# Control_Unit.net
KiCad netlist of a schematic drawn in EAGLE
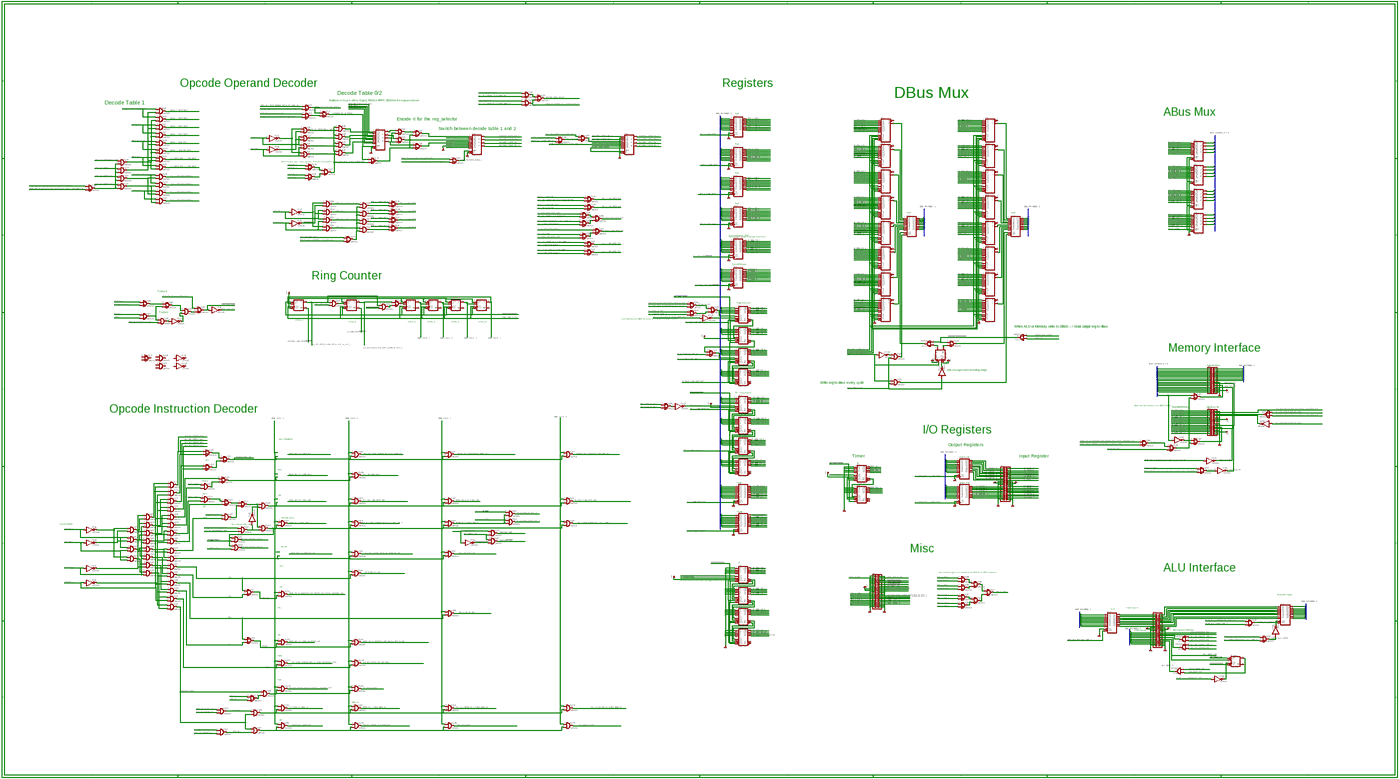
[diagram p0: schematic, sheet 1, overview]
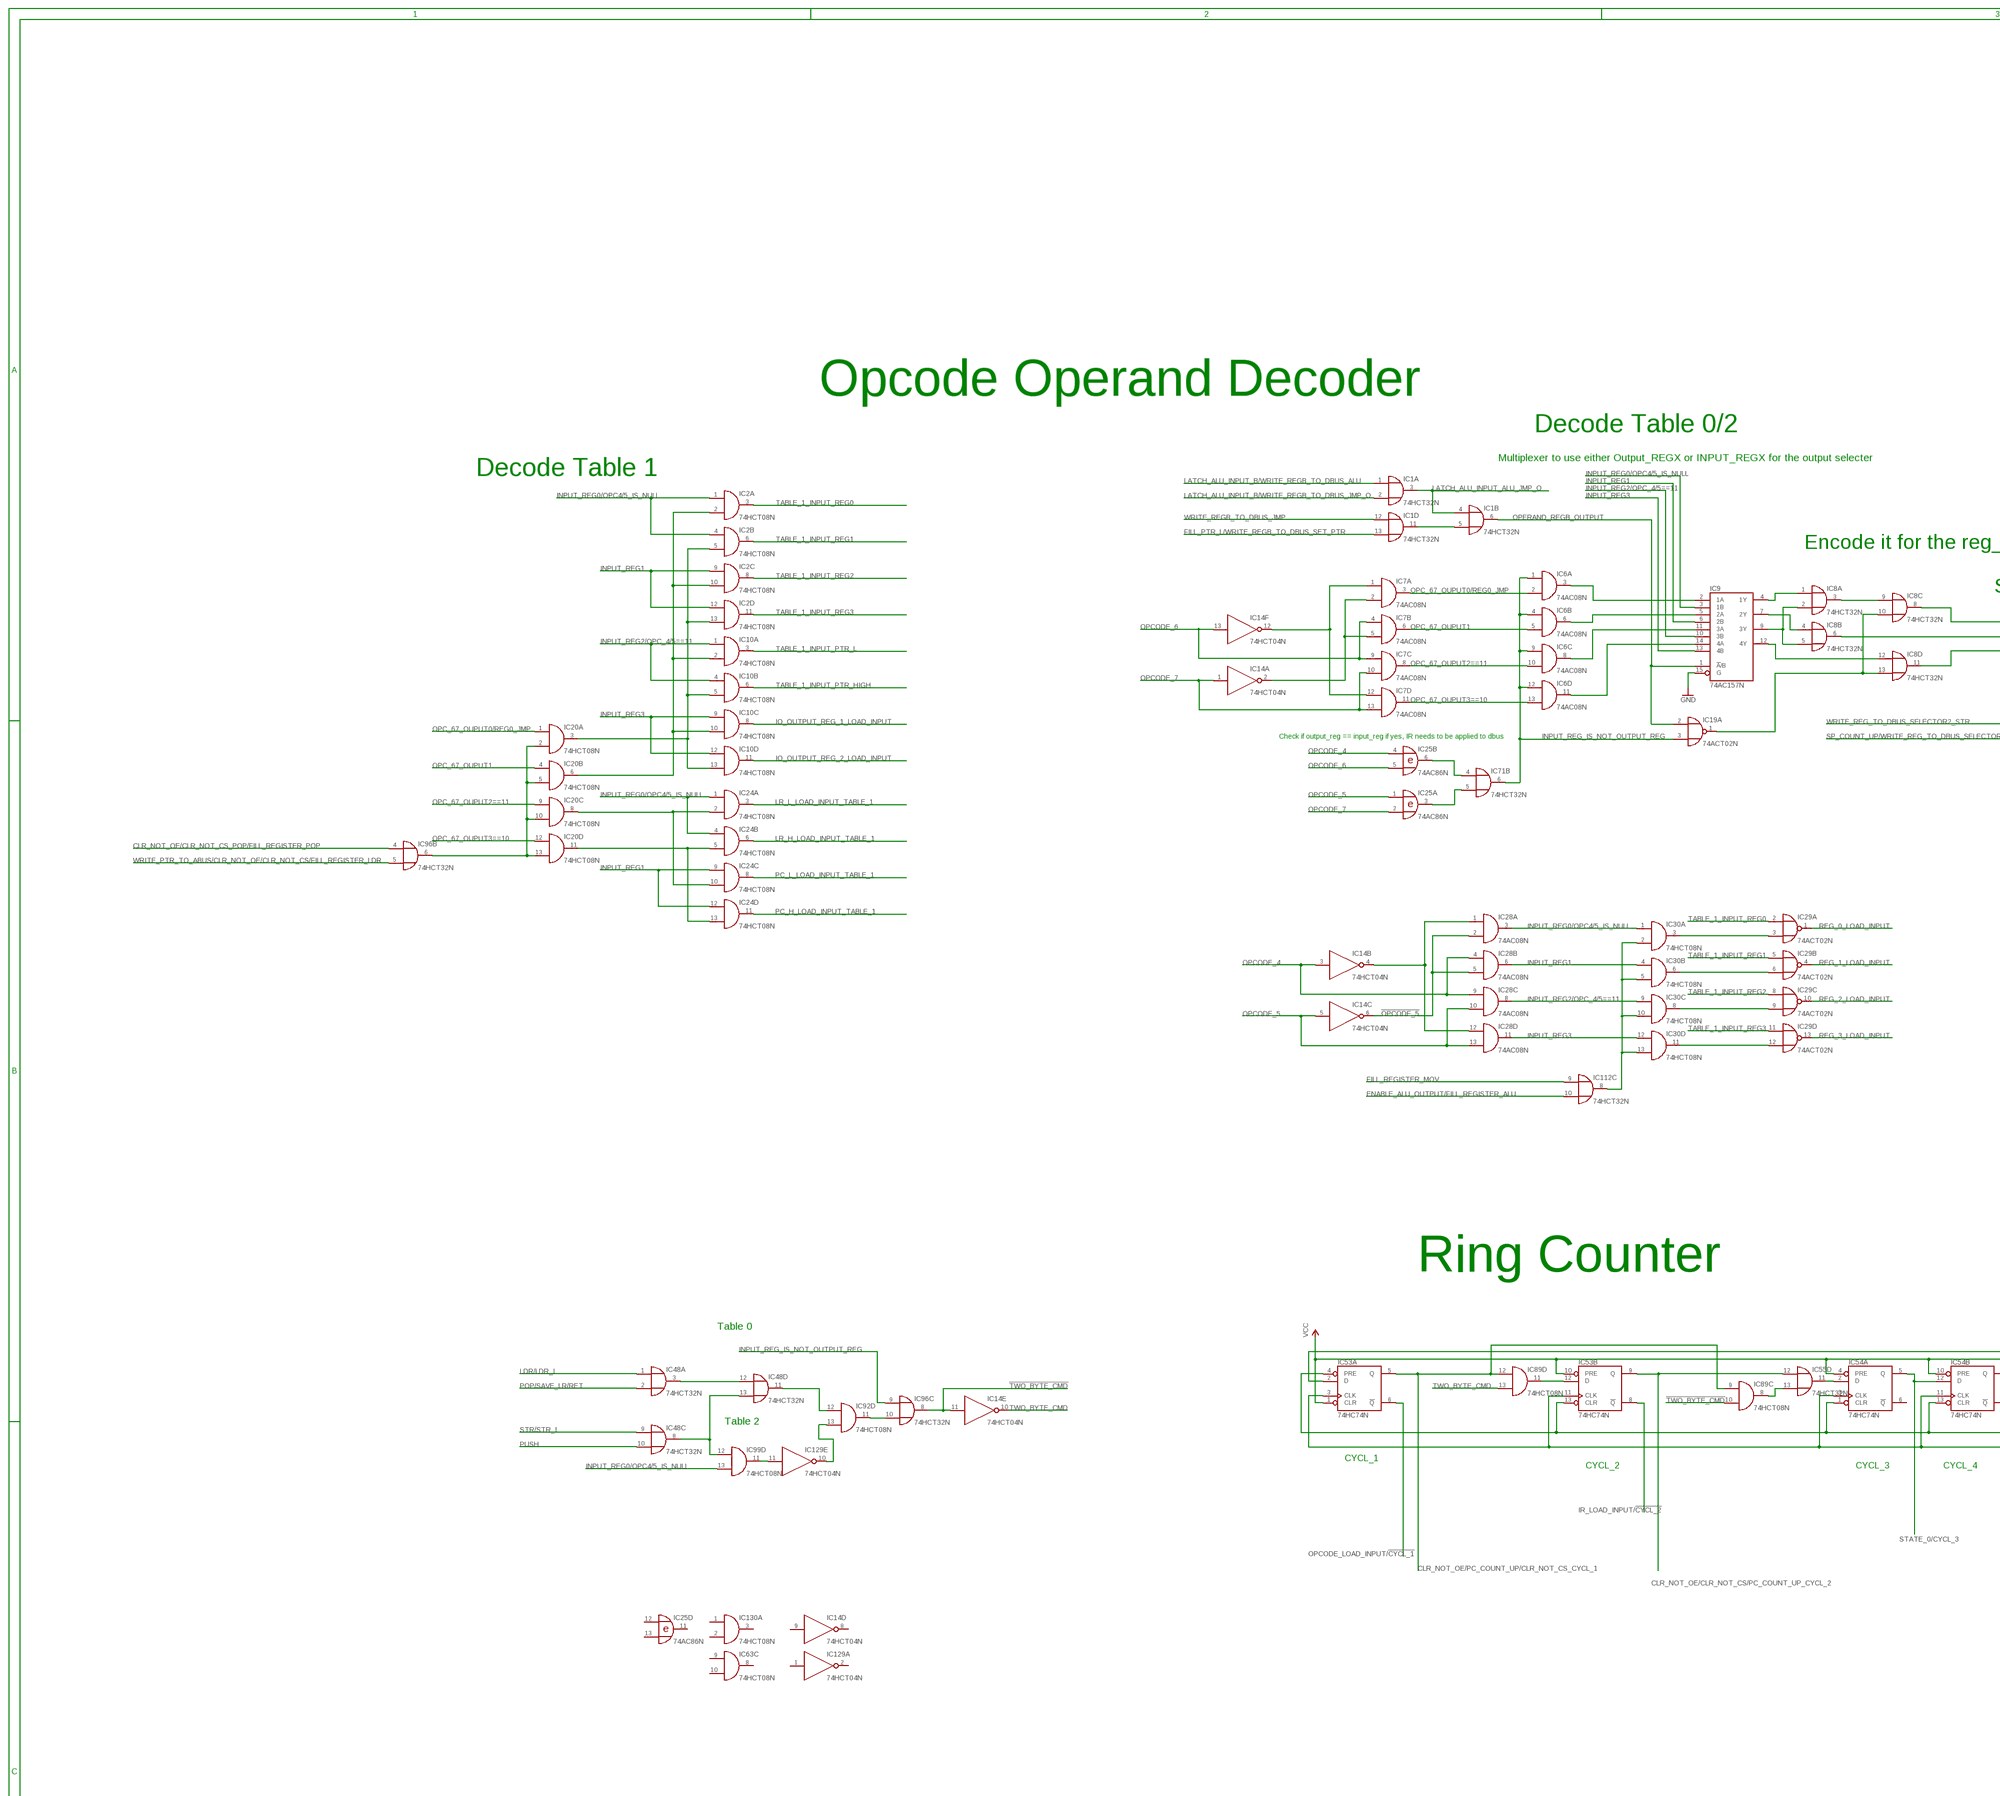
[diagram p1: schematic, sheet 1, part 1 of 8]
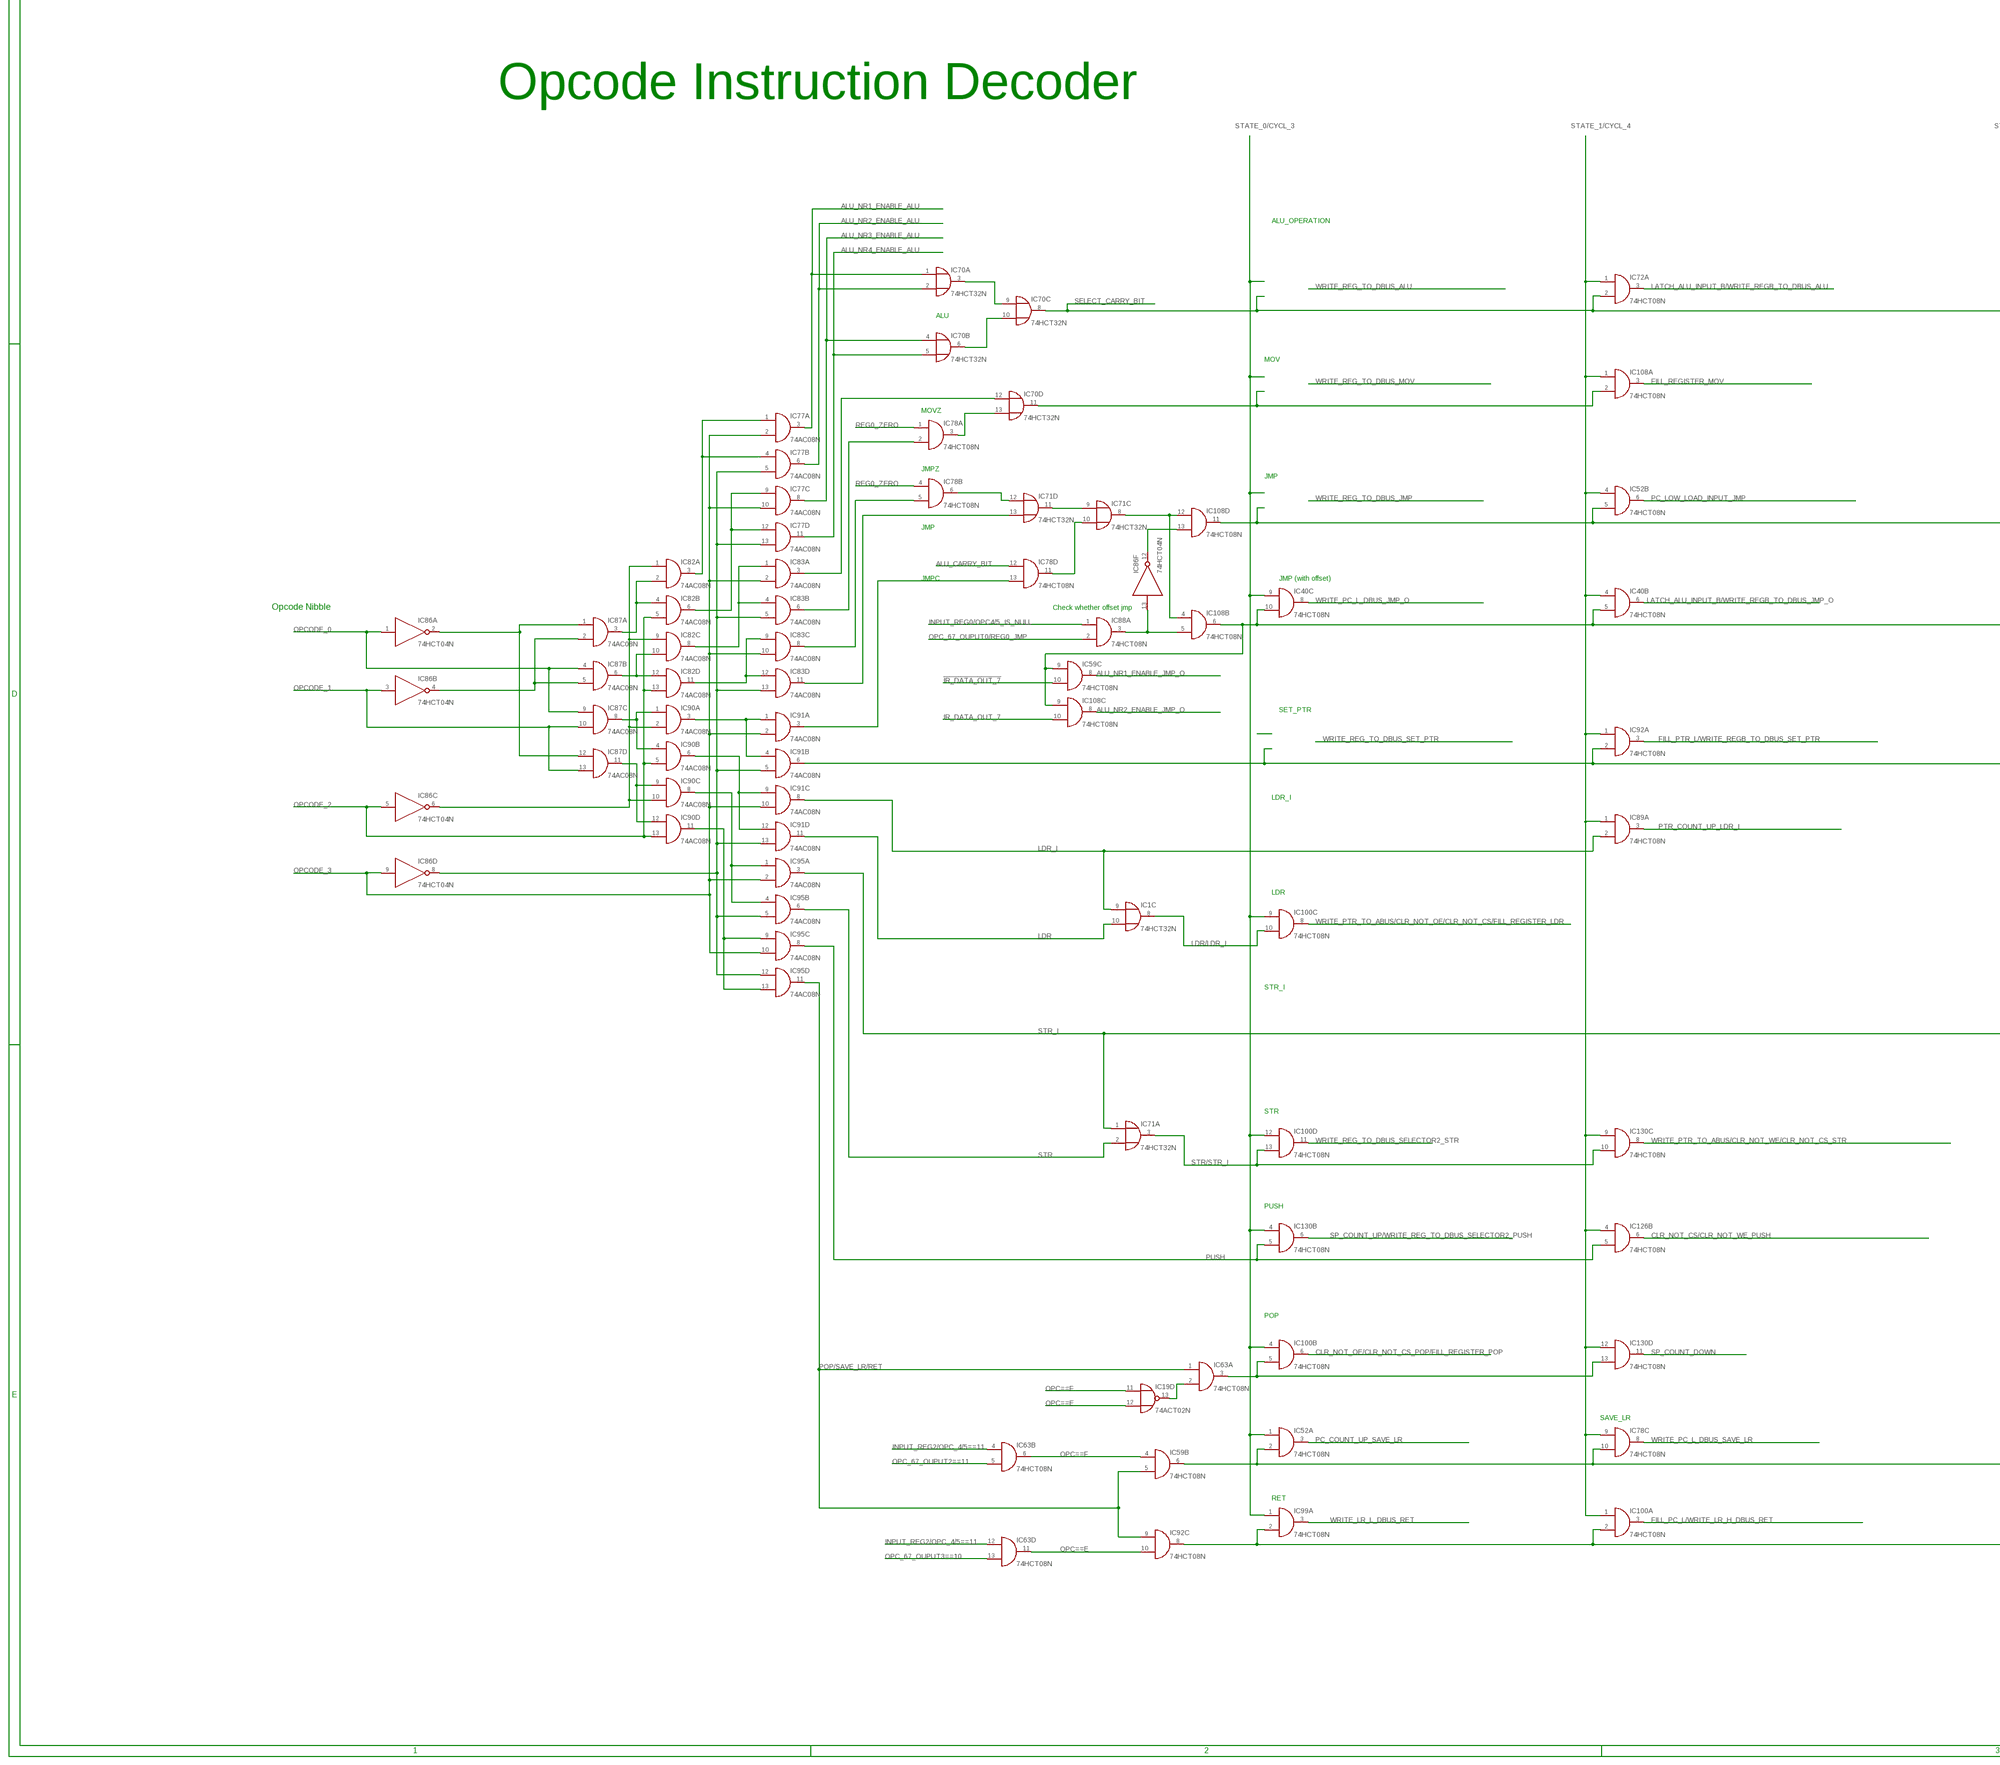
[diagram p2: schematic, sheet 1, part 2 of 8]
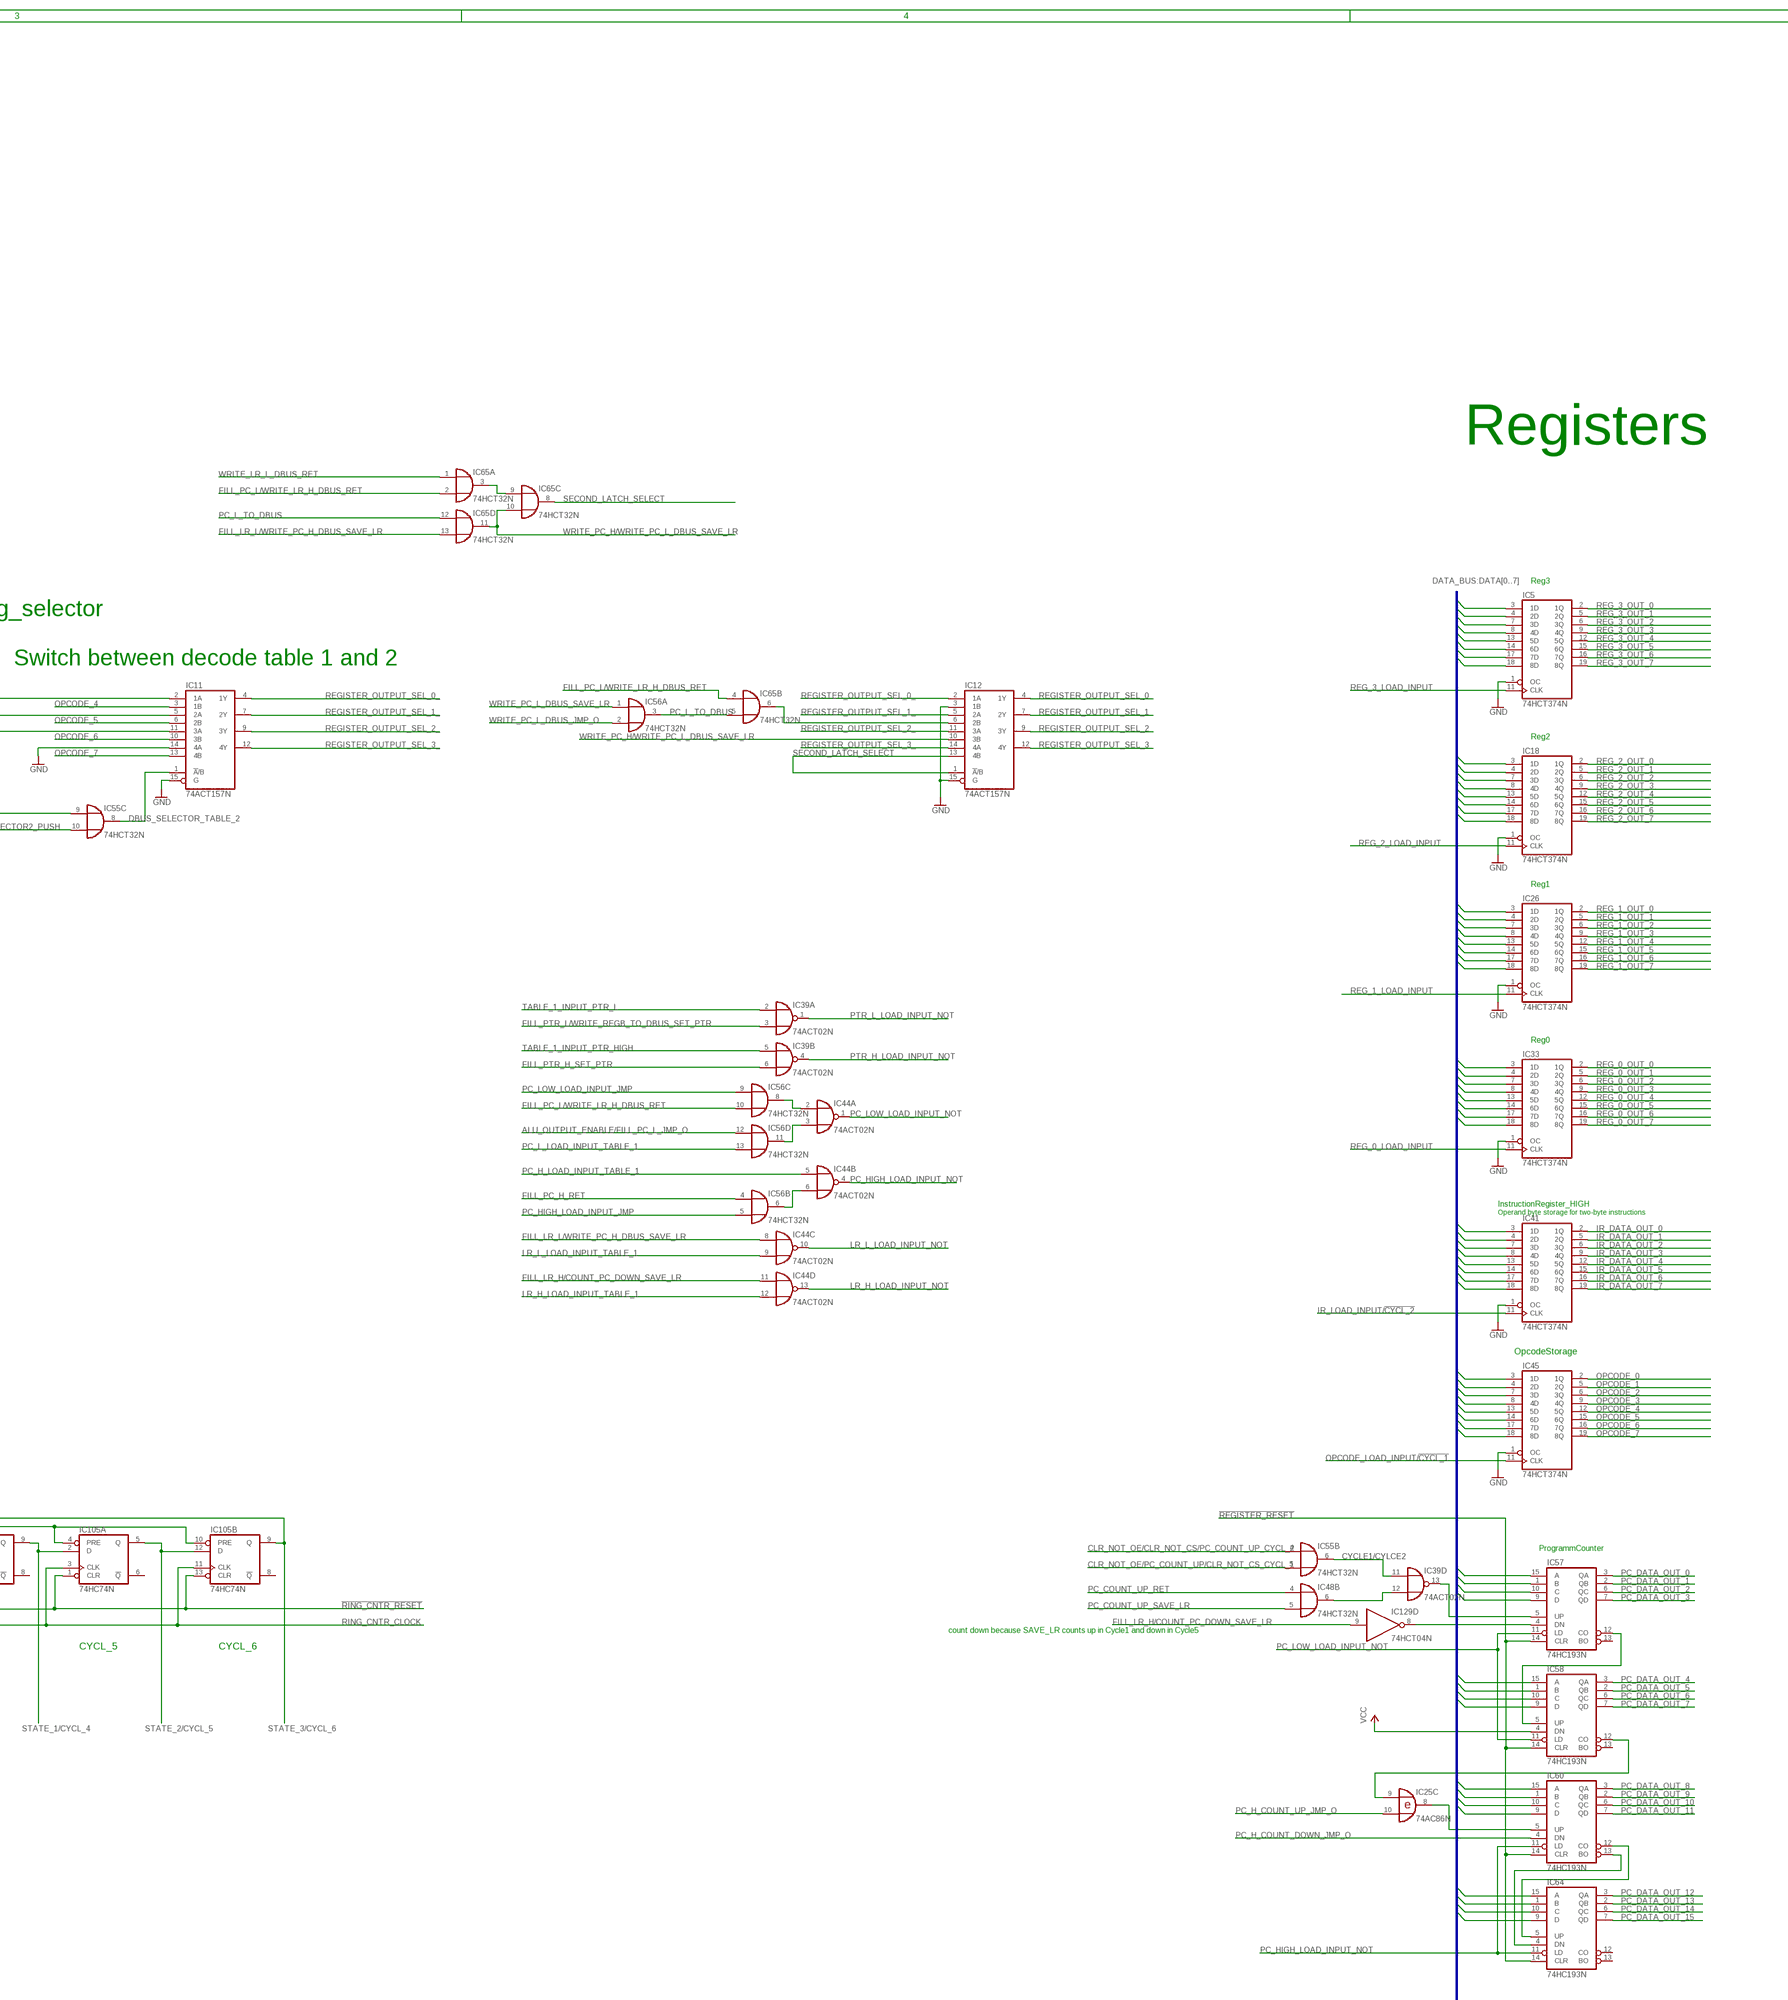
[diagram p3: schematic, sheet 1, part 3 of 8]
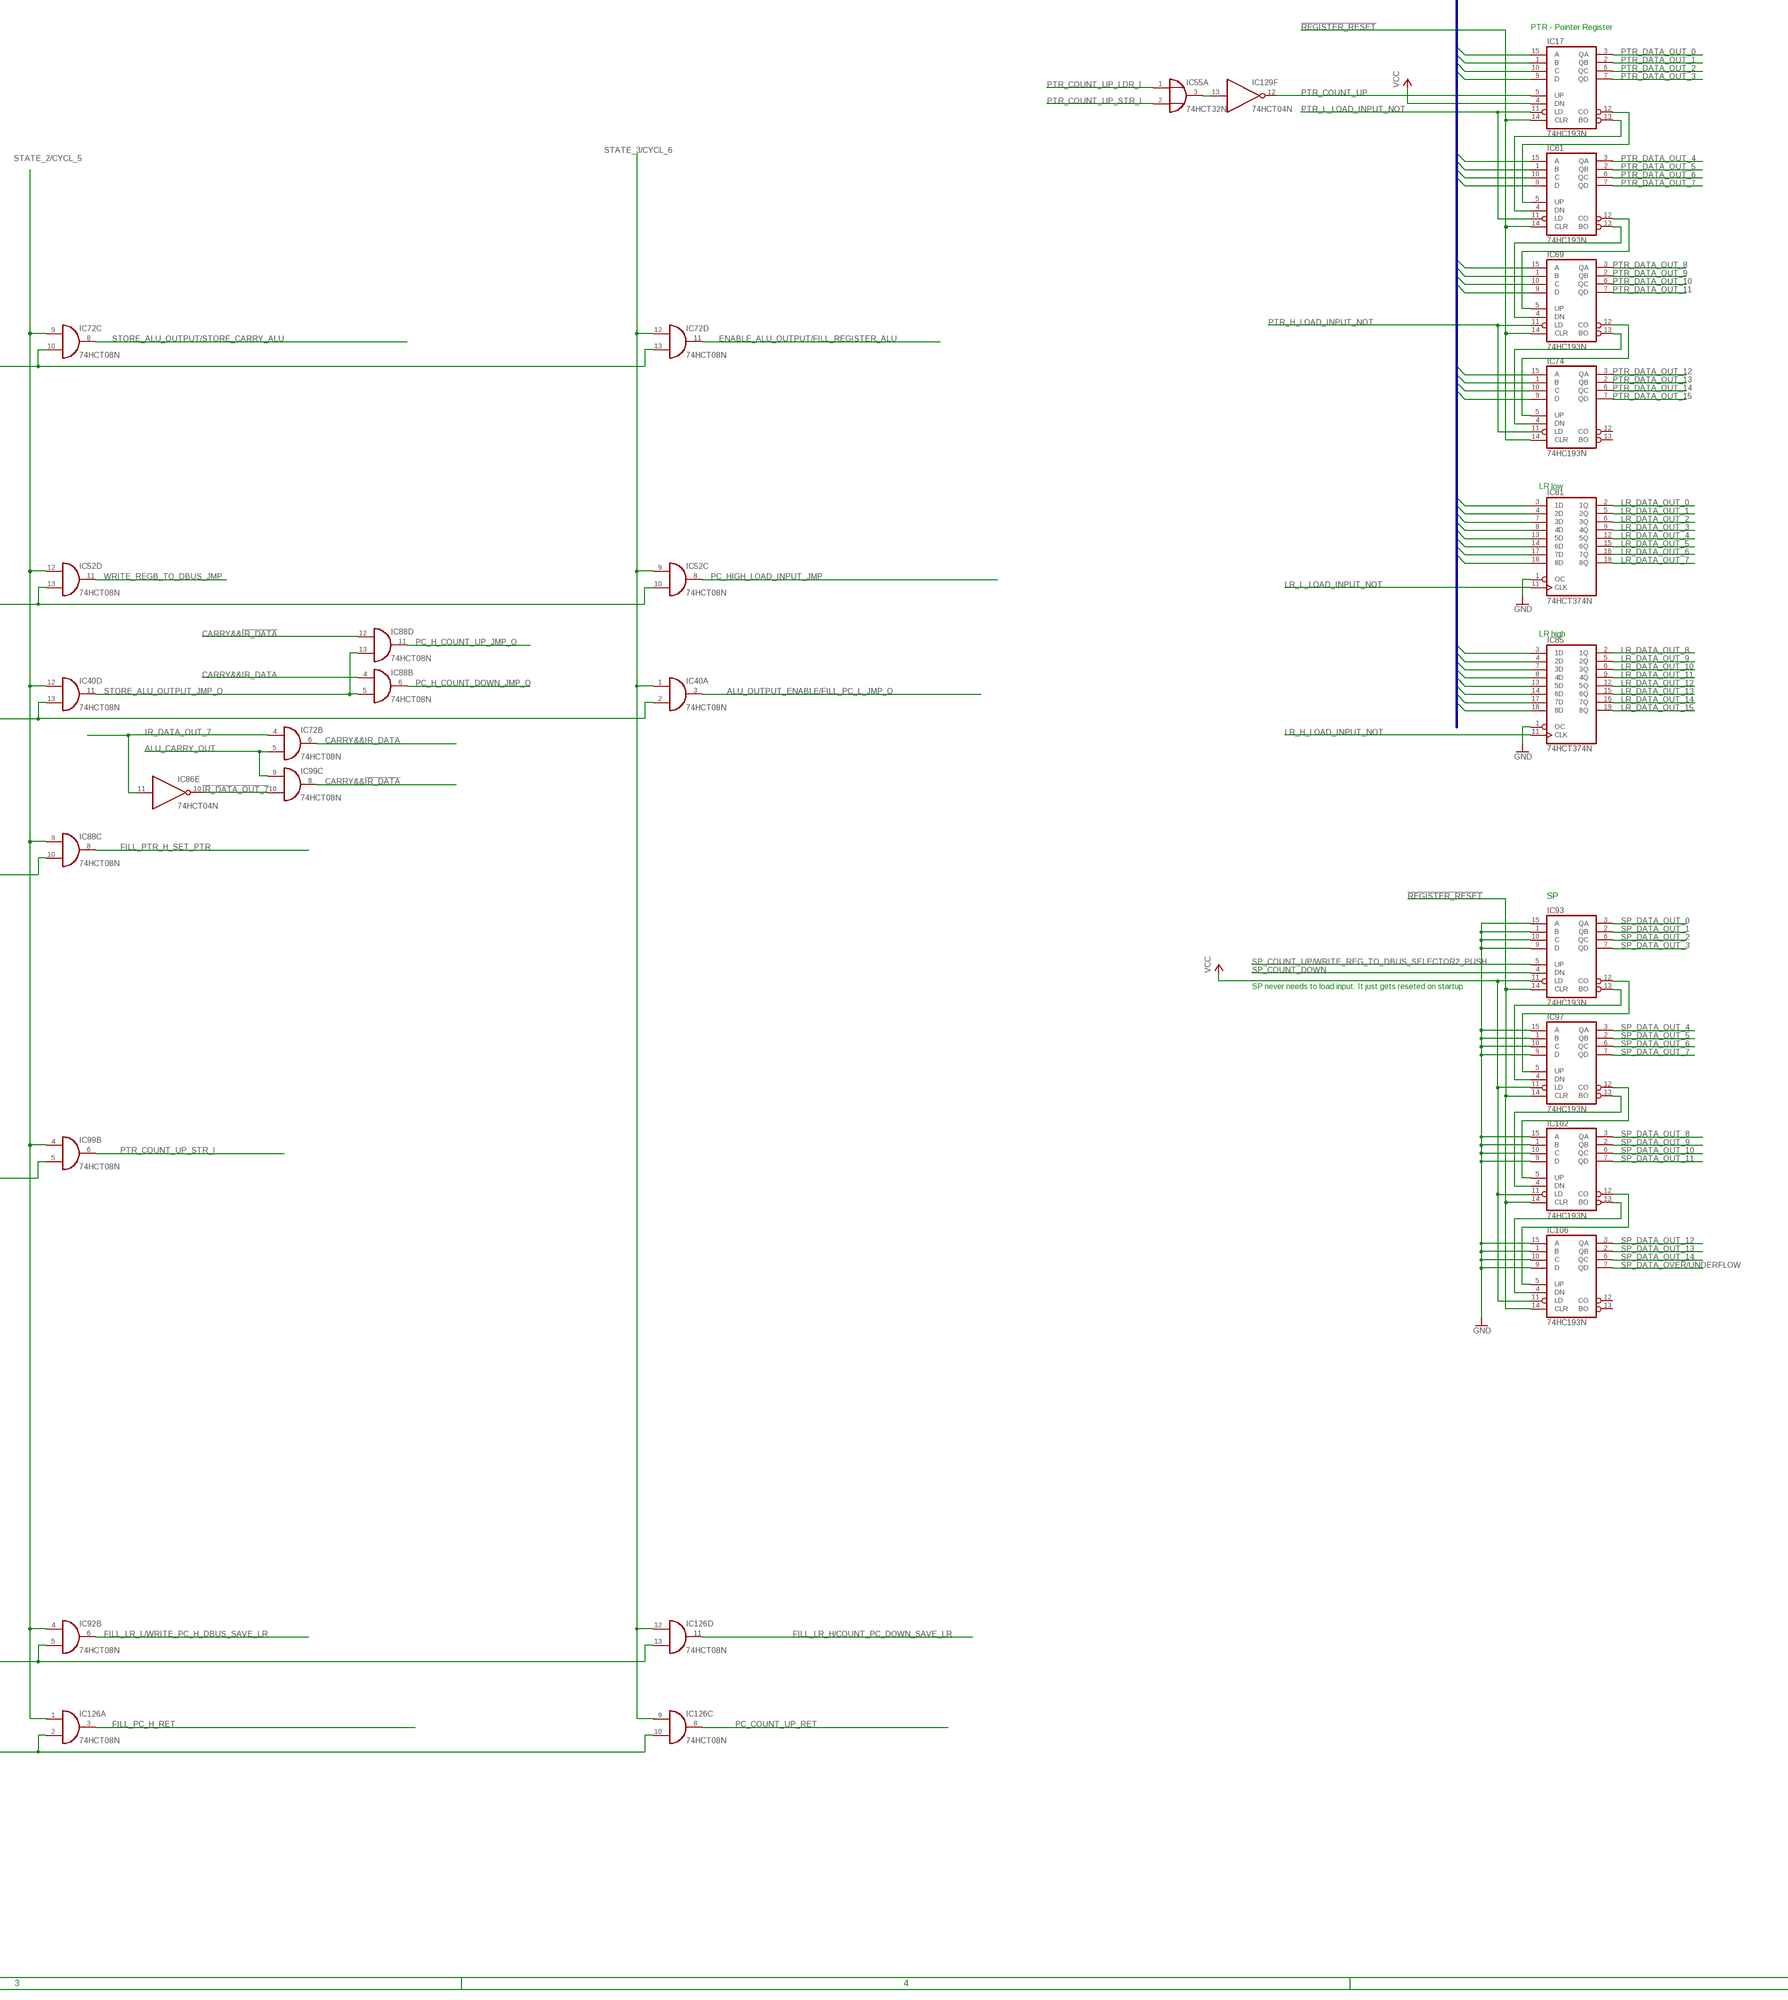
[diagram p4: schematic, sheet 1, part 4 of 8]
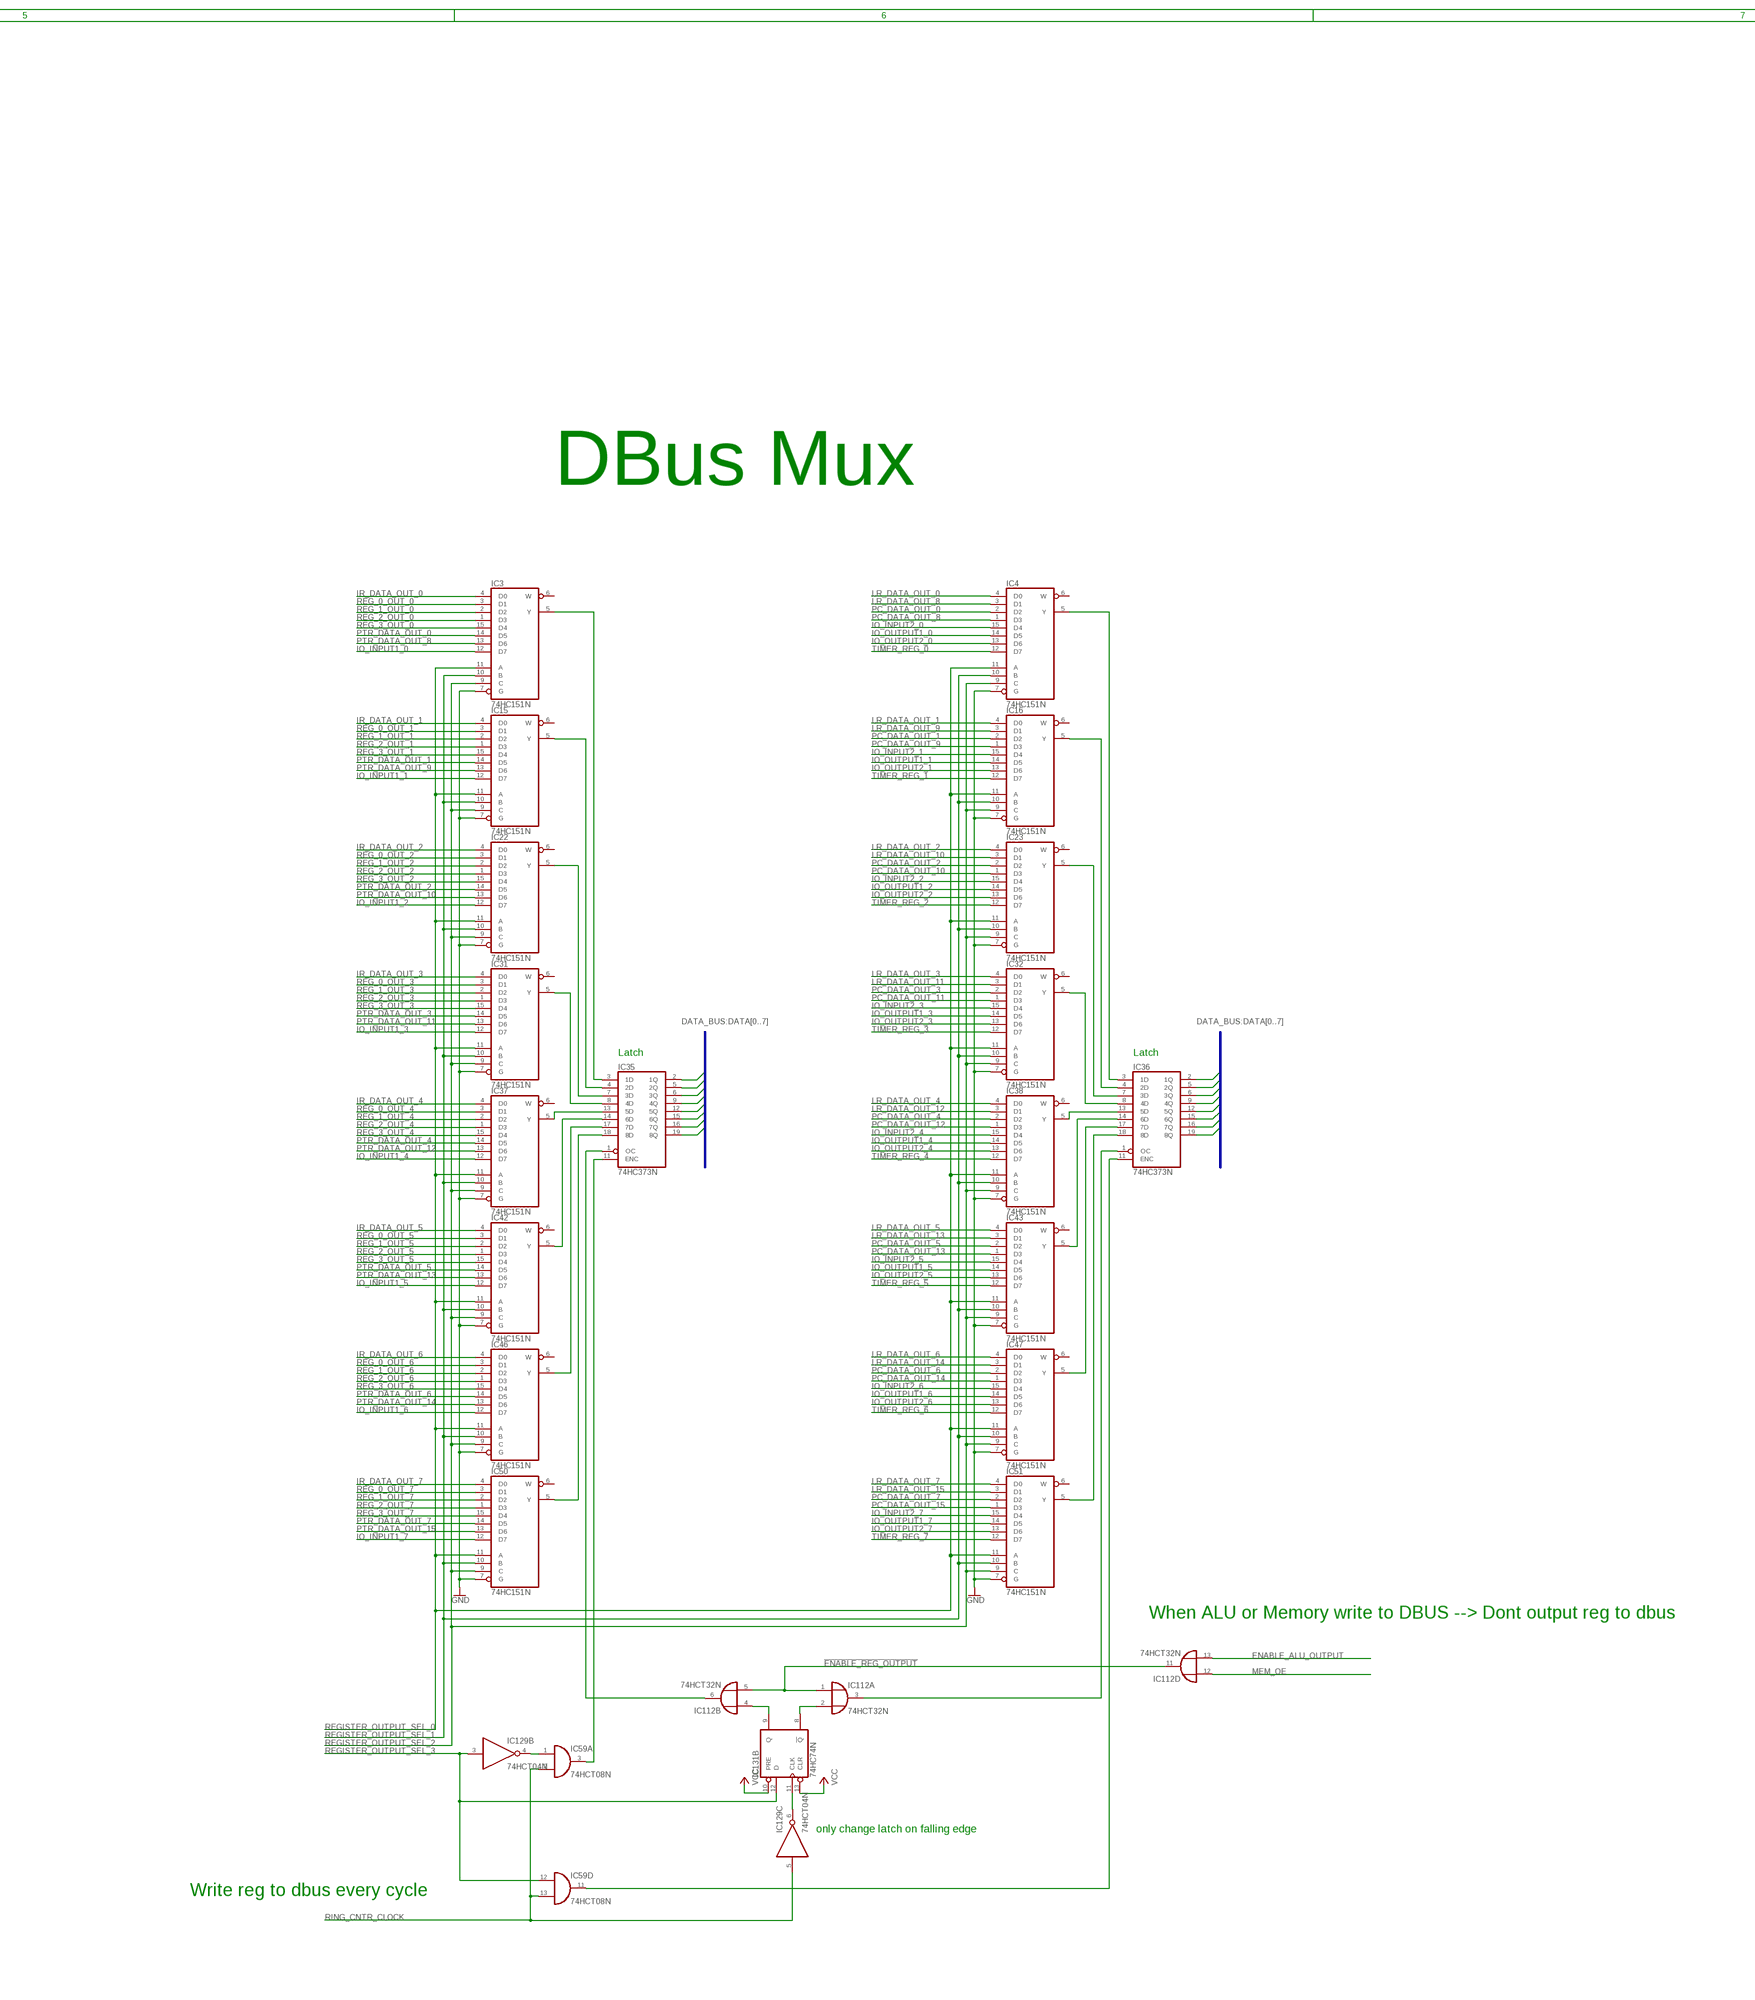
[diagram p5: schematic, sheet 1, part 5 of 8]
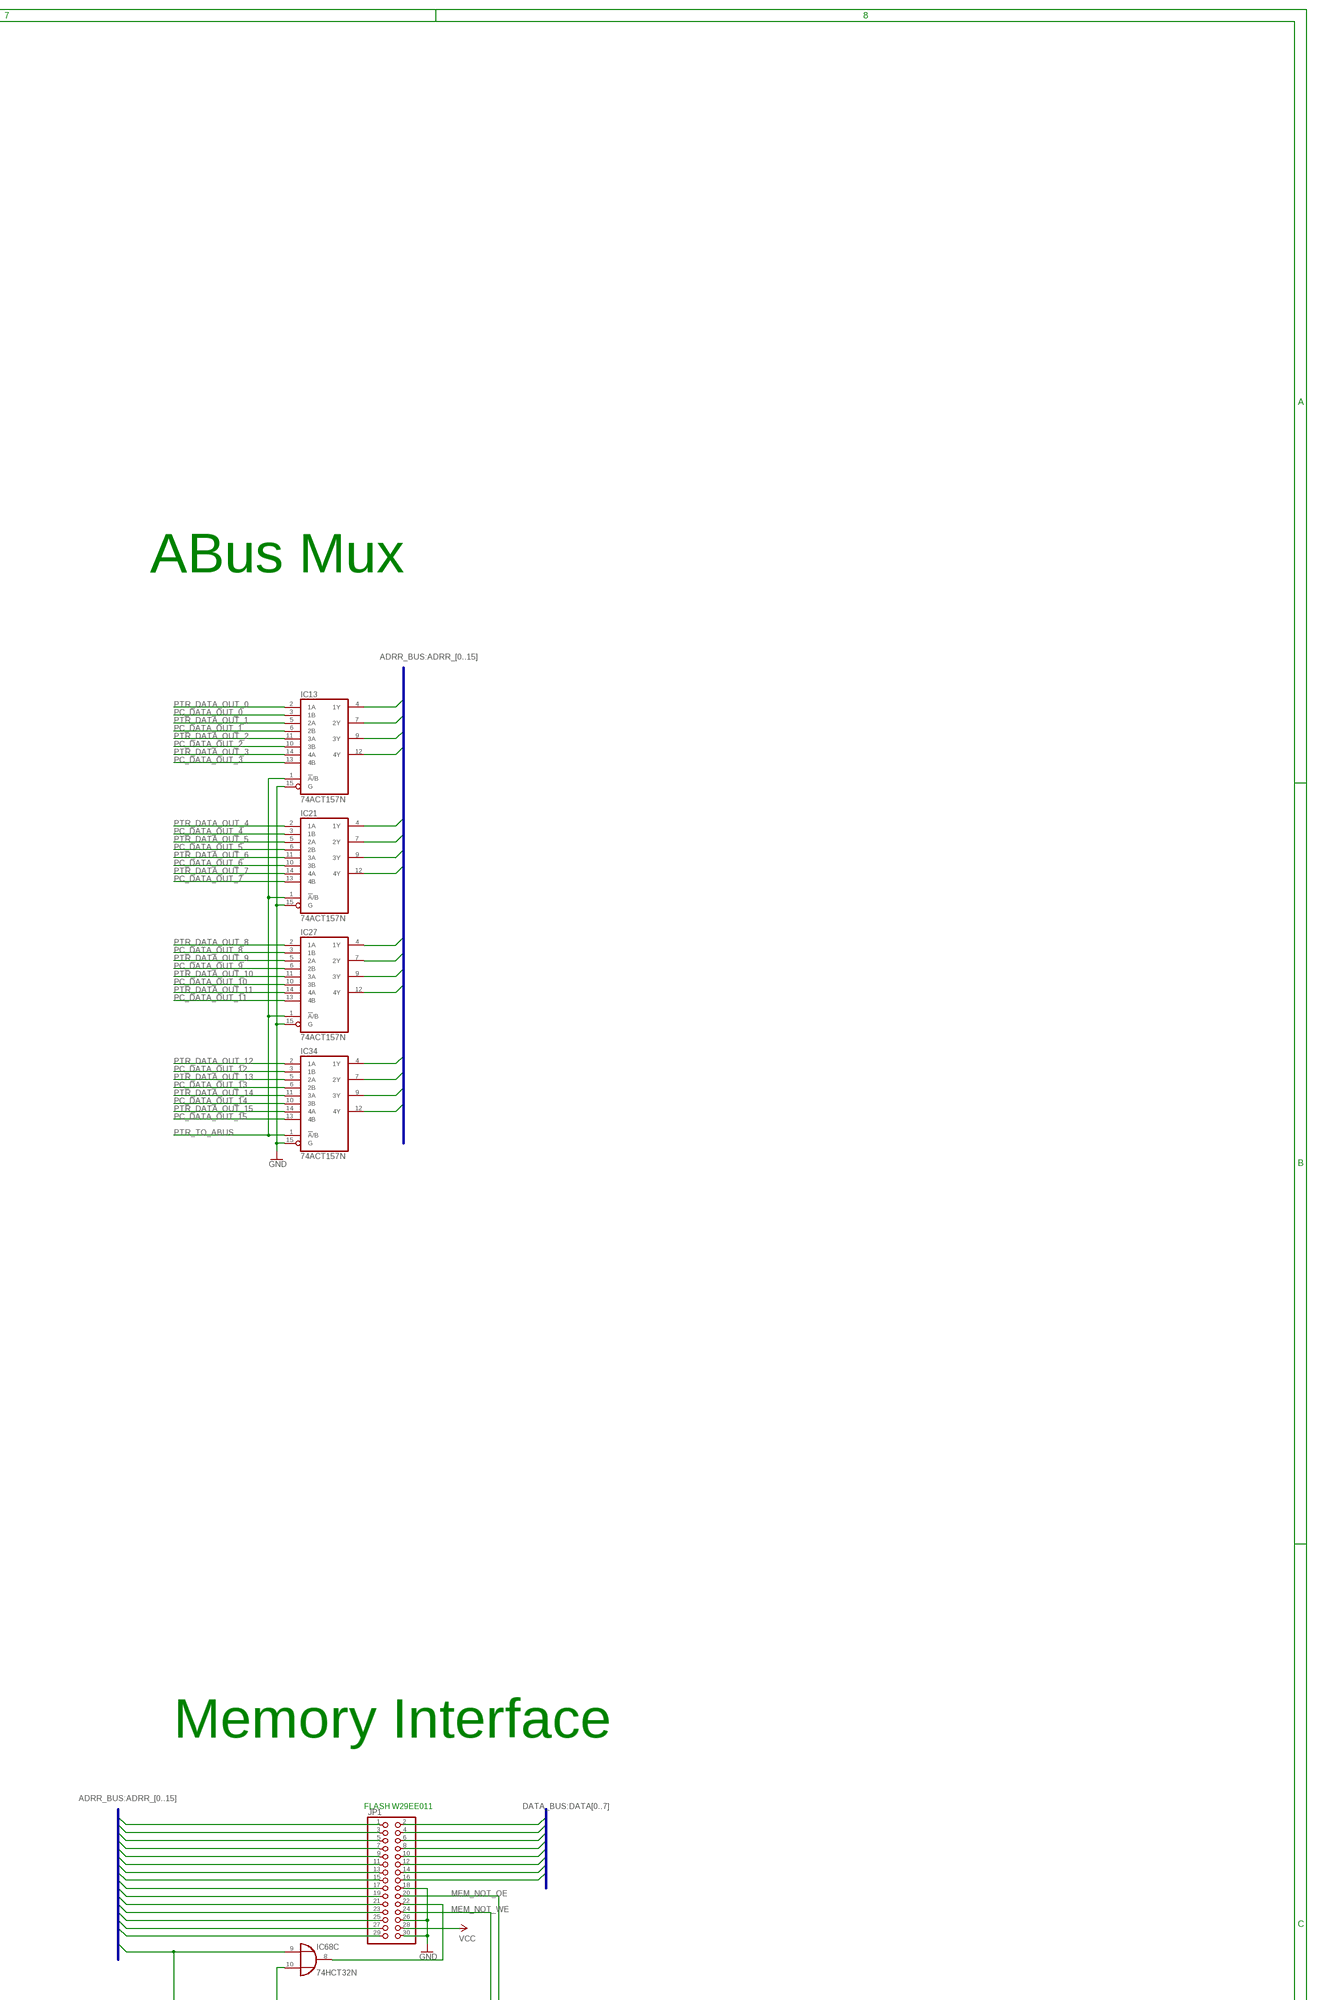
[diagram p6: schematic, sheet 1, part 6 of 8]
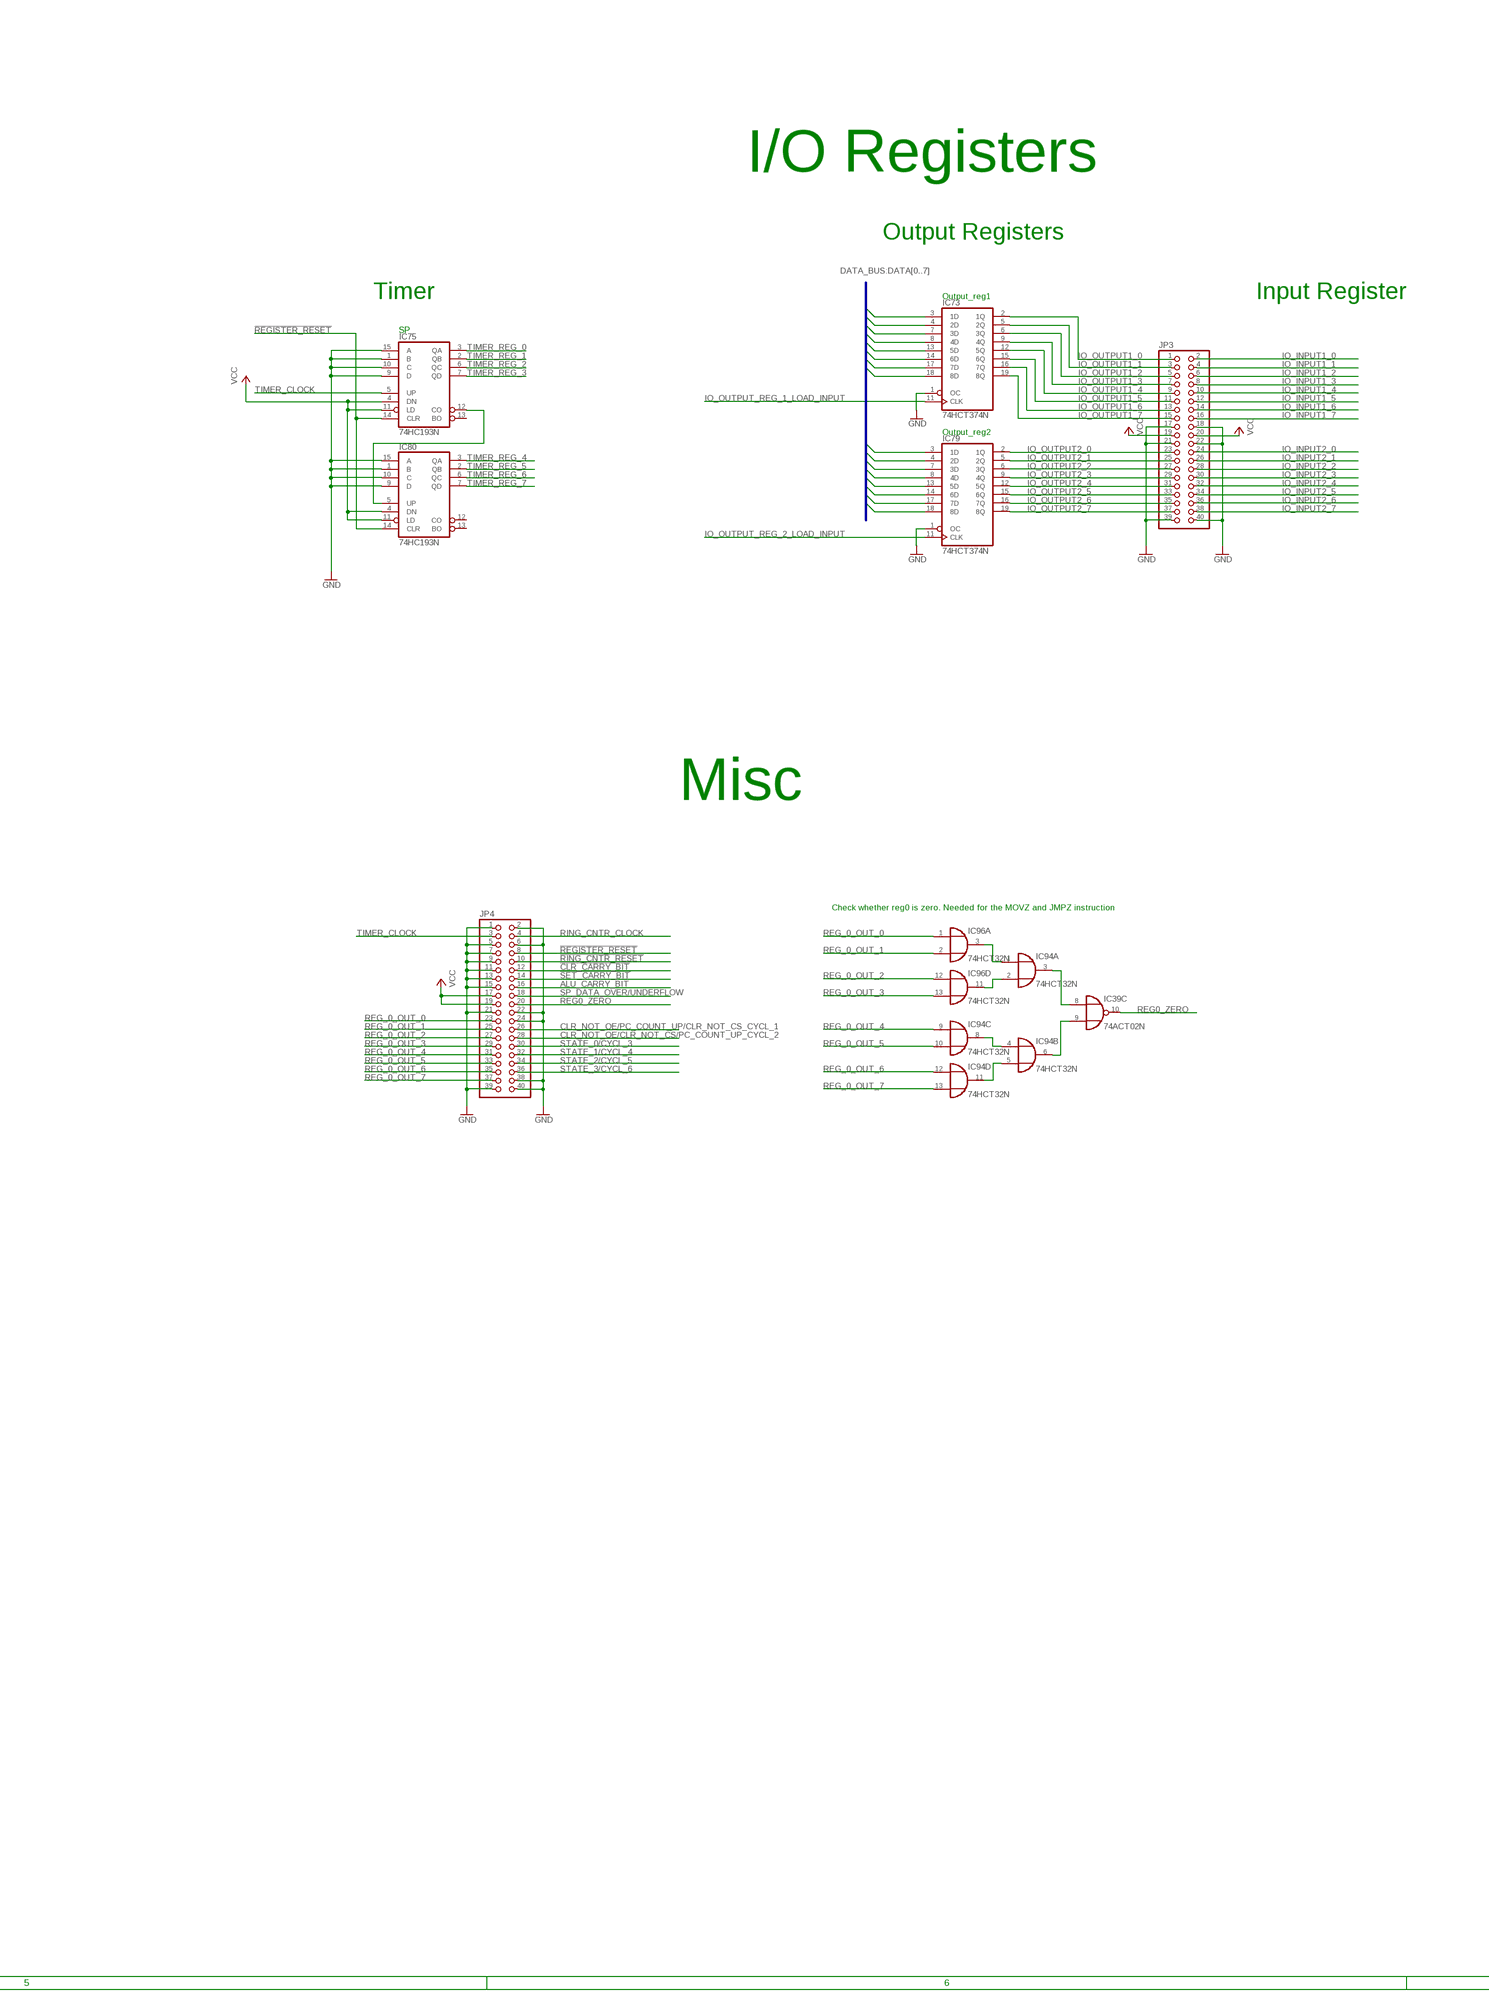
[diagram p7: schematic, sheet 1, part 7 of 8]
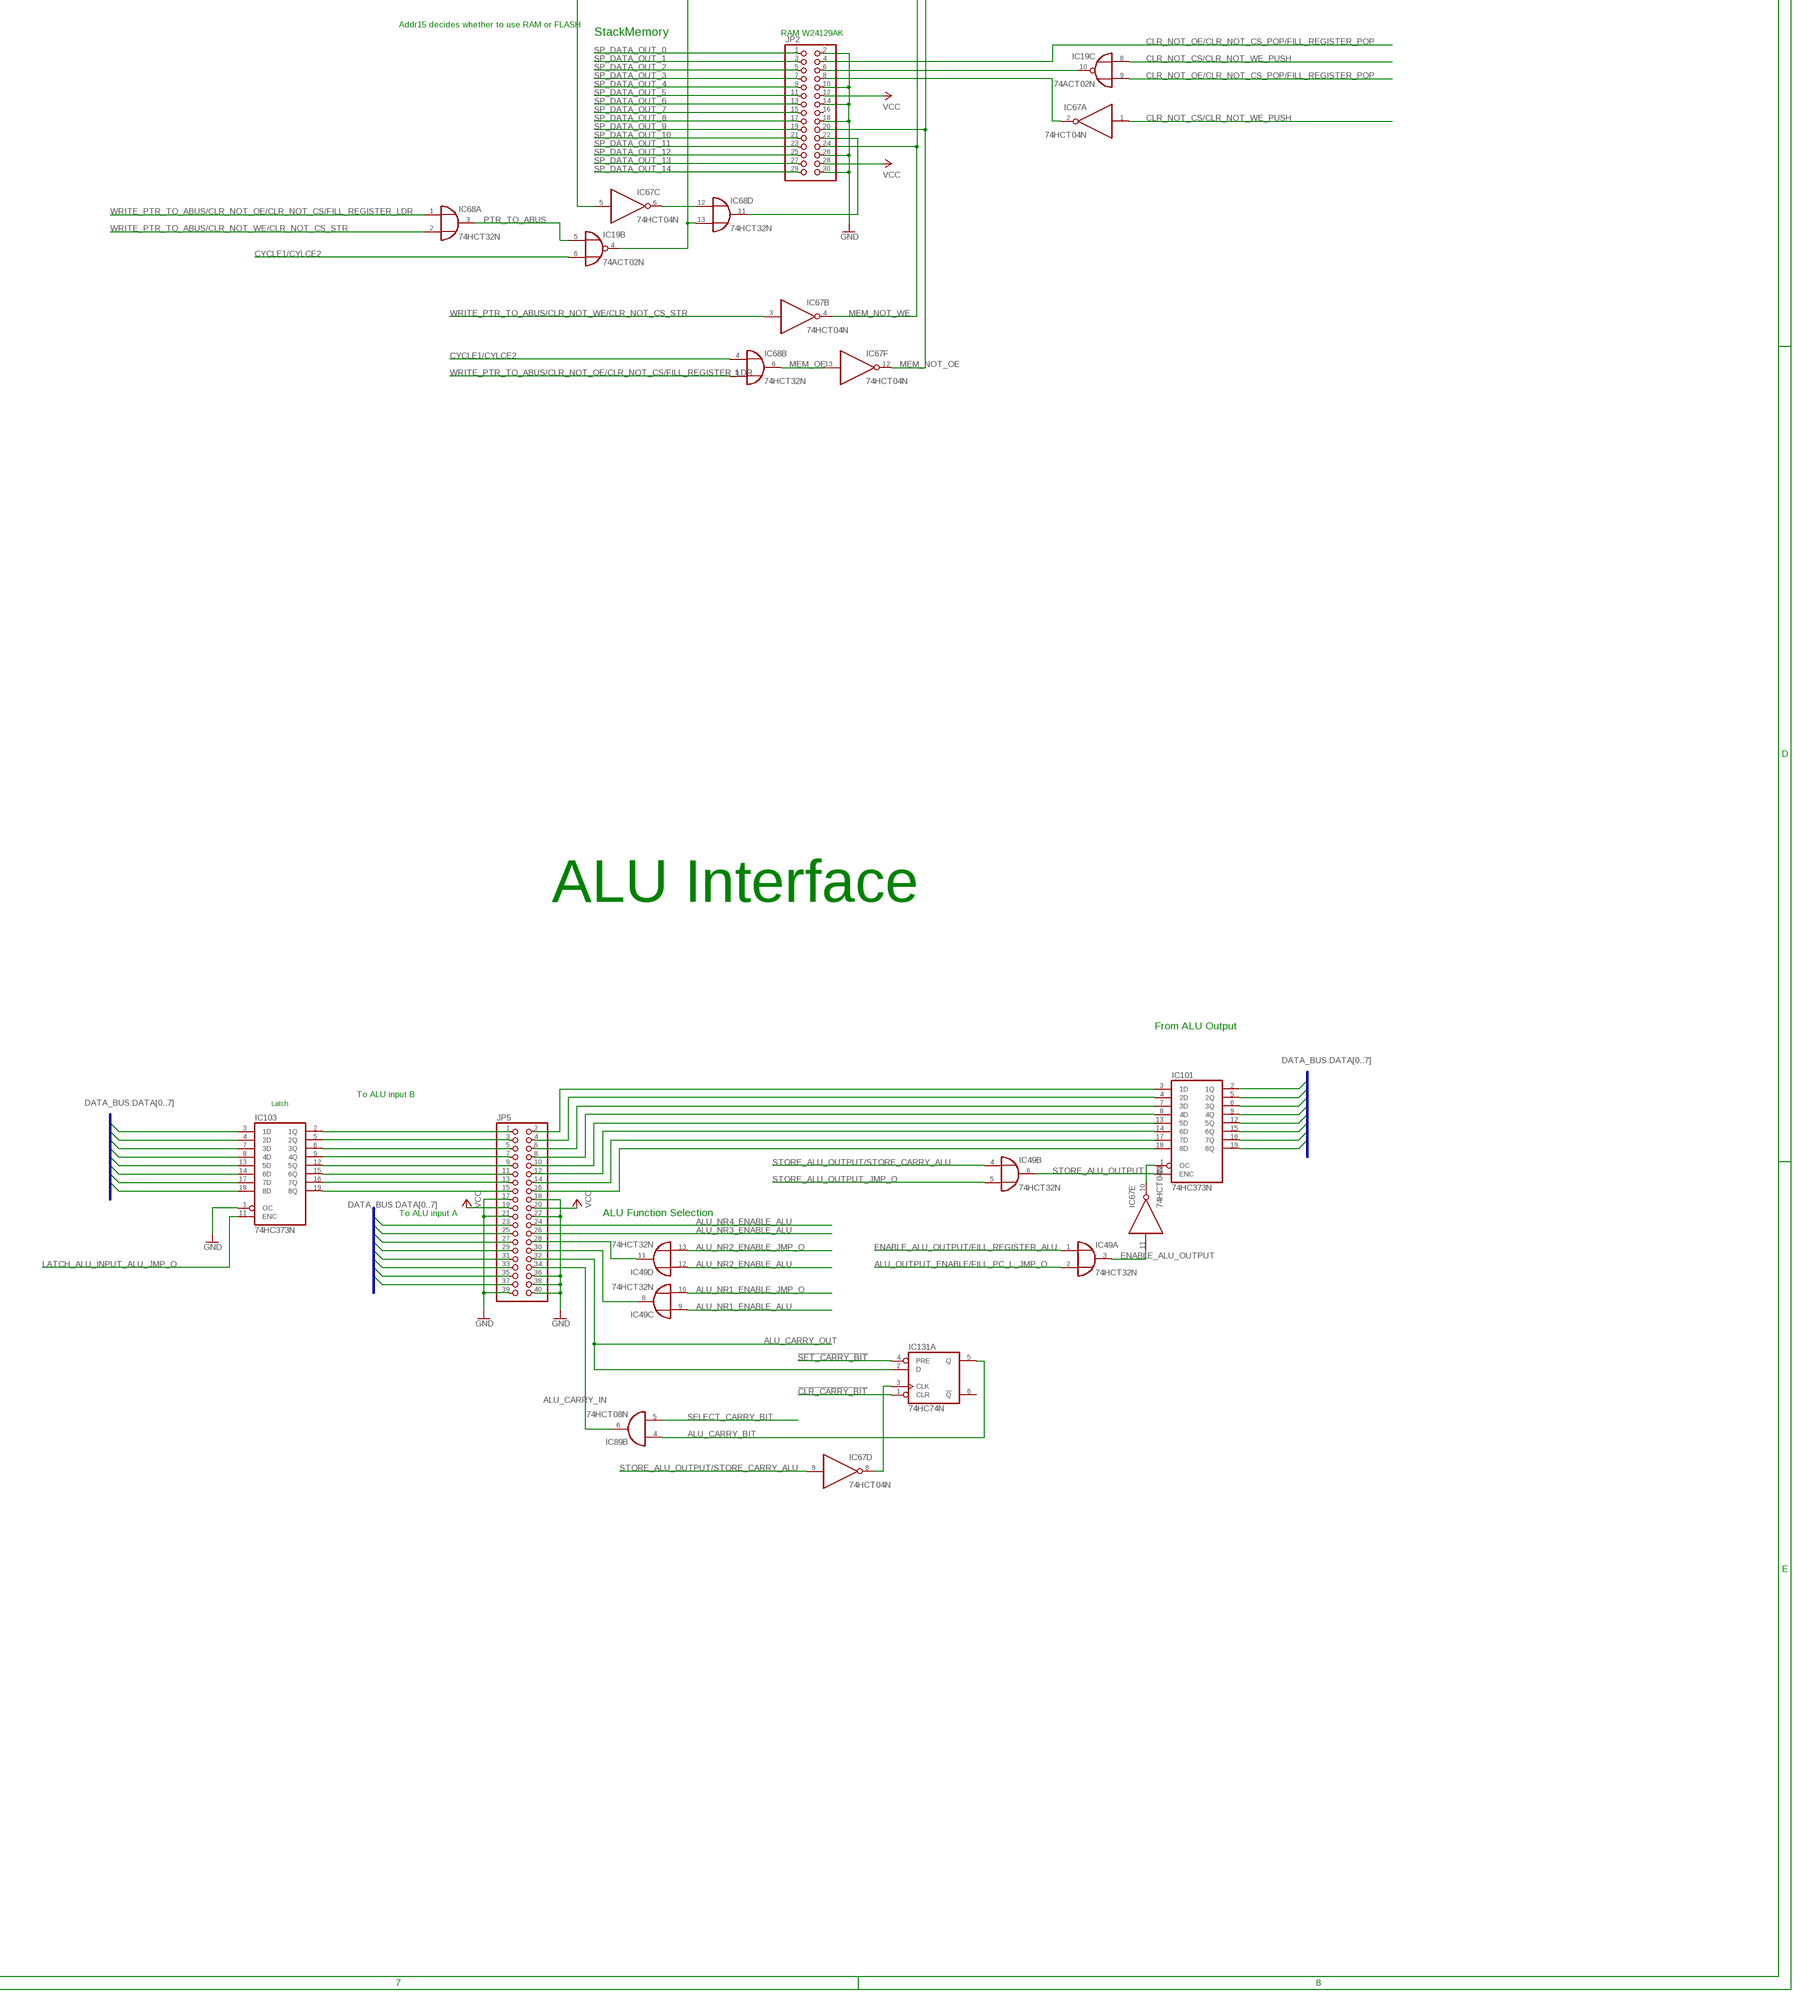
[diagram p8: schematic, sheet 1, part 8 of 8]

(export (version "E")
  (design (tool "Eeschema 10.0.6"))
  (components
    (comp (ref "IC1")
      (value "74HCT32N")
      (footprint "eagle-import:DIL14")
      (libsource (lib "eagle-import") (part "7432NHCT"))
    )
    (comp (ref "IC2")
      (value "74HCT08N")
      (footprint "eagle-import:DIL14")
      (libsource (lib "eagle-import") (part "7408NHCT"))
    )
    (comp (ref "IC3")
      (value "74HC151N")
      (footprint "eagle-import:DIL16")
      (libsource (lib "eagle-import") (part "74151NHC"))
    )
    (comp (ref "IC4")
      (value "74HC151N")
      (footprint "eagle-import:DIL16")
      (libsource (lib "eagle-import") (part "74151NHC"))
    )
    (comp (ref "IC5")
      (value "74HCT374N")
      (footprint "eagle-import:DIL20")
      (libsource (lib "eagle-import") (part "74374NHCT"))
    )
    (comp (ref "IC6")
      (value "74AC08N")
      (footprint "eagle-import:DIL14")
      (libsource (lib "eagle-import") (part "7408NAC"))
    )
    (comp (ref "IC7")
      (value "74AC08N")
      (footprint "eagle-import:DIL14")
      (libsource (lib "eagle-import") (part "7408NAC"))
    )
    (comp (ref "IC8")
      (value "74HCT32N")
      (footprint "eagle-import:DIL14")
      (libsource (lib "eagle-import") (part "7432NHCT"))
    )
    (comp (ref "IC9")
      (value "74AC157N")
      (footprint "eagle-import:DIL16")
      (libsource (lib "eagle-import") (part "74157NAC"))
    )
    (comp (ref "IC10")
      (value "74HCT08N")
      (footprint "eagle-import:DIL14")
      (libsource (lib "eagle-import") (part "7408NHCT"))
    )
    (comp (ref "IC11")
      (value "74ACT157N")
      (footprint "eagle-import:DIL16")
      (libsource (lib "eagle-import") (part "74157NACT"))
    )
    (comp (ref "IC12")
      (value "74ACT157N")
      (footprint "eagle-import:DIL16")
      (libsource (lib "eagle-import") (part "74157NACT"))
    )
    (comp (ref "IC13")
      (value "74ACT157N")
      (footprint "eagle-import:DIL16")
      (libsource (lib "eagle-import") (part "74157NACT"))
    )
    (comp (ref "IC14")
      (value "74HCT04N")
      (footprint "eagle-import:DIL14")
      (libsource (lib "eagle-import") (part "7404NHCT"))
    )
    (comp (ref "IC15")
      (value "74HC151N")
      (footprint "eagle-import:DIL16")
      (libsource (lib "eagle-import") (part "74151NHC"))
    )
    (comp (ref "IC16")
      (value "74HC151N")
      (footprint "eagle-import:DIL16")
      (libsource (lib "eagle-import") (part "74151NHC"))
    )
    (comp (ref "IC17")
      (value "74HC193N")
      (footprint "eagle-import:DIL16")
      (libsource (lib "eagle-import") (part "74193NHC"))
    )
    (comp (ref "IC18")
      (value "74HCT374N")
      (footprint "eagle-import:DIL20")
      (libsource (lib "eagle-import") (part "74374NHCT"))
    )
    (comp (ref "IC19")
      (value "74ACT02N")
      (footprint "eagle-import:DIL14")
      (libsource (lib "eagle-import") (part "7402NACT"))
    )
    (comp (ref "IC20")
      (value "74HCT08N")
      (footprint "eagle-import:DIL14")
      (libsource (lib "eagle-import") (part "7408NHCT"))
    )
    (comp (ref "IC21")
      (value "74ACT157N")
      (footprint "eagle-import:DIL16")
      (libsource (lib "eagle-import") (part "74157NACT"))
    )
    (comp (ref "IC22")
      (value "74HC151N")
      (footprint "eagle-import:DIL16")
      (libsource (lib "eagle-import") (part "74151NHC"))
    )
    (comp (ref "IC23")
      (value "74HC151N")
      (footprint "eagle-import:DIL16")
      (libsource (lib "eagle-import") (part "74151NHC"))
    )
    (comp (ref "IC24")
      (value "74HCT08N")
      (footprint "eagle-import:DIL14")
      (libsource (lib "eagle-import") (part "7408NHCT"))
    )
    (comp (ref "IC25")
      (value "74AC86N")
      (footprint "eagle-import:DIL14")
      (libsource (lib "eagle-import") (part "7486NAC"))
    )
    (comp (ref "IC26")
      (value "74HCT374N")
      (footprint "eagle-import:DIL20")
      (libsource (lib "eagle-import") (part "74374NHCT"))
    )
    (comp (ref "IC27")
      (value "74ACT157N")
      (footprint "eagle-import:DIL16")
      (libsource (lib "eagle-import") (part "74157NACT"))
    )
    (comp (ref "IC28")
      (value "74AC08N")
      (footprint "eagle-import:DIL14")
      (libsource (lib "eagle-import") (part "7408NAC"))
    )
    (comp (ref "IC29")
      (value "74ACT02N")
      (footprint "eagle-import:DIL14")
      (libsource (lib "eagle-import") (part "7402NACT"))
    )
    (comp (ref "IC30")
      (value "74HCT08N")
      (footprint "eagle-import:DIL14")
      (libsource (lib "eagle-import") (part "7408NHCT"))
    )
    (comp (ref "IC31")
      (value "74HC151N")
      (footprint "eagle-import:DIL16")
      (libsource (lib "eagle-import") (part "74151NHC"))
    )
    (comp (ref "IC32")
      (value "74HC151N")
      (footprint "eagle-import:DIL16")
      (libsource (lib "eagle-import") (part "74151NHC"))
    )
    (comp (ref "IC33")
      (value "74HCT374N")
      (footprint "eagle-import:DIL20")
      (libsource (lib "eagle-import") (part "74374NHCT"))
    )
    (comp (ref "IC34")
      (value "74ACT157N")
      (footprint "eagle-import:DIL16")
      (libsource (lib "eagle-import") (part "74157NACT"))
    )
    (comp (ref "IC35")
      (value "74HC373N")
      (footprint "eagle-import:DIL20")
      (libsource (lib "eagle-import") (part "74373NHC"))
    )
    (comp (ref "IC36")
      (value "74HC373N")
      (footprint "eagle-import:DIL20")
      (libsource (lib "eagle-import") (part "74373NHC"))
    )
    (comp (ref "IC37")
      (value "74HC151N")
      (footprint "eagle-import:DIL16")
      (libsource (lib "eagle-import") (part "74151NHC"))
    )
    (comp (ref "IC38")
      (value "74HC151N")
      (footprint "eagle-import:DIL16")
      (libsource (lib "eagle-import") (part "74151NHC"))
    )
    (comp (ref "IC39")
      (value "74ACT02N")
      (footprint "eagle-import:DIL14")
      (libsource (lib "eagle-import") (part "7402NACT"))
    )
    (comp (ref "IC40")
      (value "74HCT08N")
      (footprint "eagle-import:DIL14")
      (libsource (lib "eagle-import") (part "7408NHCT"))
    )
    (comp (ref "IC41")
      (value "74HCT374N")
      (footprint "eagle-import:DIL20")
      (libsource (lib "eagle-import") (part "74374NHCT"))
    )
    (comp (ref "IC42")
      (value "74HC151N")
      (footprint "eagle-import:DIL16")
      (libsource (lib "eagle-import") (part "74151NHC"))
    )
    (comp (ref "IC43")
      (value "74HC151N")
      (footprint "eagle-import:DIL16")
      (libsource (lib "eagle-import") (part "74151NHC"))
    )
    (comp (ref "IC44")
      (value "74ACT02N")
      (footprint "eagle-import:DIL14")
      (libsource (lib "eagle-import") (part "7402NACT"))
    )
    (comp (ref "IC45")
      (value "74HCT374N")
      (footprint "eagle-import:DIL20")
      (libsource (lib "eagle-import") (part "74374NHCT"))
    )
    (comp (ref "IC46")
      (value "74HC151N")
      (footprint "eagle-import:DIL16")
      (libsource (lib "eagle-import") (part "74151NHC"))
    )
    (comp (ref "IC47")
      (value "74HC151N")
      (footprint "eagle-import:DIL16")
      (libsource (lib "eagle-import") (part "74151NHC"))
    )
    (comp (ref "IC48")
      (value "74HCT32N")
      (footprint "eagle-import:DIL14")
      (libsource (lib "eagle-import") (part "7432NHCT"))
    )
    (comp (ref "IC49")
      (value "74HCT32N")
      (footprint "eagle-import:DIL14")
      (libsource (lib "eagle-import") (part "7432NHCT"))
    )
    (comp (ref "IC50")
      (value "74HC151N")
      (footprint "eagle-import:DIL16")
      (libsource (lib "eagle-import") (part "74151NHC"))
    )
    (comp (ref "IC51")
      (value "74HC151N")
      (footprint "eagle-import:DIL16")
      (libsource (lib "eagle-import") (part "74151NHC"))
    )
    (comp (ref "IC52")
      (value "74HCT08N")
      (footprint "eagle-import:DIL14")
      (libsource (lib "eagle-import") (part "7408NHCT"))
    )
    (comp (ref "IC53")
      (value "74HC74N")
      (footprint "eagle-import:DIL14")
      (libsource (lib "eagle-import") (part "7474NHC"))
    )
    (comp (ref "IC54")
      (value "74HC74N")
      (footprint "eagle-import:DIL14")
      (libsource (lib "eagle-import") (part "7474NHC"))
    )
    (comp (ref "IC55")
      (value "74HCT32N")
      (footprint "eagle-import:DIL14")
      (libsource (lib "eagle-import") (part "7432NHCT"))
    )
    (comp (ref "IC56")
      (value "74HCT32N")
      (footprint "eagle-import:DIL14")
      (libsource (lib "eagle-import") (part "7432NHCT"))
    )
    (comp (ref "IC57")
      (value "74HC193N")
      (footprint "eagle-import:DIL16")
      (libsource (lib "eagle-import") (part "74193NHC"))
    )
    (comp (ref "IC58")
      (value "74HC193N")
      (footprint "eagle-import:DIL16")
      (libsource (lib "eagle-import") (part "74193NHC"))
    )
    (comp (ref "IC59")
      (value "74HCT08N")
      (footprint "eagle-import:DIL14")
      (libsource (lib "eagle-import") (part "7408NHCT"))
    )
    (comp (ref "IC60")
      (value "74HC193N")
      (footprint "eagle-import:DIL16")
      (libsource (lib "eagle-import") (part "74193NHC"))
    )
    (comp (ref "IC61")
      (value "74HC193N")
      (footprint "eagle-import:DIL16")
      (libsource (lib "eagle-import") (part "74193NHC"))
    )
    (comp (ref "IC63")
      (value "74HCT08N")
      (footprint "eagle-import:DIL14")
      (libsource (lib "eagle-import") (part "7408NHCT"))
    )
    (comp (ref "IC64")
      (value "74HC193N")
      (footprint "eagle-import:DIL16")
      (libsource (lib "eagle-import") (part "74193NHC"))
    )
    (comp (ref "IC65")
      (value "74HCT32N")
      (footprint "eagle-import:DIL14")
      (libsource (lib "eagle-import") (part "7432NHCT"))
    )
    (comp (ref "IC67")
      (value "74HCT04N")
      (footprint "eagle-import:DIL14")
      (libsource (lib "eagle-import") (part "7404NHCT"))
    )
    (comp (ref "IC68")
      (value "74HCT32N")
      (footprint "eagle-import:DIL14")
      (libsource (lib "eagle-import") (part "7432NHCT"))
    )
    (comp (ref "IC69")
      (value "74HC193N")
      (footprint "eagle-import:DIL16")
      (libsource (lib "eagle-import") (part "74193NHC"))
    )
    (comp (ref "IC70")
      (value "74HCT32N")
      (footprint "eagle-import:DIL14")
      (libsource (lib "eagle-import") (part "7432NHCT"))
    )
    (comp (ref "IC71")
      (value "74HCT32N")
      (footprint "eagle-import:DIL14")
      (libsource (lib "eagle-import") (part "7432NHCT"))
    )
    (comp (ref "IC72")
      (value "74HCT08N")
      (footprint "eagle-import:DIL14")
      (libsource (lib "eagle-import") (part "7408NHCT"))
    )
    (comp (ref "IC73")
      (value "74HCT374N")
      (footprint "eagle-import:DIL20")
      (libsource (lib "eagle-import") (part "74374NHCT"))
    )
    (comp (ref "IC74")
      (value "74HC193N")
      (footprint "eagle-import:DIL16")
      (libsource (lib "eagle-import") (part "74193NHC"))
    )
    (comp (ref "IC75")
      (value "74HC193N")
      (footprint "eagle-import:DIL16")
      (libsource (lib "eagle-import") (part "74193NHC"))
    )
    (comp (ref "IC77")
      (value "74AC08N")
      (footprint "eagle-import:DIL14")
      (libsource (lib "eagle-import") (part "7408NAC"))
    )
    (comp (ref "IC78")
      (value "74HCT08N")
      (footprint "eagle-import:DIL14")
      (libsource (lib "eagle-import") (part "7408NHCT"))
    )
    (comp (ref "IC79")
      (value "74HCT374N")
      (footprint "eagle-import:DIL20")
      (libsource (lib "eagle-import") (part "74374NHCT"))
    )
    (comp (ref "IC80")
      (value "74HC193N")
      (footprint "eagle-import:DIL16")
      (libsource (lib "eagle-import") (part "74193NHC"))
    )
    (comp (ref "IC81")
      (value "74HCT374N")
      (footprint "eagle-import:DIL20")
      (libsource (lib "eagle-import") (part "74374NHCT"))
    )
    (comp (ref "IC82")
      (value "74AC08N")
      (footprint "eagle-import:DIL14")
      (libsource (lib "eagle-import") (part "7408NAC"))
    )
    (comp (ref "IC83")
      (value "74AC08N")
      (footprint "eagle-import:DIL14")
      (libsource (lib "eagle-import") (part "7408NAC"))
    )
    (comp (ref "IC85")
      (value "74HCT374N")
      (footprint "eagle-import:DIL20")
      (libsource (lib "eagle-import") (part "74374NHCT"))
    )
    (comp (ref "IC86")
      (value "74HCT04N")
      (footprint "eagle-import:DIL14")
      (libsource (lib "eagle-import") (part "7404NHCT"))
    )
    (comp (ref "IC87")
      (value "74AC08N")
      (footprint "eagle-import:DIL14")
      (libsource (lib "eagle-import") (part "7408NAC"))
    )
    (comp (ref "IC88")
      (value "74HCT08N")
      (footprint "eagle-import:DIL14")
      (libsource (lib "eagle-import") (part "7408NHCT"))
    )
    (comp (ref "IC89")
      (value "74HCT08N")
      (footprint "eagle-import:DIL14")
      (libsource (lib "eagle-import") (part "7408NHCT"))
    )
    (comp (ref "IC90")
      (value "74AC08N")
      (footprint "eagle-import:DIL14")
      (libsource (lib "eagle-import") (part "7408NAC"))
    )
    (comp (ref "IC91")
      (value "74AC08N")
      (footprint "eagle-import:DIL14")
      (libsource (lib "eagle-import") (part "7408NAC"))
    )
    (comp (ref "IC92")
      (value "74HCT08N")
      (footprint "eagle-import:DIL14")
      (libsource (lib "eagle-import") (part "7408NHCT"))
    )
    (comp (ref "IC93")
      (value "74HC193N")
      (footprint "eagle-import:DIL16")
      (libsource (lib "eagle-import") (part "74193NHC"))
    )
    (comp (ref "IC94")
      (value "74HCT32N")
      (footprint "eagle-import:DIL14")
      (libsource (lib "eagle-import") (part "7432NHCT"))
    )
    (comp (ref "IC95")
      (value "74AC08N")
      (footprint "eagle-import:DIL14")
      (libsource (lib "eagle-import") (part "7408NAC"))
    )
    (comp (ref "IC96")
      (value "74HCT32N")
      (footprint "eagle-import:DIL14")
      (libsource (lib "eagle-import") (part "7432NHCT"))
    )
    (comp (ref "IC97")
      (value "74HC193N")
      (footprint "eagle-import:DIL16")
      (libsource (lib "eagle-import") (part "74193NHC"))
    )
    (comp (ref "IC99")
      (value "74HCT08N")
      (footprint "eagle-import:DIL14")
      (libsource (lib "eagle-import") (part "7408NHCT"))
    )
    (comp (ref "IC100")
      (value "74HCT08N")
      (footprint "eagle-import:DIL14")
      (libsource (lib "eagle-import") (part "7408NHCT"))
    )
    (comp (ref "IC101")
      (value "74HC373N")
      (footprint "eagle-import:DIL20")
      (libsource (lib "eagle-import") (part "74373NHC"))
    )
    (comp (ref "IC102")
      (value "74HC193N")
      (footprint "eagle-import:DIL16")
      (libsource (lib "eagle-import") (part "74193NHC"))
    )
    (comp (ref "IC103")
      (value "74HC373N")
      (footprint "eagle-import:DIL20")
      (libsource (lib "eagle-import") (part "74373NHC"))
    )
    (comp (ref "IC105")
      (value "74HC74N")
      (footprint "eagle-import:DIL14")
      (libsource (lib "eagle-import") (part "7474NHC"))
    )
    (comp (ref "IC106")
      (value "74HC193N")
      (footprint "eagle-import:DIL16")
      (libsource (lib "eagle-import") (part "74193NHC"))
    )
    (comp (ref "IC108")
      (value "74HCT08N")
      (footprint "eagle-import:DIL14")
      (libsource (lib "eagle-import") (part "7408NHCT"))
    )
    (comp (ref "IC112")
      (value "74HCT32N")
      (footprint "eagle-import:DIL14")
      (libsource (lib "eagle-import") (part "7432NHCT"))
    )
    (comp (ref "IC126")
      (value "74HCT08N")
      (footprint "eagle-import:DIL14")
      (libsource (lib "eagle-import") (part "7408NHCT"))
    )
    (comp (ref "IC129")
      (value "74HCT04N")
      (footprint "eagle-import:DIL14")
      (libsource (lib "eagle-import") (part "7404NHCT"))
    )
    (comp (ref "IC130")
      (value "74HCT08N")
      (footprint "eagle-import:DIL14")
      (libsource (lib "eagle-import") (part "7408NHCT"))
    )
    (comp (ref "IC131")
      (value "74HC74N")
      (footprint "eagle-import:DIL14")
      (libsource (lib "eagle-import") (part "7474NHC"))
    )
    (comp (ref "JP1")
      (value "PINHD-2X15")
      (footprint "eagle-import:2X15")
      (libsource (lib "eagle-import") (part "PINHD-2X15"))
    )
    (comp (ref "JP2")
      (value "PINHD-2X15")
      (footprint "eagle-import:2X15")
      (libsource (lib "eagle-import") (part "PINHD-2X15"))
    )
    (comp (ref "JP3")
      (value "PINHD-2X20")
      (footprint "eagle-import:2X20")
      (libsource (lib "eagle-import") (part "PINHD-2X20"))
    )
    (comp (ref "JP4")
      (value "PINHD-2X20")
      (footprint "eagle-import:2X20")
      (libsource (lib "eagle-import") (part "PINHD-2X20"))
    )
    (comp (ref "JP5")
      (value "PINHD-2X20")
      (footprint "eagle-import:2X20")
      (libsource (lib "eagle-import") (part "PINHD-2X20"))
    )
  )
  (nets
    (net (code "25") (name "/ADRR_0") (class "Default")
      (node (ref "IC13") (pin "4") (pinfunction "1Y_4") (pintype "output"))
      (node (ref "JP1") (pin "1") (pinfunction "1_1") (pintype "passive"))
    )
    (net (code "26") (name "/ADRR_1") (class "Default")
      (node (ref "IC13") (pin "7") (pinfunction "2Y_7") (pintype "output"))
      (node (ref "JP1") (pin "3") (pinfunction "3_3") (pintype "passive"))
    )
    (net (code "27") (name "/ADRR_2") (class "Default")
      (node (ref "IC13") (pin "9") (pinfunction "3Y_9") (pintype "output"))
      (node (ref "JP1") (pin "5") (pinfunction "5_5") (pintype "passive"))
    )
    (net (code "28") (name "/ADRR_3") (class "Default")
      (node (ref "IC13") (pin "12") (pinfunction "4Y_12") (pintype "output"))
      (node (ref "JP1") (pin "7") (pinfunction "7_7") (pintype "passive"))
    )
    (net (code "29") (name "/ADRR_4") (class "Default")
      (node (ref "IC21") (pin "4") (pinfunction "1Y_4") (pintype "output"))
      (node (ref "JP1") (pin "9") (pinfunction "9_9") (pintype "passive"))
    )
    (net (code "30") (name "/ADRR_5") (class "Default")
      (node (ref "IC21") (pin "7") (pinfunction "2Y_7") (pintype "output"))
      (node (ref "JP1") (pin "11") (pinfunction "11_11") (pintype "passive"))
    )
    (net (code "31") (name "/ADRR_6") (class "Default")
      (node (ref "IC21") (pin "9") (pinfunction "3Y_9") (pintype "output"))
      (node (ref "JP1") (pin "13") (pinfunction "13_13") (pintype "passive"))
    )
    (net (code "32") (name "/ADRR_7") (class "Default")
      (node (ref "IC21") (pin "12") (pinfunction "4Y_12") (pintype "output"))
      (node (ref "JP1") (pin "15") (pinfunction "15_15") (pintype "passive"))
    )
    (net (code "33") (name "/ADRR_8") (class "Default")
      (node (ref "IC27") (pin "4") (pinfunction "1Y_4") (pintype "output"))
      (node (ref "JP1") (pin "17") (pinfunction "17_17") (pintype "passive"))
    )
    (net (code "34") (name "/ADRR_9") (class "Default")
      (node (ref "IC27") (pin "7") (pinfunction "2Y_7") (pintype "output"))
      (node (ref "JP1") (pin "19") (pinfunction "19_19") (pintype "passive"))
    )
    (net (code "35") (name "/ADRR_10") (class "Default")
      (node (ref "IC27") (pin "9") (pinfunction "3Y_9") (pintype "output"))
      (node (ref "JP1") (pin "21") (pinfunction "21_21") (pintype "passive"))
    )
    (net (code "36") (name "/ADRR_11") (class "Default")
      (node (ref "IC27") (pin "12") (pinfunction "4Y_12") (pintype "output"))
      (node (ref "JP1") (pin "23") (pinfunction "23_23") (pintype "passive"))
    )
    (net (code "37") (name "/ADRR_12") (class "Default")
      (node (ref "IC34") (pin "4") (pinfunction "1Y_4") (pintype "output"))
      (node (ref "JP1") (pin "25") (pinfunction "25_25") (pintype "passive"))
    )
    (net (code "38") (name "/ADRR_13") (class "Default")
      (node (ref "IC34") (pin "7") (pinfunction "2Y_7") (pintype "output"))
      (node (ref "JP1") (pin "27") (pinfunction "27_27") (pintype "passive"))
    )
    (net (code "39") (name "/ADRR_14") (class "Default")
      (node (ref "IC34") (pin "9") (pinfunction "3Y_9") (pintype "output"))
      (node (ref "JP1") (pin "29") (pinfunction "29_29") (pintype "passive"))
    )
    (net (code "40") (name "/ADRR_15") (class "Default")
      (node (ref "IC34") (pin "12") (pinfunction "4Y_12") (pintype "output"))
      (node (ref "IC67") (pin "5") (pinfunction "I_5") (pintype "input"))
      (node (ref "IC68") (pin "9") (pinfunction "I0_9") (pintype "input"))
    )
    (net (code "42") (name "/ALU_CARRY_BIT") (class "Default")
      (node (ref "IC131") (pin "5") (pinfunction "Q_5") (pintype "output"))
      (node (ref "IC78") (pin "12") (pinfunction "I0_12") (pintype "input"))
      (node (ref "IC89") (pin "4") (pinfunction "I0_4") (pintype "input"))
      (node (ref "JP4") (pin "16") (pinfunction "16_16") (pintype "passive"))
    )
    (net (code "43") (name "/ALU_CARRY_IN") (class "Default")
      (node (ref "IC89") (pin "6") (pinfunction "O_6") (pintype "output"))
      (node (ref "JP5") (pin "34") (pinfunction "34_34") (pintype "passive"))
    )
    (net (code "44") (name "/ALU_CARRY_OUT") (class "Default")
      (node (ref "IC131") (pin "2") (pinfunction "D_2") (pintype "input"))
      (node (ref "IC72") (pin "5") (pinfunction "I1_5") (pintype "input"))
      (node (ref "IC99") (pin "9") (pinfunction "I0_9") (pintype "input"))
      (node (ref "JP5") (pin "32") (pinfunction "32_32") (pintype "passive"))
    )
    (net (code "45") (name "/ALU_NR1_ENABLE_ALU") (class "Default")
      (node (ref "IC49") (pin "9") (pinfunction "I0_9") (pintype "input"))
      (node (ref "IC70") (pin "1") (pinfunction "I0_1") (pintype "input"))
      (node (ref "IC77") (pin "3") (pinfunction "O_3") (pintype "output"))
    )
    (net (code "46") (name "/ALU_NR1_ENABLE_JMP_O") (class "Default")
      (node (ref "IC49") (pin "10") (pinfunction "I1_10") (pintype "input"))
      (node (ref "IC59") (pin "8") (pinfunction "O_8") (pintype "output"))
    )
    (net (code "47") (name "/ALU_NR2_ENABLE_ALU") (class "Default")
      (node (ref "IC49") (pin "12") (pinfunction "I0_12") (pintype "input"))
      (node (ref "IC70") (pin "2") (pinfunction "I1_2") (pintype "input"))
      (node (ref "IC77") (pin "6") (pinfunction "O_6") (pintype "output"))
    )
    (net (code "48") (name "/ALU_NR2_ENABLE_JMP_O") (class "Default")
      (node (ref "IC108") (pin "8") (pinfunction "O_8") (pintype "output"))
      (node (ref "IC49") (pin "13") (pinfunction "I1_13") (pintype "input"))
    )
    (net (code "49") (name "/ALU_NR3_ENABLE_ALU") (class "Default")
      (node (ref "IC70") (pin "4") (pinfunction "I0_4") (pintype "input"))
      (node (ref "IC77") (pin "8") (pinfunction "O_8") (pintype "output"))
      (node (ref "JP5") (pin "26") (pinfunction "26_26") (pintype "passive"))
    )
    (net (code "50") (name "/ALU_NR4_ENABLE_ALU") (class "Default")
      (node (ref "IC70") (pin "5") (pinfunction "I1_5") (pintype "input"))
      (node (ref "IC77") (pin "11") (pinfunction "O_11") (pintype "output"))
      (node (ref "JP5") (pin "24") (pinfunction "24_24") (pintype "passive"))
    )
    (net (code "51") (name "/ALU_OUTPUT_ENABLE{slash}FILL_PC_L_JMP_O") (class "Default")
      (node (ref "IC40") (pin "3") (pinfunction "O_3") (pintype "output"))
      (node (ref "IC49") (pin "2") (pinfunction "I1_2") (pintype "input"))
      (node (ref "IC56") (pin "12") (pinfunction "I0_12") (pintype "input"))
    )
    (net (code "52") (name "/CARRY&&IR_DATA") (class "Default")
      (node (ref "IC72") (pin "6") (pinfunction "O_6") (pintype "output"))
      (node (ref "IC88") (pin "4") (pinfunction "I0_4") (pintype "input"))
    )
    (net (code "53") (name "/CARRY&&~{IR_DATA}") (class "Default")
      (node (ref "IC88") (pin "12") (pinfunction "I0_12") (pintype "input"))
      (node (ref "IC99") (pin "8") (pinfunction "O_8") (pintype "output"))
    )
    (net (code "54") (name "/CLR_NOT_CS{slash}CLR_NOT_WE_PUSH") (class "Default")
      (node (ref "IC126") (pin "6") (pinfunction "O_6") (pintype "output"))
      (node (ref "IC19") (pin "8") (pinfunction "I0_8") (pintype "input"))
      (node (ref "IC67") (pin "1") (pinfunction "I_1") (pintype "input"))
    )
    (net (code "55") (name "/CLR_NOT_OE{slash}CLR_NOT_CS_POP{slash}FILL_REGISTER_POP") (class "Default")
      (node (ref "IC100") (pin "6") (pinfunction "O_6") (pintype "output"))
      (node (ref "IC19") (pin "9") (pinfunction "I1_9") (pintype "input"))
      (node (ref "IC96") (pin "4") (pinfunction "I0_4") (pintype "input"))
      (node (ref "JP2") (pin "4") (pinfunction "4_4") (pintype "passive"))
    )
    (net (code "56") (name "/CLR_NOT_OE{slash}CLR_NOT_CS{slash}PC_COUNT_UP_CYCL_2") (class "Default")
      (node (ref "IC53") (pin "9") (pinfunction "Q_9") (pintype "output"))
      (node (ref "IC55") (pin "12") (pinfunction "I0_12") (pintype "input"))
      (node (ref "IC55") (pin "4") (pinfunction "I0_4") (pintype "input"))
      (node (ref "JP4") (pin "28") (pinfunction "28_28") (pintype "passive"))
    )
    (net (code "57") (name "/CLR_NOT_OE{slash}PC_COUNT_UP{slash}CLR_NOT_CS_CYCL_1") (class "Default")
      (node (ref "IC53") (pin "5") (pinfunction "Q_5") (pintype "output"))
      (node (ref "IC55") (pin "5") (pinfunction "I1_5") (pintype "input"))
      (node (ref "IC89") (pin "12") (pinfunction "I0_12") (pintype "input"))
      (node (ref "IC89") (pin "9") (pinfunction "I0_9") (pintype "input"))
      (node (ref "JP4") (pin "26") (pinfunction "26_26") (pintype "passive"))
    )
    (net (code "58") (name "/CYCLE1{slash}CYLCE2") (class "Default")
      (node (ref "IC19") (pin "6") (pinfunction "I1_6") (pintype "input"))
      (node (ref "IC39") (pin "11") (pinfunction "I0_11") (pintype "input"))
      (node (ref "IC55") (pin "6") (pinfunction "O_6") (pintype "output"))
      (node (ref "IC68") (pin "4") (pinfunction "I0_4") (pintype "input"))
    )
    (net (code "59") (name "/DATA0") (class "Default")
      (node (ref "IC101") (pin "2") (pinfunction "1Q_2") (pintype "tri_state"))
      (node (ref "IC103") (pin "3") (pinfunction "1D_3") (pintype "input"))
      (node (ref "IC17") (pin "15") (pinfunction "A_15") (pintype "input"))
      (node (ref "IC18") (pin "3") (pinfunction "1D_3") (pintype "input"))
      (node (ref "IC26") (pin "3") (pinfunction "1D_3") (pintype "input"))
      (node (ref "IC33") (pin "3") (pinfunction "1D_3") (pintype "input"))
      (node (ref "IC35") (pin "2") (pinfunction "1Q_2") (pintype "tri_state"))
      (node (ref "IC36") (pin "2") (pinfunction "1Q_2") (pintype "tri_state"))
      (node (ref "IC41") (pin "3") (pinfunction "1D_3") (pintype "input"))
      (node (ref "IC45") (pin "3") (pinfunction "1D_3") (pintype "input"))
      (node (ref "IC5") (pin "3") (pinfunction "1D_3") (pintype "input"))
      (node (ref "IC57") (pin "15") (pinfunction "A_15") (pintype "input"))
      (node (ref "IC60") (pin "15") (pinfunction "A_15") (pintype "input"))
      (node (ref "IC69") (pin "15") (pinfunction "A_15") (pintype "input"))
      (node (ref "IC73") (pin "3") (pinfunction "1D_3") (pintype "input"))
      (node (ref "IC79") (pin "3") (pinfunction "1D_3") (pintype "input"))
      (node (ref "IC81") (pin "3") (pinfunction "1D_3") (pintype "input"))
      (node (ref "IC85") (pin "3") (pinfunction "1D_3") (pintype "input"))
      (node (ref "JP1") (pin "2") (pinfunction "2_2") (pintype "passive"))
      (node (ref "JP5") (pin "23") (pinfunction "23_23") (pintype "passive"))
    )
    (net (code "60") (name "/DATA1") (class "Default")
      (node (ref "IC101") (pin "5") (pinfunction "2Q_5") (pintype "tri_state"))
      (node (ref "IC103") (pin "4") (pinfunction "2D_4") (pintype "input"))
      (node (ref "IC17") (pin "1") (pinfunction "B_1") (pintype "input"))
      (node (ref "IC18") (pin "4") (pinfunction "2D_4") (pintype "input"))
      (node (ref "IC26") (pin "4") (pinfunction "2D_4") (pintype "input"))
      (node (ref "IC33") (pin "4") (pinfunction "2D_4") (pintype "input"))
      (node (ref "IC35") (pin "5") (pinfunction "2Q_5") (pintype "tri_state"))
      (node (ref "IC36") (pin "5") (pinfunction "2Q_5") (pintype "tri_state"))
      (node (ref "IC41") (pin "4") (pinfunction "2D_4") (pintype "input"))
      (node (ref "IC45") (pin "4") (pinfunction "2D_4") (pintype "input"))
      (node (ref "IC5") (pin "4") (pinfunction "2D_4") (pintype "input"))
      (node (ref "IC57") (pin "1") (pinfunction "B_1") (pintype "input"))
      (node (ref "IC60") (pin "1") (pinfunction "B_1") (pintype "input"))
      (node (ref "IC69") (pin "1") (pinfunction "B_1") (pintype "input"))
      (node (ref "IC73") (pin "4") (pinfunction "2D_4") (pintype "input"))
      (node (ref "IC79") (pin "4") (pinfunction "2D_4") (pintype "input"))
      (node (ref "IC81") (pin "4") (pinfunction "2D_4") (pintype "input"))
      (node (ref "IC85") (pin "4") (pinfunction "2D_4") (pintype "input"))
      (node (ref "JP1") (pin "4") (pinfunction "4_4") (pintype "passive"))
      (node (ref "JP5") (pin "25") (pinfunction "25_25") (pintype "passive"))
    )
    (net (code "61") (name "/DATA2") (class "Default")
      (node (ref "IC101") (pin "6") (pinfunction "3Q_6") (pintype "tri_state"))
      (node (ref "IC103") (pin "7") (pinfunction "3D_7") (pintype "input"))
      (node (ref "IC17") (pin "10") (pinfunction "C_10") (pintype "input"))
      (node (ref "IC18") (pin "7") (pinfunction "3D_7") (pintype "input"))
      (node (ref "IC26") (pin "7") (pinfunction "3D_7") (pintype "input"))
      (node (ref "IC33") (pin "7") (pinfunction "3D_7") (pintype "input"))
      (node (ref "IC35") (pin "6") (pinfunction "3Q_6") (pintype "tri_state"))
      (node (ref "IC36") (pin "6") (pinfunction "3Q_6") (pintype "tri_state"))
      (node (ref "IC41") (pin "7") (pinfunction "3D_7") (pintype "input"))
      (node (ref "IC45") (pin "7") (pinfunction "3D_7") (pintype "input"))
      (node (ref "IC5") (pin "7") (pinfunction "3D_7") (pintype "input"))
      (node (ref "IC57") (pin "10") (pinfunction "C_10") (pintype "input"))
      (node (ref "IC60") (pin "10") (pinfunction "C_10") (pintype "input"))
      (node (ref "IC69") (pin "10") (pinfunction "C_10") (pintype "input"))
      (node (ref "IC73") (pin "7") (pinfunction "3D_7") (pintype "input"))
      (node (ref "IC79") (pin "7") (pinfunction "3D_7") (pintype "input"))
      (node (ref "IC81") (pin "7") (pinfunction "3D_7") (pintype "input"))
      (node (ref "IC85") (pin "7") (pinfunction "3D_7") (pintype "input"))
      (node (ref "JP1") (pin "6") (pinfunction "6_6") (pintype "passive"))
      (node (ref "JP5") (pin "27") (pinfunction "27_27") (pintype "passive"))
    )
    (net (code "62") (name "/DATA3") (class "Default")
      (node (ref "IC101") (pin "9") (pinfunction "4Q_9") (pintype "tri_state"))
      (node (ref "IC103") (pin "8") (pinfunction "4D_8") (pintype "input"))
      (node (ref "IC17") (pin "9") (pinfunction "D_9") (pintype "input"))
      (node (ref "IC18") (pin "8") (pinfunction "4D_8") (pintype "input"))
      (node (ref "IC26") (pin "8") (pinfunction "4D_8") (pintype "input"))
      (node (ref "IC33") (pin "8") (pinfunction "4D_8") (pintype "input"))
      (node (ref "IC35") (pin "9") (pinfunction "4Q_9") (pintype "tri_state"))
      (node (ref "IC36") (pin "9") (pinfunction "4Q_9") (pintype "tri_state"))
      (node (ref "IC41") (pin "8") (pinfunction "4D_8") (pintype "input"))
      (node (ref "IC45") (pin "8") (pinfunction "4D_8") (pintype "input"))
      (node (ref "IC5") (pin "8") (pinfunction "4D_8") (pintype "input"))
      (node (ref "IC57") (pin "9") (pinfunction "D_9") (pintype "input"))
      (node (ref "IC60") (pin "9") (pinfunction "D_9") (pintype "input"))
      (node (ref "IC69") (pin "9") (pinfunction "D_9") (pintype "input"))
      (node (ref "IC73") (pin "8") (pinfunction "4D_8") (pintype "input"))
      (node (ref "IC79") (pin "8") (pinfunction "4D_8") (pintype "input"))
      (node (ref "IC81") (pin "8") (pinfunction "4D_8") (pintype "input"))
      (node (ref "IC85") (pin "8") (pinfunction "4D_8") (pintype "input"))
      (node (ref "JP1") (pin "8") (pinfunction "8_8") (pintype "passive"))
      (node (ref "JP5") (pin "29") (pinfunction "29_29") (pintype "passive"))
    )
    (net (code "63") (name "/DATA4") (class "Default")
      (node (ref "IC101") (pin "12") (pinfunction "5Q_12") (pintype "tri_state"))
      (node (ref "IC103") (pin "13") (pinfunction "5D_13") (pintype "input"))
      (node (ref "IC18") (pin "13") (pinfunction "5D_13") (pintype "input"))
      (node (ref "IC26") (pin "13") (pinfunction "5D_13") (pintype "input"))
      (node (ref "IC33") (pin "13") (pinfunction "5D_13") (pintype "input"))
      (node (ref "IC35") (pin "12") (pinfunction "5Q_12") (pintype "tri_state"))
      (node (ref "IC36") (pin "12") (pinfunction "5Q_12") (pintype "tri_state"))
      (node (ref "IC41") (pin "13") (pinfunction "5D_13") (pintype "input"))
      (node (ref "IC45") (pin "13") (pinfunction "5D_13") (pintype "input"))
      (node (ref "IC5") (pin "13") (pinfunction "5D_13") (pintype "input"))
      (node (ref "IC58") (pin "15") (pinfunction "A_15") (pintype "input"))
      (node (ref "IC61") (pin "15") (pinfunction "A_15") (pintype "input"))
      (node (ref "IC64") (pin "15") (pinfunction "A_15") (pintype "input"))
      (node (ref "IC73") (pin "13") (pinfunction "5D_13") (pintype "input"))
      (node (ref "IC74") (pin "15") (pinfunction "A_15") (pintype "input"))
      (node (ref "IC79") (pin "13") (pinfunction "5D_13") (pintype "input"))
      (node (ref "IC81") (pin "13") (pinfunction "5D_13") (pintype "input"))
      (node (ref "IC85") (pin "13") (pinfunction "5D_13") (pintype "input"))
      (node (ref "JP1") (pin "10") (pinfunction "10_10") (pintype "passive"))
      (node (ref "JP5") (pin "31") (pinfunction "31_31") (pintype "passive"))
    )
    (net (code "64") (name "/DATA5") (class "Default")
      (node (ref "IC101") (pin "15") (pinfunction "6Q_15") (pintype "tri_state"))
      (node (ref "IC103") (pin "14") (pinfunction "6D_14") (pintype "input"))
      (node (ref "IC18") (pin "14") (pinfunction "6D_14") (pintype "input"))
      (node (ref "IC26") (pin "14") (pinfunction "6D_14") (pintype "input"))
      (node (ref "IC33") (pin "14") (pinfunction "6D_14") (pintype "input"))
      (node (ref "IC35") (pin "15") (pinfunction "6Q_15") (pintype "tri_state"))
      (node (ref "IC36") (pin "15") (pinfunction "6Q_15") (pintype "tri_state"))
      (node (ref "IC41") (pin "14") (pinfunction "6D_14") (pintype "input"))
      (node (ref "IC45") (pin "14") (pinfunction "6D_14") (pintype "input"))
      (node (ref "IC5") (pin "14") (pinfunction "6D_14") (pintype "input"))
      (node (ref "IC58") (pin "1") (pinfunction "B_1") (pintype "input"))
      (node (ref "IC61") (pin "1") (pinfunction "B_1") (pintype "input"))
      (node (ref "IC64") (pin "1") (pinfunction "B_1") (pintype "input"))
      (node (ref "IC73") (pin "14") (pinfunction "6D_14") (pintype "input"))
      (node (ref "IC74") (pin "1") (pinfunction "B_1") (pintype "input"))
      (node (ref "IC79") (pin "14") (pinfunction "6D_14") (pintype "input"))
      (node (ref "IC81") (pin "14") (pinfunction "6D_14") (pintype "input"))
      (node (ref "IC85") (pin "14") (pinfunction "6D_14") (pintype "input"))
      (node (ref "JP1") (pin "12") (pinfunction "12_12") (pintype "passive"))
      (node (ref "JP5") (pin "33") (pinfunction "33_33") (pintype "passive"))
    )
    (net (code "65") (name "/DATA6") (class "Default")
      (node (ref "IC101") (pin "16") (pinfunction "7Q_16") (pintype "tri_state"))
      (node (ref "IC103") (pin "17") (pinfunction "7D_17") (pintype "input"))
      (node (ref "IC18") (pin "17") (pinfunction "7D_17") (pintype "input"))
      (node (ref "IC26") (pin "17") (pinfunction "7D_17") (pintype "input"))
      (node (ref "IC33") (pin "17") (pinfunction "7D_17") (pintype "input"))
      (node (ref "IC35") (pin "16") (pinfunction "7Q_16") (pintype "tri_state"))
      (node (ref "IC36") (pin "16") (pinfunction "7Q_16") (pintype "tri_state"))
      (node (ref "IC41") (pin "17") (pinfunction "7D_17") (pintype "input"))
      (node (ref "IC45") (pin "17") (pinfunction "7D_17") (pintype "input"))
      (node (ref "IC5") (pin "17") (pinfunction "7D_17") (pintype "input"))
      (node (ref "IC58") (pin "10") (pinfunction "C_10") (pintype "input"))
      (node (ref "IC61") (pin "10") (pinfunction "C_10") (pintype "input"))
      (node (ref "IC64") (pin "10") (pinfunction "C_10") (pintype "input"))
      (node (ref "IC73") (pin "17") (pinfunction "7D_17") (pintype "input"))
      (node (ref "IC74") (pin "10") (pinfunction "C_10") (pintype "input"))
      (node (ref "IC79") (pin "17") (pinfunction "7D_17") (pintype "input"))
      (node (ref "IC81") (pin "17") (pinfunction "7D_17") (pintype "input"))
      (node (ref "IC85") (pin "17") (pinfunction "7D_17") (pintype "input"))
      (node (ref "JP1") (pin "14") (pinfunction "14_14") (pintype "passive"))
      (node (ref "JP5") (pin "35") (pinfunction "35_35") (pintype "passive"))
    )
    (net (code "66") (name "/DATA7") (class "Default")
      (node (ref "IC101") (pin "19") (pinfunction "8Q_19") (pintype "tri_state"))
      (node (ref "IC103") (pin "18") (pinfunction "8D_18") (pintype "input"))
      (node (ref "IC18") (pin "18") (pinfunction "8D_18") (pintype "input"))
      (node (ref "IC26") (pin "18") (pinfunction "8D_18") (pintype "input"))
      (node (ref "IC33") (pin "18") (pinfunction "8D_18") (pintype "input"))
      (node (ref "IC35") (pin "19") (pinfunction "8Q_19") (pintype "tri_state"))
      (node (ref "IC36") (pin "19") (pinfunction "8Q_19") (pintype "tri_state"))
      (node (ref "IC41") (pin "18") (pinfunction "8D_18") (pintype "input"))
      (node (ref "IC45") (pin "18") (pinfunction "8D_18") (pintype "input"))
      (node (ref "IC5") (pin "18") (pinfunction "8D_18") (pintype "input"))
      (node (ref "IC58") (pin "9") (pinfunction "D_9") (pintype "input"))
      (node (ref "IC61") (pin "9") (pinfunction "D_9") (pintype "input"))
      (node (ref "IC64") (pin "9") (pinfunction "D_9") (pintype "input"))
      (node (ref "IC73") (pin "18") (pinfunction "8D_18") (pintype "input"))
      (node (ref "IC74") (pin "9") (pinfunction "D_9") (pintype "input"))
      (node (ref "IC79") (pin "18") (pinfunction "8D_18") (pintype "input"))
      (node (ref "IC81") (pin "18") (pinfunction "8D_18") (pintype "input"))
      (node (ref "IC85") (pin "18") (pinfunction "8D_18") (pintype "input"))
      (node (ref "JP1") (pin "16") (pinfunction "16_16") (pintype "passive"))
      (node (ref "JP5") (pin "37") (pinfunction "37_37") (pintype "passive"))
    )
    (net (code "68") (name "/DBUS_SELECTOR_TABLE_2") (class "Default")
      (node (ref "IC11") (pin "1") (pinfunction "~{A}/B_1") (pintype "input"))
      (node (ref "IC55") (pin "8") (pinfunction "O_8") (pintype "output"))
    )
    (net (code "69") (name "/ENABLE_ALU_OUTPUT") (class "Default")
      (node (ref "IC112") (pin "13") (pinfunction "I1_13") (pintype "input"))
      (node (ref "IC49") (pin "3") (pinfunction "O_3") (pintype "output"))
      (node (ref "IC67") (pin "11") (pinfunction "I_11") (pintype "input"))
    )
    (net (code "70") (name "/ENABLE_ALU_OUTPUT{slash}FILL_REGISTER_ALU") (class "Default")
      (node (ref "IC112") (pin "10") (pinfunction "I1_10") (pintype "input"))
      (node (ref "IC49") (pin "1") (pinfunction "I0_1") (pintype "input"))
      (node (ref "IC72") (pin "11") (pinfunction "O_11") (pintype "output"))
    )
    (net (code "71") (name "/FILL_LR_H{slash}COUNT_PC_DOWN_SAVE_LR") (class "Default")
      (node (ref "IC126") (pin "11") (pinfunction "O_11") (pintype "output"))
      (node (ref "IC129") (pin "9") (pinfunction "I_9") (pintype "input"))
      (node (ref "IC44") (pin "11") (pinfunction "I0_11") (pintype "input"))
    )
    (net (code "72") (name "/FILL_LR_L{slash}WRITE_PC_H_DBUS_SAVE_LR") (class "Default")
      (node (ref "IC44") (pin "8") (pinfunction "I0_8") (pintype "input"))
      (node (ref "IC65") (pin "13") (pinfunction "I1_13") (pintype "input"))
      (node (ref "IC92") (pin "6") (pinfunction "O_6") (pintype "output"))
    )
    (net (code "73") (name "/FILL_PC_H_RET") (class "Default")
      (node (ref "IC126") (pin "3") (pinfunction "O_3") (pintype "output"))
      (node (ref "IC56") (pin "4") (pinfunction "I0_4") (pintype "input"))
    )
    (net (code "74") (name "/FILL_PC_L{slash}WRITE_LR_H_DBUS_RET") (class "Default")
      (node (ref "IC100") (pin "3") (pinfunction "O_3") (pintype "output"))
      (node (ref "IC56") (pin "10") (pinfunction "I1_10") (pintype "input"))
      (node (ref "IC65") (pin "2") (pinfunction "I1_2") (pintype "input"))
      (node (ref "IC65") (pin "4") (pinfunction "I0_4") (pintype "input"))
    )
    (net (code "75") (name "/FILL_PTR_H_SET_PTR") (class "Default")
      (node (ref "IC39") (pin "6") (pinfunction "I1_6") (pintype "input"))
      (node (ref "IC88") (pin "8") (pinfunction "O_8") (pintype "output"))
    )
    (net (code "76") (name "/FILL_PTR_L{slash}WRITE_REGB_TO_DBUS_SET_PTR") (class "Default")
      (node (ref "IC1") (pin "13") (pinfunction "I1_13") (pintype "input"))
      (node (ref "IC39") (pin "3") (pinfunction "I1_3") (pintype "input"))
      (node (ref "IC92") (pin "3") (pinfunction "O_3") (pintype "output"))
    )
    (net (code "77") (name "/FILL_REGISTER_MOV") (class "Default")
      (node (ref "IC108") (pin "3") (pinfunction "O_3") (pintype "output"))
      (node (ref "IC112") (pin "9") (pinfunction "I0_9") (pintype "input"))
    )
    (net (code "78") (name "/INPUT_REG0{slash}OPC4{slash}5_IS_NULL") (class "Default")
      (node (ref "IC2") (pin "1") (pinfunction "I0_1") (pintype "input"))
      (node (ref "IC2") (pin "4") (pinfunction "I0_4") (pintype "input"))
      (node (ref "IC24") (pin "1") (pinfunction "I0_1") (pintype "input"))
      (node (ref "IC24") (pin "4") (pinfunction "I0_4") (pintype "input"))
      (node (ref "IC28") (pin "3") (pinfunction "O_3") (pintype "output"))
      (node (ref "IC30") (pin "1") (pinfunction "I0_1") (pintype "input"))
      (node (ref "IC88") (pin "1") (pinfunction "I0_1") (pintype "input"))
      (node (ref "IC9") (pin "3") (pinfunction "1B_3") (pintype "input"))
      (node (ref "IC99") (pin "13") (pinfunction "I1_13") (pintype "input"))
    )
    (net (code "79") (name "/INPUT_REG1") (class "Default")
      (node (ref "IC2") (pin "12") (pinfunction "I0_12") (pintype "input"))
      (node (ref "IC2") (pin "9") (pinfunction "I0_9") (pintype "input"))
      (node (ref "IC24") (pin "12") (pinfunction "I0_12") (pintype "input"))
      (node (ref "IC24") (pin "9") (pinfunction "I0_9") (pintype "input"))
      (node (ref "IC28") (pin "6") (pinfunction "O_6") (pintype "output"))
      (node (ref "IC30") (pin "4") (pinfunction "I0_4") (pintype "input"))
      (node (ref "IC9") (pin "6") (pinfunction "2B_6") (pintype "input"))
    )
    (net (code "80") (name "/INPUT_REG2{slash}OPC_4{slash}5==11") (class "Default")
      (node (ref "IC10") (pin "1") (pinfunction "I0_1") (pintype "input"))
      (node (ref "IC10") (pin "4") (pinfunction "I0_4") (pintype "input"))
      (node (ref "IC28") (pin "8") (pinfunction "O_8") (pintype "output"))
      (node (ref "IC30") (pin "9") (pinfunction "I0_9") (pintype "input"))
      (node (ref "IC63") (pin "12") (pinfunction "I0_12") (pintype "input"))
      (node (ref "IC63") (pin "4") (pinfunction "I0_4") (pintype "input"))
      (node (ref "IC9") (pin "10") (pinfunction "3B_10") (pintype "input"))
    )
    (net (code "81") (name "/INPUT_REG3") (class "Default")
      (node (ref "IC10") (pin "12") (pinfunction "I0_12") (pintype "input"))
      (node (ref "IC10") (pin "9") (pinfunction "I0_9") (pintype "input"))
      (node (ref "IC28") (pin "11") (pinfunction "O_11") (pintype "output"))
      (node (ref "IC30") (pin "12") (pinfunction "I0_12") (pintype "input"))
      (node (ref "IC9") (pin "13") (pinfunction "4B_13") (pintype "input"))
    )
    (net (code "82") (name "/INPUT_REG_IS_NOT_OUTPUT_REG") (class "Default")
      (node (ref "IC19") (pin "3") (pinfunction "I1_3") (pintype "input"))
      (node (ref "IC6") (pin "1") (pinfunction "I0_1") (pintype "input"))
      (node (ref "IC6") (pin "12") (pinfunction "I0_12") (pintype "input"))
      (node (ref "IC6") (pin "4") (pinfunction "I0_4") (pintype "input"))
      (node (ref "IC6") (pin "9") (pinfunction "I0_9") (pintype "input"))
      (node (ref "IC71") (pin "6") (pinfunction "O_6") (pintype "output"))
      (node (ref "IC96") (pin "9") (pinfunction "I0_9") (pintype "input"))
    )
    (net (code "83") (name "/IO_INPUT1_0") (class "Default")
      (node (ref "IC3") (pin "12") (pinfunction "D7_12") (pintype "input"))
      (node (ref "JP3") (pin "2") (pinfunction "2_2") (pintype "passive"))
    )
    (net (code "84") (name "/IO_INPUT1_1") (class "Default")
      (node (ref "IC15") (pin "12") (pinfunction "D7_12") (pintype "input"))
      (node (ref "JP3") (pin "4") (pinfunction "4_4") (pintype "passive"))
    )
    (net (code "85") (name "/IO_INPUT1_2") (class "Default")
      (node (ref "IC22") (pin "12") (pinfunction "D7_12") (pintype "input"))
      (node (ref "JP3") (pin "6") (pinfunction "6_6") (pintype "passive"))
    )
    (net (code "86") (name "/IO_INPUT1_3") (class "Default")
      (node (ref "IC31") (pin "12") (pinfunction "D7_12") (pintype "input"))
      (node (ref "JP3") (pin "8") (pinfunction "8_8") (pintype "passive"))
    )
    (net (code "87") (name "/IO_INPUT1_4") (class "Default")
      (node (ref "IC37") (pin "12") (pinfunction "D7_12") (pintype "input"))
      (node (ref "JP3") (pin "10") (pinfunction "10_10") (pintype "passive"))
    )
    (net (code "88") (name "/IO_INPUT1_5") (class "Default")
      (node (ref "IC42") (pin "12") (pinfunction "D7_12") (pintype "input"))
      (node (ref "JP3") (pin "12") (pinfunction "12_12") (pintype "passive"))
    )
    (net (code "89") (name "/IO_INPUT1_6") (class "Default")
      (node (ref "IC46") (pin "12") (pinfunction "D7_12") (pintype "input"))
      (node (ref "JP3") (pin "14") (pinfunction "14_14") (pintype "passive"))
    )
    (net (code "90") (name "/IO_INPUT1_7") (class "Default")
      (node (ref "IC50") (pin "12") (pinfunction "D7_12") (pintype "input"))
      (node (ref "JP3") (pin "16") (pinfunction "16_16") (pintype "passive"))
    )
    (net (code "91") (name "/IO_INPUT2_0") (class "Default")
      (node (ref "IC4") (pin "15") (pinfunction "D4_15") (pintype "input"))
      (node (ref "JP3") (pin "24") (pinfunction "24_24") (pintype "passive"))
    )
    (net (code "92") (name "/IO_INPUT2_1") (class "Default")
      (node (ref "IC16") (pin "15") (pinfunction "D4_15") (pintype "input"))
      (node (ref "JP3") (pin "26") (pinfunction "26_26") (pintype "passive"))
    )
    (net (code "93") (name "/IO_INPUT2_2") (class "Default")
      (node (ref "IC23") (pin "15") (pinfunction "D4_15") (pintype "input"))
      (node (ref "JP3") (pin "28") (pinfunction "28_28") (pintype "passive"))
    )
    (net (code "94") (name "/IO_INPUT2_3") (class "Default")
      (node (ref "IC32") (pin "15") (pinfunction "D4_15") (pintype "input"))
      (node (ref "JP3") (pin "30") (pinfunction "30_30") (pintype "passive"))
    )
    (net (code "95") (name "/IO_INPUT2_4") (class "Default")
      (node (ref "IC38") (pin "15") (pinfunction "D4_15") (pintype "input"))
      (node (ref "JP3") (pin "32") (pinfunction "32_32") (pintype "passive"))
    )
    (net (code "96") (name "/IO_INPUT2_5") (class "Default")
      (node (ref "IC43") (pin "15") (pinfunction "D4_15") (pintype "input"))
      (node (ref "JP3") (pin "34") (pinfunction "34_34") (pintype "passive"))
    )
    (net (code "97") (name "/IO_INPUT2_6") (class "Default")
      (node (ref "IC47") (pin "15") (pinfunction "D4_15") (pintype "input"))
      (node (ref "JP3") (pin "36") (pinfunction "36_36") (pintype "passive"))
    )
    (net (code "98") (name "/IO_INPUT2_7") (class "Default")
      (node (ref "IC51") (pin "15") (pinfunction "D4_15") (pintype "input"))
      (node (ref "JP3") (pin "38") (pinfunction "38_38") (pintype "passive"))
    )
    (net (code "99") (name "/IO_OUTPUT1_0") (class "Default")
      (node (ref "IC4") (pin "14") (pinfunction "D5_14") (pintype "input"))
      (node (ref "IC73") (pin "2") (pinfunction "1Q_2") (pintype "tri_state"))
      (node (ref "JP3") (pin "1") (pinfunction "1_1") (pintype "passive"))
    )
    (net (code "100") (name "/IO_OUTPUT1_1") (class "Default")
      (node (ref "IC16") (pin "14") (pinfunction "D5_14") (pintype "input"))
      (node (ref "IC73") (pin "5") (pinfunction "2Q_5") (pintype "tri_state"))
      (node (ref "JP3") (pin "3") (pinfunction "3_3") (pintype "passive"))
    )
    (net (code "101") (name "/IO_OUTPUT1_2") (class "Default")
      (node (ref "IC23") (pin "14") (pinfunction "D5_14") (pintype "input"))
      (node (ref "IC73") (pin "6") (pinfunction "3Q_6") (pintype "tri_state"))
      (node (ref "JP3") (pin "5") (pinfunction "5_5") (pintype "passive"))
    )
    (net (code "102") (name "/IO_OUTPUT1_3") (class "Default")
      (node (ref "IC32") (pin "14") (pinfunction "D5_14") (pintype "input"))
      (node (ref "IC73") (pin "9") (pinfunction "4Q_9") (pintype "tri_state"))
      (node (ref "JP3") (pin "7") (pinfunction "7_7") (pintype "passive"))
    )
    (net (code "103") (name "/IO_OUTPUT1_4") (class "Default")
      (node (ref "IC38") (pin "14") (pinfunction "D5_14") (pintype "input"))
      (node (ref "IC73") (pin "12") (pinfunction "5Q_12") (pintype "tri_state"))
      (node (ref "JP3") (pin "9") (pinfunction "9_9") (pintype "passive"))
    )
    (net (code "104") (name "/IO_OUTPUT1_5") (class "Default")
      (node (ref "IC43") (pin "14") (pinfunction "D5_14") (pintype "input"))
      (node (ref "IC73") (pin "15") (pinfunction "6Q_15") (pintype "tri_state"))
      (node (ref "JP3") (pin "11") (pinfunction "11_11") (pintype "passive"))
    )
    (net (code "105") (name "/IO_OUTPUT1_6") (class "Default")
      (node (ref "IC47") (pin "14") (pinfunction "D5_14") (pintype "input"))
      (node (ref "IC73") (pin "16") (pinfunction "7Q_16") (pintype "tri_state"))
      (node (ref "JP3") (pin "13") (pinfunction "13_13") (pintype "passive"))
    )
    (net (code "106") (name "/IO_OUTPUT1_7") (class "Default")
      (node (ref "IC51") (pin "14") (pinfunction "D5_14") (pintype "input"))
      (node (ref "IC73") (pin "19") (pinfunction "8Q_19") (pintype "tri_state"))
      (node (ref "JP3") (pin "15") (pinfunction "15_15") (pintype "passive"))
    )
    (net (code "107") (name "/IO_OUTPUT2_0") (class "Default")
      (node (ref "IC4") (pin "13") (pinfunction "D6_13") (pintype "input"))
      (node (ref "IC79") (pin "2") (pinfunction "1Q_2") (pintype "tri_state"))
      (node (ref "JP3") (pin "23") (pinfunction "23_23") (pintype "passive"))
    )
    (net (code "108") (name "/IO_OUTPUT2_1") (class "Default")
      (node (ref "IC16") (pin "13") (pinfunction "D6_13") (pintype "input"))
      (node (ref "IC79") (pin "5") (pinfunction "2Q_5") (pintype "tri_state"))
      (node (ref "JP3") (pin "25") (pinfunction "25_25") (pintype "passive"))
    )
    (net (code "109") (name "/IO_OUTPUT2_2") (class "Default")
      (node (ref "IC23") (pin "13") (pinfunction "D6_13") (pintype "input"))
      (node (ref "IC79") (pin "6") (pinfunction "3Q_6") (pintype "tri_state"))
      (node (ref "JP3") (pin "27") (pinfunction "27_27") (pintype "passive"))
    )
    (net (code "110") (name "/IO_OUTPUT2_3") (class "Default")
      (node (ref "IC32") (pin "13") (pinfunction "D6_13") (pintype "input"))
      (node (ref "IC79") (pin "9") (pinfunction "4Q_9") (pintype "tri_state"))
      (node (ref "JP3") (pin "29") (pinfunction "29_29") (pintype "passive"))
    )
    (net (code "111") (name "/IO_OUTPUT2_4") (class "Default")
      (node (ref "IC38") (pin "13") (pinfunction "D6_13") (pintype "input"))
      (node (ref "IC79") (pin "12") (pinfunction "5Q_12") (pintype "tri_state"))
      (node (ref "JP3") (pin "31") (pinfunction "31_31") (pintype "passive"))
    )
    (net (code "112") (name "/IO_OUTPUT2_5") (class "Default")
      (node (ref "IC43") (pin "13") (pinfunction "D6_13") (pintype "input"))
      (node (ref "IC79") (pin "15") (pinfunction "6Q_15") (pintype "tri_state"))
      (node (ref "JP3") (pin "33") (pinfunction "33_33") (pintype "passive"))
    )
    (net (code "113") (name "/IO_OUTPUT2_6") (class "Default")
      (node (ref "IC47") (pin "13") (pinfunction "D6_13") (pintype "input"))
      (node (ref "IC79") (pin "16") (pinfunction "7Q_16") (pintype "tri_state"))
      (node (ref "JP3") (pin "35") (pinfunction "35_35") (pintype "passive"))
    )
    (net (code "114") (name "/IO_OUTPUT2_7") (class "Default")
      (node (ref "IC51") (pin "13") (pinfunction "D6_13") (pintype "input"))
      (node (ref "IC79") (pin "19") (pinfunction "8Q_19") (pintype "tri_state"))
      (node (ref "JP3") (pin "37") (pinfunction "37_37") (pintype "passive"))
    )
    (net (code "115") (name "/IO_OUTPUT_REG_1_LOAD_INPUT") (class "Default")
      (node (ref "IC10") (pin "8") (pinfunction "O_8") (pintype "output"))
      (node (ref "IC73") (pin "11") (pinfunction "CLK_11") (pintype "input"))
    )
    (net (code "116") (name "/IO_OUTPUT_REG_2_LOAD_INPUT") (class "Default")
      (node (ref "IC10") (pin "11") (pinfunction "O_11") (pintype "output"))
      (node (ref "IC79") (pin "11") (pinfunction "CLK_11") (pintype "input"))
    )
    (net (code "117") (name "/IR_DATA_OUT_0") (class "Default")
      (node (ref "IC3") (pin "4") (pinfunction "D0_4") (pintype "input"))
      (node (ref "IC41") (pin "2") (pinfunction "1Q_2") (pintype "tri_state"))
    )
    (net (code "118") (name "/IR_DATA_OUT_1") (class "Default")
      (node (ref "IC15") (pin "4") (pinfunction "D0_4") (pintype "input"))
      (node (ref "IC41") (pin "5") (pinfunction "2Q_5") (pintype "tri_state"))
    )
    (net (code "119") (name "/IR_DATA_OUT_2") (class "Default")
      (node (ref "IC22") (pin "4") (pinfunction "D0_4") (pintype "input"))
      (node (ref "IC41") (pin "6") (pinfunction "3Q_6") (pintype "tri_state"))
    )
    (net (code "120") (name "/IR_DATA_OUT_3") (class "Default")
      (node (ref "IC31") (pin "4") (pinfunction "D0_4") (pintype "input"))
      (node (ref "IC41") (pin "9") (pinfunction "4Q_9") (pintype "tri_state"))
    )
    (net (code "121") (name "/IR_DATA_OUT_4") (class "Default")
      (node (ref "IC37") (pin "4") (pinfunction "D0_4") (pintype "input"))
      (node (ref "IC41") (pin "12") (pinfunction "5Q_12") (pintype "tri_state"))
    )
    (net (code "122") (name "/IR_DATA_OUT_5") (class "Default")
      (node (ref "IC41") (pin "15") (pinfunction "6Q_15") (pintype "tri_state"))
      (node (ref "IC42") (pin "4") (pinfunction "D0_4") (pintype "input"))
    )
    (net (code "123") (name "/IR_DATA_OUT_6") (class "Default")
      (node (ref "IC41") (pin "16") (pinfunction "7Q_16") (pintype "tri_state"))
      (node (ref "IC46") (pin "4") (pinfunction "D0_4") (pintype "input"))
    )
    (net (code "124") (name "/IR_DATA_OUT_7") (class "Default")
      (node (ref "IC108") (pin "10") (pinfunction "I1_10") (pintype "input"))
      (node (ref "IC41") (pin "19") (pinfunction "8Q_19") (pintype "tri_state"))
      (node (ref "IC50") (pin "4") (pinfunction "D0_4") (pintype "input"))
      (node (ref "IC72") (pin "4") (pinfunction "I0_4") (pintype "input"))
      (node (ref "IC86") (pin "11") (pinfunction "I_11") (pintype "input"))
    )
    (net (code "125") (name "/IR_LOAD_INPUT{slash}~{CYCL_2}") (class "Default")
      (node (ref "IC41") (pin "11") (pinfunction "CLK_11") (pintype "input"))
      (node (ref "IC53") (pin "8") (pinfunction "~{Q}_8") (pintype "output"))
    )
    (net (code "126") (name "/LATCH_ALU_INPUT_ALU_JMP_O") (class "Default")
      (node (ref "IC1") (pin "3") (pinfunction "O_3") (pintype "output"))
      (node (ref "IC1") (pin "4") (pinfunction "I0_4") (pintype "input"))
      (node (ref "IC103") (pin "11") (pinfunction "ENC_11") (pintype "input"))
    )
    (net (code "127") (name "/LATCH_ALU_INPUT_B{slash}WRITE_REGB_TO_DBUS_ALU") (class "Default")
      (node (ref "IC1") (pin "1") (pinfunction "I0_1") (pintype "input"))
      (node (ref "IC72") (pin "3") (pinfunction "O_3") (pintype "output"))
    )
    (net (code "128") (name "/LATCH_ALU_INPUT_B{slash}WRITE_REGB_TO_DBUS_JMP_O") (class "Default")
      (node (ref "IC1") (pin "2") (pinfunction "I1_2") (pintype "input"))
      (node (ref "IC40") (pin "6") (pinfunction "O_6") (pintype "output"))
    )
    (net (code "129") (name "/LDR") (class "Default")
      (node (ref "IC1") (pin "10") (pinfunction "I1_10") (pintype "input"))
      (node (ref "IC91") (pin "11") (pinfunction "O_11") (pintype "output"))
    )
    (net (code "130") (name "/LDR_I") (class "Default")
      (node (ref "IC1") (pin "9") (pinfunction "I0_9") (pintype "input"))
      (node (ref "IC89") (pin "2") (pinfunction "I1_2") (pintype "input"))
      (node (ref "IC91") (pin "8") (pinfunction "O_8") (pintype "output"))
    )
    (net (code "131") (name "/LDR{slash}LDR_I") (class "Default")
      (node (ref "IC1") (pin "8") (pinfunction "O_8") (pintype "output"))
      (node (ref "IC100") (pin "10") (pinfunction "I1_10") (pintype "input"))
      (node (ref "IC48") (pin "1") (pinfunction "I0_1") (pintype "input"))
    )
    (net (code "132") (name "/LR_DATA_OUT_0") (class "Default")
      (node (ref "IC4") (pin "4") (pinfunction "D0_4") (pintype "input"))
      (node (ref "IC81") (pin "2") (pinfunction "1Q_2") (pintype "tri_state"))
    )
    (net (code "133") (name "/LR_DATA_OUT_1") (class "Default")
      (node (ref "IC16") (pin "4") (pinfunction "D0_4") (pintype "input"))
      (node (ref "IC81") (pin "5") (pinfunction "2Q_5") (pintype "tri_state"))
    )
    (net (code "134") (name "/LR_DATA_OUT_2") (class "Default")
      (node (ref "IC23") (pin "4") (pinfunction "D0_4") (pintype "input"))
      (node (ref "IC81") (pin "6") (pinfunction "3Q_6") (pintype "tri_state"))
    )
    (net (code "135") (name "/LR_DATA_OUT_3") (class "Default")
      (node (ref "IC32") (pin "4") (pinfunction "D0_4") (pintype "input"))
      (node (ref "IC81") (pin "9") (pinfunction "4Q_9") (pintype "tri_state"))
    )
    (net (code "136") (name "/LR_DATA_OUT_4") (class "Default")
      (node (ref "IC38") (pin "4") (pinfunction "D0_4") (pintype "input"))
      (node (ref "IC81") (pin "12") (pinfunction "5Q_12") (pintype "tri_state"))
    )
    (net (code "137") (name "/LR_DATA_OUT_5") (class "Default")
      (node (ref "IC43") (pin "4") (pinfunction "D0_4") (pintype "input"))
      (node (ref "IC81") (pin "15") (pinfunction "6Q_15") (pintype "tri_state"))
    )
    (net (code "138") (name "/LR_DATA_OUT_6") (class "Default")
      (node (ref "IC47") (pin "4") (pinfunction "D0_4") (pintype "input"))
      (node (ref "IC81") (pin "16") (pinfunction "7Q_16") (pintype "tri_state"))
    )
    (net (code "139") (name "/LR_DATA_OUT_7") (class "Default")
      (node (ref "IC51") (pin "4") (pinfunction "D0_4") (pintype "input"))
      (node (ref "IC81") (pin "19") (pinfunction "8Q_19") (pintype "tri_state"))
    )
    (net (code "140") (name "/LR_DATA_OUT_8") (class "Default")
      (node (ref "IC4") (pin "3") (pinfunction "D1_3") (pintype "input"))
      (node (ref "IC85") (pin "2") (pinfunction "1Q_2") (pintype "tri_state"))
    )
    (net (code "141") (name "/LR_DATA_OUT_9") (class "Default")
      (node (ref "IC16") (pin "3") (pinfunction "D1_3") (pintype "input"))
      (node (ref "IC85") (pin "5") (pinfunction "2Q_5") (pintype "tri_state"))
    )
    (net (code "142") (name "/LR_DATA_OUT_10") (class "Default")
      (node (ref "IC23") (pin "3") (pinfunction "D1_3") (pintype "input"))
      (node (ref "IC85") (pin "6") (pinfunction "3Q_6") (pintype "tri_state"))
    )
    (net (code "143") (name "/LR_DATA_OUT_11") (class "Default")
      (node (ref "IC32") (pin "3") (pinfunction "D1_3") (pintype "input"))
      (node (ref "IC85") (pin "9") (pinfunction "4Q_9") (pintype "tri_state"))
    )
    (net (code "144") (name "/LR_DATA_OUT_12") (class "Default")
      (node (ref "IC38") (pin "3") (pinfunction "D1_3") (pintype "input"))
      (node (ref "IC85") (pin "12") (pinfunction "5Q_12") (pintype "tri_state"))
    )
    (net (code "145") (name "/LR_DATA_OUT_13") (class "Default")
      (node (ref "IC43") (pin "3") (pinfunction "D1_3") (pintype "input"))
      (node (ref "IC85") (pin "15") (pinfunction "6Q_15") (pintype "tri_state"))
    )
    (net (code "146") (name "/LR_DATA_OUT_14") (class "Default")
      (node (ref "IC47") (pin "3") (pinfunction "D1_3") (pintype "input"))
      (node (ref "IC85") (pin "16") (pinfunction "7Q_16") (pintype "tri_state"))
    )
    (net (code "147") (name "/LR_DATA_OUT_15") (class "Default")
      (node (ref "IC51") (pin "3") (pinfunction "D1_3") (pintype "input"))
      (node (ref "IC85") (pin "19") (pinfunction "8Q_19") (pintype "tri_state"))
    )
    (net (code "148") (name "/LR_H_LOAD_INPUT_NOT") (class "Default")
      (node (ref "IC44") (pin "13") (pinfunction "O_13") (pintype "output"))
      (node (ref "IC85") (pin "11") (pinfunction "CLK_11") (pintype "input"))
    )
    (net (code "149") (name "/LR_H_LOAD_INPUT_TABLE_1") (class "Default")
      (node (ref "IC24") (pin "6") (pinfunction "O_6") (pintype "output"))
      (node (ref "IC44") (pin "12") (pinfunction "I1_12") (pintype "input"))
    )
    (net (code "150") (name "/LR_L_LOAD_INPUT_NOT") (class "Default")
      (node (ref "IC44") (pin "10") (pinfunction "O_10") (pintype "output"))
      (node (ref "IC81") (pin "11") (pinfunction "CLK_11") (pintype "input"))
    )
    (net (code "151") (name "/LR_L_LOAD_INPUT_TABLE_1") (class "Default")
      (node (ref "IC24") (pin "3") (pinfunction "O_3") (pintype "output"))
      (node (ref "IC44") (pin "9") (pinfunction "I1_9") (pintype "input"))
    )
    (net (code "152") (name "/MEM_NOT_OE") (class "Default")
      (node (ref "IC67") (pin "12") (pinfunction "O_12") (pintype "output"))
      (node (ref "JP1") (pin "20") (pinfunction "20_20") (pintype "passive"))
      (node (ref "JP2") (pin "20") (pinfunction "20_20") (pintype "passive"))
    )
    (net (code "153") (name "/MEM_NOT_WE") (class "Default")
      (node (ref "IC67") (pin "4") (pinfunction "O_4") (pintype "output"))
      (node (ref "JP1") (pin "24") (pinfunction "24_24") (pintype "passive"))
      (node (ref "JP2") (pin "24") (pinfunction "24_24") (pintype "passive"))
    )
    (net (code "154") (name "/MEM_OE") (class "Default")
      (node (ref "IC112") (pin "12") (pinfunction "I0_12") (pintype "input"))
      (node (ref "IC67") (pin "13") (pinfunction "I_13") (pintype "input"))
      (node (ref "IC68") (pin "6") (pinfunction "O_6") (pintype "output"))
    )
    (net (code "155") (name "/OPC==E") (class "Default")
      (node (ref "IC19") (pin "12") (pinfunction "I1_12") (pintype "input"))
      (node (ref "IC63") (pin "11") (pinfunction "O_11") (pintype "output"))
      (node (ref "IC92") (pin "10") (pinfunction "I1_10") (pintype "input"))
    )
    (net (code "156") (name "/OPC==F") (class "Default")
      (node (ref "IC19") (pin "11") (pinfunction "I0_11") (pintype "input"))
      (node (ref "IC59") (pin "4") (pinfunction "I0_4") (pintype "input"))
      (node (ref "IC63") (pin "6") (pinfunction "O_6") (pintype "output"))
    )
    (net (code "157") (name "/OPCODE_0") (class "Default")
      (node (ref "IC45") (pin "2") (pinfunction "1Q_2") (pintype "tri_state"))
      (node (ref "IC86") (pin "1") (pinfunction "I_1") (pintype "input"))
      (node (ref "IC87") (pin "4") (pinfunction "I0_4") (pintype "input"))
      (node (ref "IC87") (pin "9") (pinfunction "I0_9") (pintype "input"))
    )
    (net (code "158") (name "/OPCODE_1") (class "Default")
      (node (ref "IC45") (pin "5") (pinfunction "2Q_5") (pintype "tri_state"))
      (node (ref "IC86") (pin "3") (pinfunction "I_3") (pintype "input"))
      (node (ref "IC87") (pin "10") (pinfunction "I1_10") (pintype "input"))
      (node (ref "IC87") (pin "13") (pinfunction "I1_13") (pintype "input"))
    )
    (net (code "159") (name "/OPCODE_2") (class "Default")
      (node (ref "IC45") (pin "6") (pinfunction "3Q_6") (pintype "tri_state"))
      (node (ref "IC82") (pin "13") (pinfunction "I1_13") (pintype "input"))
      (node (ref "IC82") (pin "5") (pinfunction "I1_5") (pintype "input"))
      (node (ref "IC86") (pin "5") (pinfunction "I_5") (pintype "input"))
      (node (ref "IC90") (pin "13") (pinfunction "I1_13") (pintype "input"))
      (node (ref "IC90") (pin "5") (pinfunction "I1_5") (pintype "input"))
    )
    (net (code "160") (name "/OPCODE_3") (class "Default")
      (node (ref "IC45") (pin "9") (pinfunction "4Q_9") (pintype "tri_state"))
      (node (ref "IC77") (pin "10") (pinfunction "I1_10") (pintype "input"))
      (node (ref "IC77") (pin "2") (pinfunction "I1_2") (pintype "input"))
      (node (ref "IC83") (pin "10") (pinfunction "I1_10") (pintype "input"))
      (node (ref "IC83") (pin "2") (pinfunction "I1_2") (pintype "input"))
      (node (ref "IC86") (pin "9") (pinfunction "I_9") (pintype "input"))
      (node (ref "IC91") (pin "10") (pinfunction "I1_10") (pintype "input"))
      (node (ref "IC91") (pin "2") (pinfunction "I1_2") (pintype "input"))
      (node (ref "IC95") (pin "10") (pinfunction "I1_10") (pintype "input"))
      (node (ref "IC95") (pin "2") (pinfunction "I1_2") (pintype "input"))
    )
    (net (code "161") (name "/OPCODE_4") (class "Default")
      (node (ref "IC11") (pin "3") (pinfunction "1B_3") (pintype "input"))
      (node (ref "IC14") (pin "3") (pinfunction "I_3") (pintype "input"))
      (node (ref "IC25") (pin "4") (pinfunction "I0_4") (pintype "input"))
      (node (ref "IC28") (pin "4") (pinfunction "I0_4") (pintype "input"))
      (node (ref "IC28") (pin "9") (pinfunction "I0_9") (pintype "input"))
      (node (ref "IC45") (pin "12") (pinfunction "5Q_12") (pintype "tri_state"))
    )
    (net (code "162") (name "/OPCODE_5") (class "Default")
      (node (ref "IC11") (pin "6") (pinfunction "2B_6") (pintype "input"))
      (node (ref "IC14") (pin "5") (pinfunction "I_5") (pintype "input"))
      (node (ref "IC25") (pin "1") (pinfunction "I0_1") (pintype "input"))
      (node (ref "IC28") (pin "10") (pinfunction "I1_10") (pintype "input"))
      (node (ref "IC28") (pin "13") (pinfunction "I1_13") (pintype "input"))
      (node (ref "IC45") (pin "15") (pinfunction "6Q_15") (pintype "tri_state"))
    )
    (net (code "163") (name "/OPCODE_6") (class "Default")
      (node (ref "IC11") (pin "10") (pinfunction "3B_10") (pintype "input"))
      (node (ref "IC14") (pin "13") (pinfunction "I_13") (pintype "input"))
      (node (ref "IC25") (pin "5") (pinfunction "I1_5") (pintype "input"))
      (node (ref "IC45") (pin "16") (pinfunction "7Q_16") (pintype "tri_state"))
      (node (ref "IC7") (pin "4") (pinfunction "I0_4") (pintype "input"))
      (node (ref "IC7") (pin "9") (pinfunction "I0_9") (pintype "input"))
    )
    (net (code "164") (name "/OPCODE_7") (class "Default")
      (node (ref "IC11") (pin "13") (pinfunction "4B_13") (pintype "input"))
      (node (ref "IC14") (pin "1") (pinfunction "I_1") (pintype "input"))
      (node (ref "IC25") (pin "2") (pinfunction "I1_2") (pintype "input"))
      (node (ref "IC45") (pin "19") (pinfunction "8Q_19") (pintype "tri_state"))
      (node (ref "IC7") (pin "10") (pinfunction "I1_10") (pintype "input"))
      (node (ref "IC7") (pin "13") (pinfunction "I1_13") (pintype "input"))
    )
    (net (code "165") (name "/OPCODE_LOAD_INPUT{slash}~{CYCL_1}") (class "Default")
      (node (ref "IC45") (pin "11") (pinfunction "CLK_11") (pintype "input"))
      (node (ref "IC53") (pin "6") (pinfunction "~{Q}_6") (pintype "output"))
    )
    (net (code "166") (name "/OPC_67_OUPUT0{slash}REG0_JMP") (class "Default")
      (node (ref "IC20") (pin "1") (pinfunction "I0_1") (pintype "input"))
      (node (ref "IC6") (pin "2") (pinfunction "I1_2") (pintype "input"))
      (node (ref "IC7") (pin "3") (pinfunction "O_3") (pintype "output"))
      (node (ref "IC88") (pin "2") (pinfunction "I1_2") (pintype "input"))
    )
    (net (code "167") (name "/OPC_67_OUPUT1") (class "Default")
      (node (ref "IC20") (pin "4") (pinfunction "I0_4") (pintype "input"))
      (node (ref "IC6") (pin "5") (pinfunction "I1_5") (pintype "input"))
      (node (ref "IC7") (pin "6") (pinfunction "O_6") (pintype "output"))
    )
    (net (code "168") (name "/OPC_67_OUPUT2==11") (class "Default")
      (node (ref "IC20") (pin "9") (pinfunction "I0_9") (pintype "input"))
      (node (ref "IC6") (pin "10") (pinfunction "I1_10") (pintype "input"))
      (node (ref "IC63") (pin "5") (pinfunction "I1_5") (pintype "input"))
      (node (ref "IC7") (pin "8") (pinfunction "O_8") (pintype "output"))
    )
    (net (code "169") (name "/OPC_67_OUPUT3==10") (class "Default")
      (node (ref "IC20") (pin "12") (pinfunction "I0_12") (pintype "input"))
      (node (ref "IC6") (pin "13") (pinfunction "I1_13") (pintype "input"))
      (node (ref "IC63") (pin "13") (pinfunction "I1_13") (pintype "input"))
      (node (ref "IC7") (pin "11") (pinfunction "O_11") (pintype "output"))
    )
    (net (code "170") (name "/OPERAND_REGB_OUTPUT") (class "Default")
      (node (ref "IC1") (pin "6") (pinfunction "O_6") (pintype "output"))
      (node (ref "IC19") (pin "2") (pinfunction "I0_2") (pintype "input"))
      (node (ref "IC9") (pin "1") (pinfunction "~{A}/B_1") (pintype "input"))
    )
    (net (code "171") (name "/PC_COUNT_UP_RET") (class "Default")
      (node (ref "IC126") (pin "8") (pinfunction "O_8") (pintype "output"))
      (node (ref "IC48") (pin "4") (pinfunction "I0_4") (pintype "input"))
    )
    (net (code "172") (name "/PC_COUNT_UP_SAVE_LR") (class "Default")
      (node (ref "IC48") (pin "5") (pinfunction "I1_5") (pintype "input"))
      (node (ref "IC52") (pin "3") (pinfunction "O_3") (pintype "output"))
    )
    (net (code "173") (name "/PC_DATA_OUT_0") (class "Default")
      (node (ref "IC13") (pin "3") (pinfunction "1B_3") (pintype "input"))
      (node (ref "IC4") (pin "2") (pinfunction "D2_2") (pintype "input"))
      (node (ref "IC57") (pin "3") (pinfunction "QA_3") (pintype "output"))
    )
    (net (code "174") (name "/PC_DATA_OUT_1") (class "Default")
      (node (ref "IC13") (pin "6") (pinfunction "2B_6") (pintype "input"))
      (node (ref "IC16") (pin "2") (pinfunction "D2_2") (pintype "input"))
      (node (ref "IC57") (pin "2") (pinfunction "QB_2") (pintype "output"))
    )
    (net (code "175") (name "/PC_DATA_OUT_2") (class "Default")
      (node (ref "IC13") (pin "10") (pinfunction "3B_10") (pintype "input"))
      (node (ref "IC23") (pin "2") (pinfunction "D2_2") (pintype "input"))
      (node (ref "IC57") (pin "6") (pinfunction "QC_6") (pintype "output"))
    )
    (net (code "176") (name "/PC_DATA_OUT_3") (class "Default")
      (node (ref "IC13") (pin "13") (pinfunction "4B_13") (pintype "input"))
      (node (ref "IC32") (pin "2") (pinfunction "D2_2") (pintype "input"))
      (node (ref "IC57") (pin "7") (pinfunction "QD_7") (pintype "output"))
    )
    (net (code "177") (name "/PC_DATA_OUT_4") (class "Default")
      (node (ref "IC21") (pin "3") (pinfunction "1B_3") (pintype "input"))
      (node (ref "IC38") (pin "2") (pinfunction "D2_2") (pintype "input"))
      (node (ref "IC58") (pin "3") (pinfunction "QA_3") (pintype "output"))
    )
    (net (code "178") (name "/PC_DATA_OUT_5") (class "Default")
      (node (ref "IC21") (pin "6") (pinfunction "2B_6") (pintype "input"))
      (node (ref "IC43") (pin "2") (pinfunction "D2_2") (pintype "input"))
      (node (ref "IC58") (pin "2") (pinfunction "QB_2") (pintype "output"))
    )
    (net (code "179") (name "/PC_DATA_OUT_6") (class "Default")
      (node (ref "IC21") (pin "10") (pinfunction "3B_10") (pintype "input"))
      (node (ref "IC47") (pin "2") (pinfunction "D2_2") (pintype "input"))
      (node (ref "IC58") (pin "6") (pinfunction "QC_6") (pintype "output"))
    )
    (net (code "180") (name "/PC_DATA_OUT_7") (class "Default")
      (node (ref "IC21") (pin "13") (pinfunction "4B_13") (pintype "input"))
      (node (ref "IC51") (pin "2") (pinfunction "D2_2") (pintype "input"))
      (node (ref "IC58") (pin "7") (pinfunction "QD_7") (pintype "output"))
    )
    (net (code "181") (name "/PC_DATA_OUT_8") (class "Default")
      (node (ref "IC27") (pin "3") (pinfunction "1B_3") (pintype "input"))
      (node (ref "IC4") (pin "1") (pinfunction "D3_1") (pintype "input"))
      (node (ref "IC60") (pin "3") (pinfunction "QA_3") (pintype "output"))
    )
    (net (code "182") (name "/PC_DATA_OUT_9") (class "Default")
      (node (ref "IC16") (pin "1") (pinfunction "D3_1") (pintype "input"))
      (node (ref "IC27") (pin "6") (pinfunction "2B_6") (pintype "input"))
      (node (ref "IC60") (pin "2") (pinfunction "QB_2") (pintype "output"))
    )
    (net (code "183") (name "/PC_DATA_OUT_10") (class "Default")
      (node (ref "IC23") (pin "1") (pinfunction "D3_1") (pintype "input"))
      (node (ref "IC27") (pin "10") (pinfunction "3B_10") (pintype "input"))
      (node (ref "IC60") (pin "6") (pinfunction "QC_6") (pintype "output"))
    )
    (net (code "184") (name "/PC_DATA_OUT_11") (class "Default")
      (node (ref "IC27") (pin "13") (pinfunction "4B_13") (pintype "input"))
      (node (ref "IC32") (pin "1") (pinfunction "D3_1") (pintype "input"))
      (node (ref "IC60") (pin "7") (pinfunction "QD_7") (pintype "output"))
    )
    (net (code "185") (name "/PC_DATA_OUT_12") (class "Default")
      (node (ref "IC34") (pin "3") (pinfunction "1B_3") (pintype "input"))
      (node (ref "IC38") (pin "1") (pinfunction "D3_1") (pintype "input"))
      (node (ref "IC64") (pin "3") (pinfunction "QA_3") (pintype "output"))
    )
    (net (code "186") (name "/PC_DATA_OUT_13") (class "Default")
      (node (ref "IC34") (pin "6") (pinfunction "2B_6") (pintype "input"))
      (node (ref "IC43") (pin "1") (pinfunction "D3_1") (pintype "input"))
      (node (ref "IC64") (pin "2") (pinfunction "QB_2") (pintype "output"))
    )
    (net (code "187") (name "/PC_DATA_OUT_14") (class "Default")
      (node (ref "IC34") (pin "10") (pinfunction "3B_10") (pintype "input"))
      (node (ref "IC47") (pin "1") (pinfunction "D3_1") (pintype "input"))
      (node (ref "IC64") (pin "6") (pinfunction "QC_6") (pintype "output"))
    )
    (net (code "188") (name "/PC_DATA_OUT_15") (class "Default")
      (node (ref "IC34") (pin "13") (pinfunction "4B_13") (pintype "input"))
      (node (ref "IC51") (pin "1") (pinfunction "D3_1") (pintype "input"))
      (node (ref "IC64") (pin "7") (pinfunction "QD_7") (pintype "output"))
    )
    (net (code "189") (name "/PC_HIGH_LOAD_INPUT_JMP") (class "Default")
      (node (ref "IC52") (pin "8") (pinfunction "O_8") (pintype "output"))
      (node (ref "IC56") (pin "5") (pinfunction "I1_5") (pintype "input"))
    )
    (net (code "190") (name "/PC_HIGH_LOAD_INPUT_NOT") (class "Default")
      (node (ref "IC44") (pin "4") (pinfunction "O_4") (pintype "output"))
      (node (ref "IC60") (pin "11") (pinfunction "LD_11") (pintype "input"))
      (node (ref "IC64") (pin "11") (pinfunction "LD_11") (pintype "input"))
    )
    (net (code "191") (name "/PC_H_COUNT_DOWN_JMP_O") (class "Default")
      (node (ref "IC60") (pin "4") (pinfunction "DN_4") (pintype "input"))
      (node (ref "IC88") (pin "6") (pinfunction "O_6") (pintype "output"))
    )
    (net (code "192") (name "/PC_H_COUNT_UP_JMP_O") (class "Default")
      (node (ref "IC25") (pin "10") (pinfunction "I1_10") (pintype "input"))
      (node (ref "IC88") (pin "11") (pinfunction "O_11") (pintype "output"))
    )
    (net (code "193") (name "/PC_H_LOAD_INPUT_TABLE_1") (class "Default")
      (node (ref "IC24") (pin "11") (pinfunction "O_11") (pintype "output"))
      (node (ref "IC44") (pin "5") (pinfunction "I0_5") (pintype "input"))
    )
    (net (code "194") (name "/PC_LOW_LOAD_INPUT_JMP") (class "Default")
      (node (ref "IC52") (pin "6") (pinfunction "O_6") (pintype "output"))
      (node (ref "IC56") (pin "9") (pinfunction "I0_9") (pintype "input"))
    )
    (net (code "195") (name "/PC_LOW_LOAD_INPUT_NOT") (class "Default")
      (node (ref "IC44") (pin "1") (pinfunction "O_1") (pintype "output"))
      (node (ref "IC57") (pin "11") (pinfunction "LD_11") (pintype "input"))
      (node (ref "IC58") (pin "11") (pinfunction "LD_11") (pintype "input"))
    )
    (net (code "196") (name "/PC_L_LOAD_INPUT_TABLE_1") (class "Default")
      (node (ref "IC24") (pin "8") (pinfunction "O_8") (pintype "output"))
      (node (ref "IC56") (pin "13") (pinfunction "I1_13") (pintype "input"))
    )
    (net (code "197") (name "/PC_L_TO_DBUS") (class "Default")
      (node (ref "IC56") (pin "3") (pinfunction "O_3") (pintype "output"))
      (node (ref "IC65") (pin "12") (pinfunction "I0_12") (pintype "input"))
      (node (ref "IC65") (pin "5") (pinfunction "I1_5") (pintype "input"))
    )
    (net (code "198") (name "/POP{slash}SAVE_LR{slash}RET") (class "Default")
      (node (ref "IC48") (pin "2") (pinfunction "I1_2") (pintype "input"))
      (node (ref "IC59") (pin "5") (pinfunction "I1_5") (pintype "input"))
      (node (ref "IC63") (pin "1") (pinfunction "I0_1") (pintype "input"))
      (node (ref "IC92") (pin "9") (pinfunction "I0_9") (pintype "input"))
      (node (ref "IC95") (pin "11") (pinfunction "O_11") (pintype "output"))
    )
    (net (code "199") (name "/PTR_COUNT_UP") (class "Default")
      (node (ref "IC129") (pin "12") (pinfunction "O_12") (pintype "output"))
      (node (ref "IC17") (pin "5") (pinfunction "UP_5") (pintype "input"))
    )
    (net (code "200") (name "/PTR_COUNT_UP_LDR_I") (class "Default")
      (node (ref "IC55") (pin "1") (pinfunction "I0_1") (pintype "input"))
      (node (ref "IC89") (pin "3") (pinfunction "O_3") (pintype "output"))
    )
    (net (code "201") (name "/PTR_COUNT_UP_STR_I") (class "Default")
      (node (ref "IC55") (pin "2") (pinfunction "I1_2") (pintype "input"))
      (node (ref "IC99") (pin "6") (pinfunction "O_6") (pintype "output"))
    )
    (net (code "202") (name "/PTR_DATA_OUT_0") (class "Default")
      (node (ref "IC13") (pin "2") (pinfunction "1A_2") (pintype "input"))
      (node (ref "IC17") (pin "3") (pinfunction "QA_3") (pintype "output"))
      (node (ref "IC3") (pin "14") (pinfunction "D5_14") (pintype "input"))
    )
    (net (code "203") (name "/PTR_DATA_OUT_1") (class "Default")
      (node (ref "IC13") (pin "5") (pinfunction "2A_5") (pintype "input"))
      (node (ref "IC15") (pin "14") (pinfunction "D5_14") (pintype "input"))
      (node (ref "IC17") (pin "2") (pinfunction "QB_2") (pintype "output"))
    )
    (net (code "204") (name "/PTR_DATA_OUT_2") (class "Default")
      (node (ref "IC13") (pin "11") (pinfunction "3A_11") (pintype "input"))
      (node (ref "IC17") (pin "6") (pinfunction "QC_6") (pintype "output"))
      (node (ref "IC22") (pin "14") (pinfunction "D5_14") (pintype "input"))
    )
    (net (code "205") (name "/PTR_DATA_OUT_3") (class "Default")
      (node (ref "IC13") (pin "14") (pinfunction "4A_14") (pintype "input"))
      (node (ref "IC17") (pin "7") (pinfunction "QD_7") (pintype "output"))
      (node (ref "IC31") (pin "14") (pinfunction "D5_14") (pintype "input"))
    )
    (net (code "206") (name "/PTR_DATA_OUT_4") (class "Default")
      (node (ref "IC21") (pin "2") (pinfunction "1A_2") (pintype "input"))
      (node (ref "IC37") (pin "14") (pinfunction "D5_14") (pintype "input"))
      (node (ref "IC61") (pin "3") (pinfunction "QA_3") (pintype "output"))
    )
    (net (code "207") (name "/PTR_DATA_OUT_5") (class "Default")
      (node (ref "IC21") (pin "5") (pinfunction "2A_5") (pintype "input"))
      (node (ref "IC42") (pin "14") (pinfunction "D5_14") (pintype "input"))
      (node (ref "IC61") (pin "2") (pinfunction "QB_2") (pintype "output"))
    )
    (net (code "208") (name "/PTR_DATA_OUT_6") (class "Default")
      (node (ref "IC21") (pin "11") (pinfunction "3A_11") (pintype "input"))
      (node (ref "IC46") (pin "14") (pinfunction "D5_14") (pintype "input"))
      (node (ref "IC61") (pin "6") (pinfunction "QC_6") (pintype "output"))
    )
    (net (code "209") (name "/PTR_DATA_OUT_7") (class "Default")
      (node (ref "IC21") (pin "14") (pinfunction "4A_14") (pintype "input"))
      (node (ref "IC50") (pin "14") (pinfunction "D5_14") (pintype "input"))
      (node (ref "IC61") (pin "7") (pinfunction "QD_7") (pintype "output"))
    )
    (net (code "210") (name "/PTR_DATA_OUT_8") (class "Default")
      (node (ref "IC27") (pin "2") (pinfunction "1A_2") (pintype "input"))
      (node (ref "IC3") (pin "13") (pinfunction "D6_13") (pintype "input"))
      (node (ref "IC69") (pin "3") (pinfunction "QA_3") (pintype "output"))
    )
    (net (code "211") (name "/PTR_DATA_OUT_9") (class "Default")
      (node (ref "IC15") (pin "13") (pinfunction "D6_13") (pintype "input"))
      (node (ref "IC27") (pin "5") (pinfunction "2A_5") (pintype "input"))
      (node (ref "IC69") (pin "2") (pinfunction "QB_2") (pintype "output"))
    )
    (net (code "212") (name "/PTR_DATA_OUT_10") (class "Default")
      (node (ref "IC22") (pin "13") (pinfunction "D6_13") (pintype "input"))
      (node (ref "IC27") (pin "11") (pinfunction "3A_11") (pintype "input"))
      (node (ref "IC69") (pin "6") (pinfunction "QC_6") (pintype "output"))
    )
    (net (code "213") (name "/PTR_DATA_OUT_11") (class "Default")
      (node (ref "IC27") (pin "14") (pinfunction "4A_14") (pintype "input"))
      (node (ref "IC31") (pin "13") (pinfunction "D6_13") (pintype "input"))
      (node (ref "IC69") (pin "7") (pinfunction "QD_7") (pintype "output"))
    )
    (net (code "214") (name "/PTR_DATA_OUT_12") (class "Default")
      (node (ref "IC34") (pin "2") (pinfunction "1A_2") (pintype "input"))
      (node (ref "IC37") (pin "13") (pinfunction "D6_13") (pintype "input"))
      (node (ref "IC74") (pin "3") (pinfunction "QA_3") (pintype "output"))
    )
    (net (code "215") (name "/PTR_DATA_OUT_13") (class "Default")
      (node (ref "IC34") (pin "5") (pinfunction "2A_5") (pintype "input"))
      (node (ref "IC42") (pin "13") (pinfunction "D6_13") (pintype "input"))
      (node (ref "IC74") (pin "2") (pinfunction "QB_2") (pintype "output"))
    )
    (net (code "216") (name "/PTR_DATA_OUT_14") (class "Default")
      (node (ref "IC34") (pin "11") (pinfunction "3A_11") (pintype "input"))
      (node (ref "IC46") (pin "13") (pinfunction "D6_13") (pintype "input"))
      (node (ref "IC74") (pin "6") (pinfunction "QC_6") (pintype "output"))
    )
    (net (code "217") (name "/PTR_DATA_OUT_15") (class "Default")
      (node (ref "IC34") (pin "14") (pinfunction "4A_14") (pintype "input"))
      (node (ref "IC50") (pin "13") (pinfunction "D6_13") (pintype "input"))
      (node (ref "IC74") (pin "7") (pinfunction "QD_7") (pintype "output"))
    )
    (net (code "218") (name "/PTR_H_LOAD_INPUT_NOT") (class "Default")
      (node (ref "IC39") (pin "4") (pinfunction "O_4") (pintype "output"))
      (node (ref "IC69") (pin "11") (pinfunction "LD_11") (pintype "input"))
      (node (ref "IC74") (pin "11") (pinfunction "LD_11") (pintype "input"))
    )
    (net (code "219") (name "/PTR_L_LOAD_INPUT_NOT") (class "Default")
      (node (ref "IC17") (pin "11") (pinfunction "LD_11") (pintype "input"))
      (node (ref "IC39") (pin "1") (pinfunction "O_1") (pintype "output"))
      (node (ref "IC61") (pin "11") (pinfunction "LD_11") (pintype "input"))
    )
    (net (code "220") (name "/PTR_TO_ABUS") (class "Default")
      (node (ref "IC13") (pin "1") (pinfunction "~{A}/B_1") (pintype "input"))
      (node (ref "IC19") (pin "5") (pinfunction "I0_5") (pintype "input"))
      (node (ref "IC21") (pin "1") (pinfunction "~{A}/B_1") (pintype "input"))
      (node (ref "IC27") (pin "1") (pinfunction "~{A}/B_1") (pintype "input"))
      (node (ref "IC34") (pin "1") (pinfunction "~{A}/B_1") (pintype "input"))
      (node (ref "IC68") (pin "3") (pinfunction "O_3") (pintype "output"))
    )
    (net (code "221") (name "/PUSH") (class "Default")
      (node (ref "IC126") (pin "5") (pinfunction "I1_5") (pintype "input"))
      (node (ref "IC130") (pin "5") (pinfunction "I1_5") (pintype "input"))
      (node (ref "IC48") (pin "10") (pinfunction "I1_10") (pintype "input"))
      (node (ref "IC95") (pin "8") (pinfunction "O_8") (pintype "output"))
    )
    (net (code "222") (name "/REG0_ZERO") (class "Default")
      (node (ref "IC39") (pin "10") (pinfunction "O_10") (pintype "output"))
      (node (ref "IC78") (pin "1") (pinfunction "I0_1") (pintype "input"))
      (node (ref "IC78") (pin "4") (pinfunction "I0_4") (pintype "input"))
      (node (ref "JP4") (pin "20") (pinfunction "20_20") (pintype "passive"))
    )
    (net (code "223") (name "/REGISTER_OUTPUT_SEL_0") (class "Default")
      (node (ref "IC12") (pin "4") (pinfunction "1Y_4") (pintype "output"))
      (node (ref "IC15") (pin "11") (pinfunction "A_11") (pintype "input"))
      (node (ref "IC16") (pin "11") (pinfunction "A_11") (pintype "input"))
      (node (ref "IC22") (pin "11") (pinfunction "A_11") (pintype "input"))
      (node (ref "IC23") (pin "11") (pinfunction "A_11") (pintype "input"))
      (node (ref "IC3") (pin "11") (pinfunction "A_11") (pintype "input"))
      (node (ref "IC31") (pin "11") (pinfunction "A_11") (pintype "input"))
      (node (ref "IC32") (pin "11") (pinfunction "A_11") (pintype "input"))
      (node (ref "IC37") (pin "11") (pinfunction "A_11") (pintype "input"))
      (node (ref "IC38") (pin "11") (pinfunction "A_11") (pintype "input"))
      (node (ref "IC4") (pin "11") (pinfunction "A_11") (pintype "input"))
      (node (ref "IC42") (pin "11") (pinfunction "A_11") (pintype "input"))
      (node (ref "IC43") (pin "11") (pinfunction "A_11") (pintype "input"))
      (node (ref "IC46") (pin "11") (pinfunction "A_11") (pintype "input"))
      (node (ref "IC47") (pin "11") (pinfunction "A_11") (pintype "input"))
      (node (ref "IC50") (pin "11") (pinfunction "A_11") (pintype "input"))
      (node (ref "IC51") (pin "11") (pinfunction "A_11") (pintype "input"))
    )
    (net (code "224") (name "/REGISTER_OUTPUT_SEL_0_") (class "Default")
      (node (ref "IC11") (pin "4") (pinfunction "1Y_4") (pintype "output"))
      (node (ref "IC12") (pin "2") (pinfunction "1A_2") (pintype "input"))
    )
    (net (code "225") (name "/REGISTER_OUTPUT_SEL_1") (class "Default")
      (node (ref "IC12") (pin "7") (pinfunction "2Y_7") (pintype "output"))
      (node (ref "IC15") (pin "10") (pinfunction "B_10") (pintype "input"))
      (node (ref "IC16") (pin "10") (pinfunction "B_10") (pintype "input"))
      (node (ref "IC22") (pin "10") (pinfunction "B_10") (pintype "input"))
      (node (ref "IC23") (pin "10") (pinfunction "B_10") (pintype "input"))
      (node (ref "IC3") (pin "10") (pinfunction "B_10") (pintype "input"))
      (node (ref "IC31") (pin "10") (pinfunction "B_10") (pintype "input"))
      (node (ref "IC32") (pin "10") (pinfunction "B_10") (pintype "input"))
      (node (ref "IC37") (pin "10") (pinfunction "B_10") (pintype "input"))
      (node (ref "IC38") (pin "10") (pinfunction "B_10") (pintype "input"))
      (node (ref "IC4") (pin "10") (pinfunction "B_10") (pintype "input"))
      (node (ref "IC42") (pin "10") (pinfunction "B_10") (pintype "input"))
      (node (ref "IC43") (pin "10") (pinfunction "B_10") (pintype "input"))
      (node (ref "IC46") (pin "10") (pinfunction "B_10") (pintype "input"))
      (node (ref "IC47") (pin "10") (pinfunction "B_10") (pintype "input"))
      (node (ref "IC50") (pin "10") (pinfunction "B_10") (pintype "input"))
      (node (ref "IC51") (pin "10") (pinfunction "B_10") (pintype "input"))
    )
    (net (code "226") (name "/REGISTER_OUTPUT_SEL_1_") (class "Default")
      (node (ref "IC11") (pin "7") (pinfunction "2Y_7") (pintype "output"))
      (node (ref "IC12") (pin "5") (pinfunction "2A_5") (pintype "input"))
    )
    (net (code "227") (name "/REGISTER_OUTPUT_SEL_2") (class "Default")
      (node (ref "IC12") (pin "9") (pinfunction "3Y_9") (pintype "output"))
      (node (ref "IC15") (pin "9") (pinfunction "C_9") (pintype "input"))
      (node (ref "IC16") (pin "9") (pinfunction "C_9") (pintype "input"))
      (node (ref "IC22") (pin "9") (pinfunction "C_9") (pintype "input"))
      (node (ref "IC23") (pin "9") (pinfunction "C_9") (pintype "input"))
      (node (ref "IC3") (pin "9") (pinfunction "C_9") (pintype "input"))
      (node (ref "IC31") (pin "9") (pinfunction "C_9") (pintype "input"))
      (node (ref "IC32") (pin "9") (pinfunction "C_9") (pintype "input"))
      (node (ref "IC37") (pin "9") (pinfunction "C_9") (pintype "input"))
      (node (ref "IC38") (pin "9") (pinfunction "C_9") (pintype "input"))
      (node (ref "IC4") (pin "9") (pinfunction "C_9") (pintype "input"))
      (node (ref "IC42") (pin "9") (pinfunction "C_9") (pintype "input"))
      (node (ref "IC43") (pin "9") (pinfunction "C_9") (pintype "input"))
      (node (ref "IC46") (pin "9") (pinfunction "C_9") (pintype "input"))
      (node (ref "IC47") (pin "9") (pinfunction "C_9") (pintype "input"))
      (node (ref "IC50") (pin "9") (pinfunction "C_9") (pintype "input"))
      (node (ref "IC51") (pin "9") (pinfunction "C_9") (pintype "input"))
    )
    (net (code "228") (name "/REGISTER_OUTPUT_SEL_2_") (class "Default")
      (node (ref "IC11") (pin "9") (pinfunction "3Y_9") (pintype "output"))
      (node (ref "IC12") (pin "11") (pinfunction "3A_11") (pintype "input"))
    )
    (net (code "229") (name "/REGISTER_OUTPUT_SEL_3") (class "Default")
      (node (ref "IC12") (pin "12") (pinfunction "4Y_12") (pintype "output"))
      (node (ref "IC129") (pin "3") (pinfunction "I_3") (pintype "input"))
      (node (ref "IC131") (pin "12") (pinfunction "D_12") (pintype "input"))
      (node (ref "IC59") (pin "12") (pinfunction "I0_12") (pintype "input"))
    )
    (net (code "230") (name "/REGISTER_OUTPUT_SEL_3_") (class "Default")
      (node (ref "IC11") (pin "12") (pinfunction "4Y_12") (pintype "output"))
      (node (ref "IC12") (pin "14") (pinfunction "4A_14") (pintype "input"))
    )
    (net (code "231") (name "/REG_0_LOAD_INPUT") (class "Default")
      (node (ref "IC29") (pin "1") (pinfunction "O_1") (pintype "output"))
      (node (ref "IC33") (pin "11") (pinfunction "CLK_11") (pintype "input"))
    )
    (net (code "232") (name "/REG_0_OUT_0") (class "Default")
      (node (ref "IC3") (pin "3") (pinfunction "D1_3") (pintype "input"))
      (node (ref "IC33") (pin "2") (pinfunction "1Q_2") (pintype "tri_state"))
      (node (ref "IC96") (pin "1") (pinfunction "I0_1") (pintype "input"))
      (node (ref "JP4") (pin "23") (pinfunction "23_23") (pintype "passive"))
    )
    (net (code "233") (name "/REG_0_OUT_1") (class "Default")
      (node (ref "IC15") (pin "3") (pinfunction "D1_3") (pintype "input"))
      (node (ref "IC33") (pin "5") (pinfunction "2Q_5") (pintype "tri_state"))
      (node (ref "IC96") (pin "2") (pinfunction "I1_2") (pintype "input"))
      (node (ref "JP4") (pin "25") (pinfunction "25_25") (pintype "passive"))
    )
    (net (code "234") (name "/REG_0_OUT_2") (class "Default")
      (node (ref "IC22") (pin "3") (pinfunction "D1_3") (pintype "input"))
      (node (ref "IC33") (pin "6") (pinfunction "3Q_6") (pintype "tri_state"))
      (node (ref "IC96") (pin "12") (pinfunction "I0_12") (pintype "input"))
      (node (ref "JP4") (pin "27") (pinfunction "27_27") (pintype "passive"))
    )
    (net (code "235") (name "/REG_0_OUT_3") (class "Default")
      (node (ref "IC31") (pin "3") (pinfunction "D1_3") (pintype "input"))
      (node (ref "IC33") (pin "9") (pinfunction "4Q_9") (pintype "tri_state"))
      (node (ref "IC96") (pin "13") (pinfunction "I1_13") (pintype "input"))
      (node (ref "JP4") (pin "29") (pinfunction "29_29") (pintype "passive"))
    )
    (net (code "236") (name "/REG_0_OUT_4") (class "Default")
      (node (ref "IC33") (pin "12") (pinfunction "5Q_12") (pintype "tri_state"))
      (node (ref "IC37") (pin "3") (pinfunction "D1_3") (pintype "input"))
      (node (ref "IC94") (pin "9") (pinfunction "I0_9") (pintype "input"))
      (node (ref "JP4") (pin "31") (pinfunction "31_31") (pintype "passive"))
    )
    (net (code "237") (name "/REG_0_OUT_5") (class "Default")
      (node (ref "IC33") (pin "15") (pinfunction "6Q_15") (pintype "tri_state"))
      (node (ref "IC42") (pin "3") (pinfunction "D1_3") (pintype "input"))
      (node (ref "IC94") (pin "10") (pinfunction "I1_10") (pintype "input"))
      (node (ref "JP4") (pin "33") (pinfunction "33_33") (pintype "passive"))
    )
    (net (code "238") (name "/REG_0_OUT_6") (class "Default")
      (node (ref "IC33") (pin "16") (pinfunction "7Q_16") (pintype "tri_state"))
      (node (ref "IC46") (pin "3") (pinfunction "D1_3") (pintype "input"))
      (node (ref "IC94") (pin "12") (pinfunction "I0_12") (pintype "input"))
      (node (ref "JP4") (pin "35") (pinfunction "35_35") (pintype "passive"))
    )
    (net (code "239") (name "/REG_0_OUT_7") (class "Default")
      (node (ref "IC33") (pin "19") (pinfunction "8Q_19") (pintype "tri_state"))
      (node (ref "IC50") (pin "3") (pinfunction "D1_3") (pintype "input"))
      (node (ref "IC94") (pin "13") (pinfunction "I1_13") (pintype "input"))
      (node (ref "JP4") (pin "37") (pinfunction "37_37") (pintype "passive"))
    )
    (net (code "240") (name "/REG_1_LOAD_INPUT") (class "Default")
      (node (ref "IC26") (pin "11") (pinfunction "CLK_11") (pintype "input"))
      (node (ref "IC29") (pin "4") (pinfunction "O_4") (pintype "output"))
    )
    (net (code "241") (name "/REG_1_OUT_0") (class "Default")
      (node (ref "IC26") (pin "2") (pinfunction "1Q_2") (pintype "tri_state"))
      (node (ref "IC3") (pin "2") (pinfunction "D2_2") (pintype "input"))
    )
    (net (code "242") (name "/REG_1_OUT_1") (class "Default")
      (node (ref "IC15") (pin "2") (pinfunction "D2_2") (pintype "input"))
      (node (ref "IC26") (pin "5") (pinfunction "2Q_5") (pintype "tri_state"))
    )
    (net (code "243") (name "/REG_1_OUT_2") (class "Default")
      (node (ref "IC22") (pin "2") (pinfunction "D2_2") (pintype "input"))
      (node (ref "IC26") (pin "6") (pinfunction "3Q_6") (pintype "tri_state"))
    )
    (net (code "244") (name "/REG_1_OUT_3") (class "Default")
      (node (ref "IC26") (pin "9") (pinfunction "4Q_9") (pintype "tri_state"))
      (node (ref "IC31") (pin "2") (pinfunction "D2_2") (pintype "input"))
    )
    (net (code "245") (name "/REG_1_OUT_4") (class "Default")
      (node (ref "IC26") (pin "12") (pinfunction "5Q_12") (pintype "tri_state"))
      (node (ref "IC37") (pin "2") (pinfunction "D2_2") (pintype "input"))
    )
    (net (code "246") (name "/REG_1_OUT_5") (class "Default")
      (node (ref "IC26") (pin "15") (pinfunction "6Q_15") (pintype "tri_state"))
      (node (ref "IC42") (pin "2") (pinfunction "D2_2") (pintype "input"))
    )
    (net (code "247") (name "/REG_1_OUT_6") (class "Default")
      (node (ref "IC26") (pin "16") (pinfunction "7Q_16") (pintype "tri_state"))
      (node (ref "IC46") (pin "2") (pinfunction "D2_2") (pintype "input"))
    )
    (net (code "248") (name "/REG_1_OUT_7") (class "Default")
      (node (ref "IC26") (pin "19") (pinfunction "8Q_19") (pintype "tri_state"))
      (node (ref "IC50") (pin "2") (pinfunction "D2_2") (pintype "input"))
    )
    (net (code "249") (name "/REG_2_LOAD_INPUT") (class "Default")
      (node (ref "IC18") (pin "11") (pinfunction "CLK_11") (pintype "input"))
      (node (ref "IC29") (pin "10") (pinfunction "O_10") (pintype "output"))
    )
    (net (code "250") (name "/REG_2_OUT_0") (class "Default")
      (node (ref "IC18") (pin "2") (pinfunction "1Q_2") (pintype "tri_state"))
      (node (ref "IC3") (pin "1") (pinfunction "D3_1") (pintype "input"))
    )
    (net (code "251") (name "/REG_2_OUT_1") (class "Default")
      (node (ref "IC15") (pin "1") (pinfunction "D3_1") (pintype "input"))
      (node (ref "IC18") (pin "5") (pinfunction "2Q_5") (pintype "tri_state"))
    )
    (net (code "252") (name "/REG_2_OUT_2") (class "Default")
      (node (ref "IC18") (pin "6") (pinfunction "3Q_6") (pintype "tri_state"))
      (node (ref "IC22") (pin "1") (pinfunction "D3_1") (pintype "input"))
    )
    (net (code "253") (name "/REG_2_OUT_3") (class "Default")
      (node (ref "IC18") (pin "9") (pinfunction "4Q_9") (pintype "tri_state"))
      (node (ref "IC31") (pin "1") (pinfunction "D3_1") (pintype "input"))
    )
    (net (code "254") (name "/REG_2_OUT_4") (class "Default")
      (node (ref "IC18") (pin "12") (pinfunction "5Q_12") (pintype "tri_state"))
      (node (ref "IC37") (pin "1") (pinfunction "D3_1") (pintype "input"))
    )
    (net (code "255") (name "/REG_2_OUT_5") (class "Default")
      (node (ref "IC18") (pin "15") (pinfunction "6Q_15") (pintype "tri_state"))
      (node (ref "IC42") (pin "1") (pinfunction "D3_1") (pintype "input"))
    )
    (net (code "256") (name "/REG_2_OUT_6") (class "Default")
      (node (ref "IC18") (pin "16") (pinfunction "7Q_16") (pintype "tri_state"))
      (node (ref "IC46") (pin "1") (pinfunction "D3_1") (pintype "input"))
    )
    (net (code "257") (name "/REG_2_OUT_7") (class "Default")
      (node (ref "IC18") (pin "19") (pinfunction "8Q_19") (pintype "tri_state"))
      (node (ref "IC50") (pin "1") (pinfunction "D3_1") (pintype "input"))
    )
    (net (code "258") (name "/REG_3_LOAD_INPUT") (class "Default")
      (node (ref "IC29") (pin "13") (pinfunction "O_13") (pintype "output"))
      (node (ref "IC5") (pin "11") (pinfunction "CLK_11") (pintype "input"))
    )
    (net (code "259") (name "/REG_3_OUT_0") (class "Default")
      (node (ref "IC3") (pin "15") (pinfunction "D4_15") (pintype "input"))
      (node (ref "IC5") (pin "2") (pinfunction "1Q_2") (pintype "tri_state"))
    )
    (net (code "260") (name "/REG_3_OUT_1") (class "Default")
      (node (ref "IC15") (pin "15") (pinfunction "D4_15") (pintype "input"))
      (node (ref "IC5") (pin "5") (pinfunction "2Q_5") (pintype "tri_state"))
    )
    (net (code "261") (name "/REG_3_OUT_2") (class "Default")
      (node (ref "IC22") (pin "15") (pinfunction "D4_15") (pintype "input"))
      (node (ref "IC5") (pin "6") (pinfunction "3Q_6") (pintype "tri_state"))
    )
    (net (code "262") (name "/REG_3_OUT_3") (class "Default")
      (node (ref "IC31") (pin "15") (pinfunction "D4_15") (pintype "input"))
      (node (ref "IC5") (pin "9") (pinfunction "4Q_9") (pintype "tri_state"))
    )
    (net (code "263") (name "/REG_3_OUT_4") (class "Default")
      (node (ref "IC37") (pin "15") (pinfunction "D4_15") (pintype "input"))
      (node (ref "IC5") (pin "12") (pinfunction "5Q_12") (pintype "tri_state"))
    )
    (net (code "264") (name "/REG_3_OUT_5") (class "Default")
      (node (ref "IC42") (pin "15") (pinfunction "D4_15") (pintype "input"))
      (node (ref "IC5") (pin "15") (pinfunction "6Q_15") (pintype "tri_state"))
    )
    (net (code "265") (name "/REG_3_OUT_6") (class "Default")
      (node (ref "IC46") (pin "15") (pinfunction "D4_15") (pintype "input"))
      (node (ref "IC5") (pin "16") (pinfunction "7Q_16") (pintype "tri_state"))
    )
    (net (code "266") (name "/REG_3_OUT_7") (class "Default")
      (node (ref "IC5") (pin "19") (pinfunction "8Q_19") (pintype "tri_state"))
      (node (ref "IC50") (pin "15") (pinfunction "D4_15") (pintype "input"))
    )
    (net (code "267") (name "/RING_CNTR_CLOCK") (class "Default")
      (node (ref "IC105") (pin "11") (pinfunction "CLK_11") (pintype "input"))
      (node (ref "IC105") (pin "3") (pinfunction "CLK_3") (pintype "input"))
      (node (ref "IC129") (pin "5") (pinfunction "I_5") (pintype "input"))
      (node (ref "IC53") (pin "11") (pinfunction "CLK_11") (pintype "input"))
      (node (ref "IC53") (pin "3") (pinfunction "CLK_3") (pintype "input"))
      (node (ref "IC54") (pin "11") (pinfunction "CLK_11") (pintype "input"))
      (node (ref "IC54") (pin "3") (pinfunction "CLK_3") (pintype "input"))
      (node (ref "IC59") (pin "13") (pinfunction "I1_13") (pintype "input"))
      (node (ref "IC59") (pin "2") (pinfunction "I1_2") (pintype "input"))
      (node (ref "JP4") (pin "4") (pinfunction "4_4") (pintype "passive"))
    )
    (net (code "268") (name "/SECOND_LATCH_SELECT") (class "Default")
      (node (ref "IC12") (pin "1") (pinfunction "~{A}/B_1") (pintype "input"))
      (node (ref "IC12") (pin "13") (pinfunction "4B_13") (pintype "input"))
      (node (ref "IC65") (pin "8") (pinfunction "O_8") (pintype "output"))
    )
    (net (code "269") (name "/SELECT_CARRY_BIT") (class "Default")
      (node (ref "IC70") (pin "8") (pinfunction "O_8") (pintype "output"))
      (node (ref "IC72") (pin "10") (pinfunction "I1_10") (pintype "input"))
      (node (ref "IC72") (pin "13") (pinfunction "I1_13") (pintype "input"))
      (node (ref "IC72") (pin "2") (pinfunction "I1_2") (pintype "input"))
      (node (ref "IC89") (pin "5") (pinfunction "I1_5") (pintype "input"))
    )
    (net (code "270") (name "/SP_COUNT_DOWN") (class "Default")
      (node (ref "IC130") (pin "11") (pinfunction "O_11") (pintype "output"))
      (node (ref "IC93") (pin "4") (pinfunction "DN_4") (pintype "input"))
    )
    (net (code "271") (name "/SP_COUNT_UP{slash}WRITE_REG_TO_DBUS_SELECTOR2_PUSH") (class "Default")
      (node (ref "IC130") (pin "6") (pinfunction "O_6") (pintype "output"))
      (node (ref "IC55") (pin "10") (pinfunction "I1_10") (pintype "input"))
      (node (ref "IC93") (pin "5") (pinfunction "UP_5") (pintype "input"))
    )
    (net (code "272") (name "/SP_DATA_OUT_0") (class "Default")
      (node (ref "IC93") (pin "3") (pinfunction "QA_3") (pintype "output"))
      (node (ref "JP2") (pin "1") (pinfunction "1_1") (pintype "passive"))
    )
    (net (code "273") (name "/SP_DATA_OUT_1") (class "Default")
      (node (ref "IC93") (pin "2") (pinfunction "QB_2") (pintype "output"))
      (node (ref "JP2") (pin "3") (pinfunction "3_3") (pintype "passive"))
    )
    (net (code "274") (name "/SP_DATA_OUT_2") (class "Default")
      (node (ref "IC93") (pin "6") (pinfunction "QC_6") (pintype "output"))
      (node (ref "JP2") (pin "5") (pinfunction "5_5") (pintype "passive"))
    )
    (net (code "275") (name "/SP_DATA_OUT_3") (class "Default")
      (node (ref "IC93") (pin "7") (pinfunction "QD_7") (pintype "output"))
      (node (ref "JP2") (pin "7") (pinfunction "7_7") (pintype "passive"))
    )
    (net (code "276") (name "/SP_DATA_OUT_4") (class "Default")
      (node (ref "IC97") (pin "3") (pinfunction "QA_3") (pintype "output"))
      (node (ref "JP2") (pin "9") (pinfunction "9_9") (pintype "passive"))
    )
    (net (code "277") (name "/SP_DATA_OUT_5") (class "Default")
      (node (ref "IC97") (pin "2") (pinfunction "QB_2") (pintype "output"))
      (node (ref "JP2") (pin "11") (pinfunction "11_11") (pintype "passive"))
    )
    (net (code "278") (name "/SP_DATA_OUT_6") (class "Default")
      (node (ref "IC97") (pin "6") (pinfunction "QC_6") (pintype "output"))
      (node (ref "JP2") (pin "13") (pinfunction "13_13") (pintype "passive"))
    )
    (net (code "279") (name "/SP_DATA_OUT_7") (class "Default")
      (node (ref "IC97") (pin "7") (pinfunction "QD_7") (pintype "output"))
      (node (ref "JP2") (pin "15") (pinfunction "15_15") (pintype "passive"))
    )
    (net (code "280") (name "/SP_DATA_OUT_8") (class "Default")
      (node (ref "IC102") (pin "3") (pinfunction "QA_3") (pintype "output"))
      (node (ref "JP2") (pin "17") (pinfunction "17_17") (pintype "passive"))
    )
    (net (code "281") (name "/SP_DATA_OUT_9") (class "Default")
      (node (ref "IC102") (pin "2") (pinfunction "QB_2") (pintype "output"))
      (node (ref "JP2") (pin "19") (pinfunction "19_19") (pintype "passive"))
    )
    (net (code "282") (name "/SP_DATA_OUT_10") (class "Default")
      (node (ref "IC102") (pin "6") (pinfunction "QC_6") (pintype "output"))
      (node (ref "JP2") (pin "21") (pinfunction "21_21") (pintype "passive"))
    )
    (net (code "283") (name "/SP_DATA_OUT_11") (class "Default")
      (node (ref "IC102") (pin "7") (pinfunction "QD_7") (pintype "output"))
      (node (ref "JP2") (pin "23") (pinfunction "23_23") (pintype "passive"))
    )
    (net (code "284") (name "/SP_DATA_OUT_12") (class "Default")
      (node (ref "IC106") (pin "3") (pinfunction "QA_3") (pintype "output"))
      (node (ref "JP2") (pin "25") (pinfunction "25_25") (pintype "passive"))
    )
    (net (code "285") (name "/SP_DATA_OUT_13") (class "Default")
      (node (ref "IC106") (pin "2") (pinfunction "QB_2") (pintype "output"))
      (node (ref "JP2") (pin "27") (pinfunction "27_27") (pintype "passive"))
    )
    (net (code "286") (name "/SP_DATA_OUT_14") (class "Default")
      (node (ref "IC106") (pin "6") (pinfunction "QC_6") (pintype "output"))
      (node (ref "JP2") (pin "29") (pinfunction "29_29") (pintype "passive"))
    )
    (net (code "287") (name "/SP_DATA_OVER{slash}UNDERFLOW") (class "Default")
      (node (ref "IC106") (pin "7") (pinfunction "QD_7") (pintype "output"))
      (node (ref "JP4") (pin "18") (pinfunction "18_18") (pintype "passive"))
    )
    (net (code "288") (name "/STATE_0{slash}CYCL_3") (class "Default")
      (node (ref "IC100") (pin "12") (pinfunction "I0_12") (pintype "input"))
      (node (ref "IC100") (pin "4") (pinfunction "I0_4") (pintype "input"))
      (node (ref "IC100") (pin "9") (pinfunction "I0_9") (pintype "input"))
      (node (ref "IC130") (pin "4") (pinfunction "I0_4") (pintype "input"))
      (node (ref "IC40") (pin "9") (pinfunction "I0_9") (pintype "input"))
      (node (ref "IC52") (pin "1") (pinfunction "I0_1") (pintype "input"))
      (node (ref "IC54") (pin "12") (pinfunction "D_12") (pintype "input"))
      (node (ref "IC54") (pin "5") (pinfunction "Q_5") (pintype "output"))
      (node (ref "IC99") (pin "1") (pinfunction "I0_1") (pintype "input"))
      (node (ref "JP4") (pin "30") (pinfunction "30_30") (pintype "passive"))
    )
    (net (code "289") (name "/STATE_1{slash}CYCL_4") (class "Default")
      (node (ref "IC100") (pin "1") (pinfunction "I0_1") (pintype "input"))
      (node (ref "IC105") (pin "2") (pinfunction "D_2") (pintype "input"))
      (node (ref "IC108") (pin "1") (pinfunction "I0_1") (pintype "input"))
      (node (ref "IC126") (pin "4") (pinfunction "I0_4") (pintype "input"))
      (node (ref "IC130") (pin "12") (pinfunction "I0_12") (pintype "input"))
      (node (ref "IC130") (pin "9") (pinfunction "I0_9") (pintype "input"))
      (node (ref "IC40") (pin "4") (pinfunction "I0_4") (pintype "input"))
      (node (ref "IC52") (pin "4") (pinfunction "I0_4") (pintype "input"))
      (node (ref "IC54") (pin "9") (pinfunction "Q_9") (pintype "output"))
      (node (ref "IC72") (pin "1") (pinfunction "I0_1") (pintype "input"))
      (node (ref "IC78") (pin "9") (pinfunction "I0_9") (pintype "input"))
      (node (ref "IC89") (pin "1") (pinfunction "I0_1") (pintype "input"))
      (node (ref "IC92") (pin "1") (pinfunction "I0_1") (pintype "input"))
      (node (ref "JP4") (pin "32") (pinfunction "32_32") (pintype "passive"))
    )
    (net (code "290") (name "/STATE_2{slash}CYCL_5") (class "Default")
      (node (ref "IC105") (pin "12") (pinfunction "D_12") (pintype "input"))
      (node (ref "IC105") (pin "5") (pinfunction "Q_5") (pintype "output"))
      (node (ref "IC126") (pin "1") (pinfunction "I0_1") (pintype "input"))
      (node (ref "IC40") (pin "12") (pinfunction "I0_12") (pintype "input"))
      (node (ref "IC52") (pin "12") (pinfunction "I0_12") (pintype "input"))
      (node (ref "IC72") (pin "9") (pinfunction "I0_9") (pintype "input"))
      (node (ref "IC88") (pin "9") (pinfunction "I0_9") (pintype "input"))
      (node (ref "IC92") (pin "4") (pinfunction "I0_4") (pintype "input"))
      (node (ref "IC99") (pin "4") (pinfunction "I0_4") (pintype "input"))
      (node (ref "JP4") (pin "34") (pinfunction "34_34") (pintype "passive"))
    )
    (net (code "291") (name "/STATE_3{slash}CYCL_6") (class "Default")
      (node (ref "IC105") (pin "9") (pinfunction "Q_9") (pintype "output"))
      (node (ref "IC126") (pin "12") (pinfunction "I0_12") (pintype "input"))
      (node (ref "IC126") (pin "9") (pinfunction "I0_9") (pintype "input"))
      (node (ref "IC40") (pin "1") (pinfunction "I0_1") (pintype "input"))
      (node (ref "IC52") (pin "9") (pinfunction "I0_9") (pintype "input"))
      (node (ref "IC53") (pin "2") (pinfunction "D_2") (pintype "input"))
      (node (ref "IC72") (pin "12") (pinfunction "I0_12") (pintype "input"))
      (node (ref "JP4") (pin "36") (pinfunction "36_36") (pintype "passive"))
    )
    (net (code "292") (name "/STORE_ALU_OUTPUT") (class "Default")
      (node (ref "IC101") (pin "11") (pinfunction "ENC_11") (pintype "input"))
      (node (ref "IC49") (pin "6") (pinfunction "O_6") (pintype "output"))
    )
    (net (code "293") (name "/STORE_ALU_OUTPUT_JMP_O") (class "Default")
      (node (ref "IC40") (pin "11") (pinfunction "O_11") (pintype "output"))
      (node (ref "IC49") (pin "5") (pinfunction "I1_5") (pintype "input"))
      (node (ref "IC88") (pin "13") (pinfunction "I1_13") (pintype "input"))
      (node (ref "IC88") (pin "5") (pinfunction "I1_5") (pintype "input"))
    )
    (net (code "294") (name "/STORE_ALU_OUTPUT{slash}STORE_CARRY_ALU") (class "Default")
      (node (ref "IC49") (pin "4") (pinfunction "I0_4") (pintype "input"))
      (node (ref "IC67") (pin "9") (pinfunction "I_9") (pintype "input"))
      (node (ref "IC72") (pin "8") (pinfunction "O_8") (pintype "output"))
    )
    (net (code "295") (name "/STR") (class "Default")
      (node (ref "IC71") (pin "2") (pinfunction "I1_2") (pintype "input"))
      (node (ref "IC95") (pin "6") (pinfunction "O_6") (pintype "output"))
    )
    (net (code "296") (name "/STR_I") (class "Default")
      (node (ref "IC71") (pin "1") (pinfunction "I0_1") (pintype "input"))
      (node (ref "IC95") (pin "3") (pinfunction "O_3") (pintype "output"))
      (node (ref "IC99") (pin "5") (pinfunction "I1_5") (pintype "input"))
    )
    (net (code "297") (name "/STR{slash}STR_I") (class "Default")
      (node (ref "IC100") (pin "13") (pinfunction "I1_13") (pintype "input"))
      (node (ref "IC130") (pin "10") (pinfunction "I1_10") (pintype "input"))
      (node (ref "IC48") (pin "9") (pinfunction "I0_9") (pintype "input"))
      (node (ref "IC71") (pin "3") (pinfunction "O_3") (pintype "output"))
    )
    (net (code "298") (name "/TABLE_1_INPUT_PTR_HIGH") (class "Default")
      (node (ref "IC10") (pin "6") (pinfunction "O_6") (pintype "output"))
      (node (ref "IC39") (pin "5") (pinfunction "I0_5") (pintype "input"))
    )
    (net (code "299") (name "/TABLE_1_INPUT_PTR_L") (class "Default")
      (node (ref "IC10") (pin "3") (pinfunction "O_3") (pintype "output"))
      (node (ref "IC39") (pin "2") (pinfunction "I0_2") (pintype "input"))
    )
    (net (code "300") (name "/TABLE_1_INPUT_REG0") (class "Default")
      (node (ref "IC2") (pin "3") (pinfunction "O_3") (pintype "output"))
      (node (ref "IC29") (pin "2") (pinfunction "I0_2") (pintype "input"))
    )
    (net (code "301") (name "/TABLE_1_INPUT_REG1") (class "Default")
      (node (ref "IC2") (pin "6") (pinfunction "O_6") (pintype "output"))
      (node (ref "IC29") (pin "5") (pinfunction "I0_5") (pintype "input"))
    )
    (net (code "302") (name "/TABLE_1_INPUT_REG2") (class "Default")
      (node (ref "IC2") (pin "8") (pinfunction "O_8") (pintype "output"))
      (node (ref "IC29") (pin "8") (pinfunction "I0_8") (pintype "input"))
    )
    (net (code "303") (name "/TABLE_1_INPUT_REG3") (class "Default")
      (node (ref "IC2") (pin "11") (pinfunction "O_11") (pintype "output"))
      (node (ref "IC29") (pin "11") (pinfunction "I0_11") (pintype "input"))
    )
    (net (code "304") (name "/TIMER_CLOCK") (class "Default")
      (node (ref "IC75") (pin "5") (pinfunction "UP_5") (pintype "input"))
      (node (ref "JP4") (pin "3") (pinfunction "3_3") (pintype "passive"))
    )
    (net (code "305") (name "/TIMER_REG_0") (class "Default")
      (node (ref "IC4") (pin "12") (pinfunction "D7_12") (pintype "input"))
      (node (ref "IC75") (pin "3") (pinfunction "QA_3") (pintype "output"))
    )
    (net (code "306") (name "/TIMER_REG_1") (class "Default")
      (node (ref "IC16") (pin "12") (pinfunction "D7_12") (pintype "input"))
      (node (ref "IC75") (pin "2") (pinfunction "QB_2") (pintype "output"))
    )
    (net (code "307") (name "/TIMER_REG_2") (class "Default")
      (node (ref "IC23") (pin "12") (pinfunction "D7_12") (pintype "input"))
      (node (ref "IC75") (pin "6") (pinfunction "QC_6") (pintype "output"))
    )
    (net (code "308") (name "/TIMER_REG_3") (class "Default")
      (node (ref "IC32") (pin "12") (pinfunction "D7_12") (pintype "input"))
      (node (ref "IC75") (pin "7") (pinfunction "QD_7") (pintype "output"))
    )
    (net (code "309") (name "/TIMER_REG_4") (class "Default")
      (node (ref "IC38") (pin "12") (pinfunction "D7_12") (pintype "input"))
      (node (ref "IC80") (pin "3") (pinfunction "QA_3") (pintype "output"))
    )
    (net (code "310") (name "/TIMER_REG_5") (class "Default")
      (node (ref "IC43") (pin "12") (pinfunction "D7_12") (pintype "input"))
      (node (ref "IC80") (pin "2") (pinfunction "QB_2") (pintype "output"))
    )
    (net (code "311") (name "/TIMER_REG_6") (class "Default")
      (node (ref "IC47") (pin "12") (pinfunction "D7_12") (pintype "input"))
      (node (ref "IC80") (pin "6") (pinfunction "QC_6") (pintype "output"))
    )
    (net (code "312") (name "/TIMER_REG_7") (class "Default")
      (node (ref "IC51") (pin "12") (pinfunction "D7_12") (pintype "input"))
      (node (ref "IC80") (pin "7") (pinfunction "QD_7") (pintype "output"))
    )
    (net (code "313") (name "/TWO_BYTE_CMD") (class "Default")
      (node (ref "IC14") (pin "10") (pinfunction "O_10") (pintype "output"))
      (node (ref "IC89") (pin "13") (pinfunction "I1_13") (pintype "input"))
    )
    (net (code "314") (name "/WRITE_LR_L_DBUS_RET") (class "Default")
      (node (ref "IC65") (pin "1") (pinfunction "I0_1") (pintype "input"))
      (node (ref "IC99") (pin "3") (pinfunction "O_3") (pintype "output"))
    )
    (net (code "315") (name "/WRITE_PC_H{slash}WRITE_PC_L_DBUS_SAVE_LR") (class "Default")
      (node (ref "IC12") (pin "10") (pinfunction "3B_10") (pintype "input"))
      (node (ref "IC65") (pin "10") (pinfunction "I1_10") (pintype "input"))
      (node (ref "IC65") (pin "11") (pinfunction "O_11") (pintype "output"))
    )
    (net (code "316") (name "/WRITE_PC_L_DBUS_JMP_O") (class "Default")
      (node (ref "IC40") (pin "8") (pinfunction "O_8") (pintype "output"))
      (node (ref "IC56") (pin "2") (pinfunction "I1_2") (pintype "input"))
    )
    (net (code "317") (name "/WRITE_PC_L_DBUS_SAVE_LR") (class "Default")
      (node (ref "IC56") (pin "1") (pinfunction "I0_1") (pintype "input"))
      (node (ref "IC78") (pin "8") (pinfunction "O_8") (pintype "output"))
    )
    (net (code "318") (name "/WRITE_PTR_TO_ABUS{slash}CLR_NOT_OE{slash}CLR_NOT_CS{slash}FILL_REGISTER_LDR") (class "Default")
      (node (ref "IC100") (pin "8") (pinfunction "O_8") (pintype "output"))
      (node (ref "IC68") (pin "1") (pinfunction "I0_1") (pintype "input"))
      (node (ref "IC68") (pin "5") (pinfunction "I1_5") (pintype "input"))
      (node (ref "IC96") (pin "5") (pinfunction "I1_5") (pintype "input"))
    )
    (net (code "319") (name "/WRITE_PTR_TO_ABUS{slash}CLR_NOT_WE{slash}CLR_NOT_CS_STR") (class "Default")
      (node (ref "IC130") (pin "8") (pinfunction "O_8") (pintype "output"))
      (node (ref "IC67") (pin "3") (pinfunction "I_3") (pintype "input"))
      (node (ref "IC68") (pin "2") (pinfunction "I1_2") (pintype "input"))
    )
    (net (code "320") (name "/WRITE_REGB_TO_DBUS_JMP") (class "Default")
      (node (ref "IC1") (pin "12") (pinfunction "I0_12") (pintype "input"))
      (node (ref "IC52") (pin "11") (pinfunction "O_11") (pintype "output"))
    )
    (net (code "324") (name "/WRITE_REG_TO_DBUS_SELECTOR2_STR") (class "Default")
      (node (ref "IC100") (pin "11") (pinfunction "O_11") (pintype "output"))
      (node (ref "IC55") (pin "9") (pinfunction "I0_9") (pintype "input"))
    )
    (net (code "326") (name "/~{CLR_CARRY_BIT}") (class "Default")
      (node (ref "IC131") (pin "1") (pinfunction "CLR_1") (pintype "input"))
      (node (ref "JP4") (pin "12") (pinfunction "12_12") (pintype "passive"))
    )
    (net (code "327") (name "/~{ENABLE_REG_OUTPUT}") (class "Default")
      (node (ref "IC112") (pin "1") (pinfunction "I0_1") (pintype "input"))
      (node (ref "IC112") (pin "11") (pinfunction "O_11") (pintype "output"))
      (node (ref "IC112") (pin "5") (pinfunction "I1_5") (pintype "input"))
    )
    (net (code "328") (name "/~{IR_DATA_OUT_7}") (class "Default")
      (node (ref "IC59") (pin "10") (pinfunction "I1_10") (pintype "input"))
      (node (ref "IC86") (pin "10") (pinfunction "O_10") (pintype "output"))
      (node (ref "IC99") (pin "10") (pinfunction "I1_10") (pintype "input"))
    )
    (net (code "329") (name "/~{OPCODE_5}") (class "Default")
      (node (ref "IC14") (pin "6") (pinfunction "O_6") (pintype "output"))
      (node (ref "IC28") (pin "2") (pinfunction "I1_2") (pintype "input"))
      (node (ref "IC28") (pin "5") (pinfunction "I1_5") (pintype "input"))
    )
    (net (code "330") (name "/~{REGISTER_RESET}") (class "Default")
      (node (ref "IC102") (pin "14") (pinfunction "CLR_14") (pintype "input"))
      (node (ref "IC106") (pin "14") (pinfunction "CLR_14") (pintype "input"))
      (node (ref "IC17") (pin "14") (pinfunction "CLR_14") (pintype "input"))
      (node (ref "IC57") (pin "14") (pinfunction "CLR_14") (pintype "input"))
      (node (ref "IC58") (pin "14") (pinfunction "CLR_14") (pintype "input"))
      (node (ref "IC60") (pin "14") (pinfunction "CLR_14") (pintype "input"))
      (node (ref "IC61") (pin "14") (pinfunction "CLR_14") (pintype "input"))
      (node (ref "IC64") (pin "14") (pinfunction "CLR_14") (pintype "input"))
      (node (ref "IC69") (pin "14") (pinfunction "CLR_14") (pintype "input"))
      (node (ref "IC74") (pin "14") (pinfunction "CLR_14") (pintype "input"))
      (node (ref "IC75") (pin "14") (pinfunction "CLR_14") (pintype "input"))
      (node (ref "IC80") (pin "14") (pinfunction "CLR_14") (pintype "input"))
      (node (ref "IC93") (pin "14") (pinfunction "CLR_14") (pintype "input"))
      (node (ref "IC97") (pin "14") (pinfunction "CLR_14") (pintype "input"))
      (node (ref "JP4") (pin "8") (pinfunction "8_8") (pintype "passive"))
    )
    (net (code "331") (name "/~{RING_CNTR_RESET}") (class "Default")
      (node (ref "IC105") (pin "1") (pinfunction "CLR_1") (pintype "input"))
      (node (ref "IC105") (pin "13") (pinfunction "CLR_13") (pintype "input"))
      (node (ref "IC53") (pin "13") (pinfunction "CLR_13") (pintype "input"))
      (node (ref "IC53") (pin "4") (pinfunction "PRE_4") (pintype "input"))
      (node (ref "IC54") (pin "1") (pinfunction "CLR_1") (pintype "input"))
      (node (ref "IC54") (pin "13") (pinfunction "CLR_13") (pintype "input"))
      (node (ref "JP4") (pin "10") (pinfunction "10_10") (pintype "passive"))
    )
    (net (code "332") (name "/~{SET_CARRY_BIT}") (class "Default")
      (node (ref "IC131") (pin "4") (pinfunction "PRE_4") (pintype "input"))
      (node (ref "JP4") (pin "14") (pinfunction "14_14") (pintype "passive"))
    )
    (net (code "333") (name "/~{TWO_BYTE_CMD}") (class "Default")
      (node (ref "IC14") (pin "11") (pinfunction "I_11") (pintype "input"))
      (node (ref "IC89") (pin "10") (pinfunction "I1_10") (pintype "input"))
      (node (ref "IC96") (pin "8") (pinfunction "O_8") (pintype "output"))
    )
    (net (code "334") (name "GND") (class "Default")
      (node (ref "IC102") (pin "1") (pinfunction "B_1") (pintype "input"))
      (node (ref "IC102") (pin "10") (pinfunction "C_10") (pintype "input"))
      (node (ref "IC102") (pin "15") (pinfunction "A_15") (pintype "input"))
      (node (ref "IC102") (pin "9") (pinfunction "D_9") (pintype "input"))
      (node (ref "IC103") (pin "1") (pinfunction "OC_1") (pintype "input"))
      (node (ref "IC106") (pin "1") (pinfunction "B_1") (pintype "input"))
      (node (ref "IC106") (pin "10") (pinfunction "C_10") (pintype "input"))
      (node (ref "IC106") (pin "15") (pinfunction "A_15") (pintype "input"))
      (node (ref "IC106") (pin "9") (pinfunction "D_9") (pintype "input"))
      (node (ref "IC11") (pin "14") (pinfunction "4A_14") (pintype "input"))
      (node (ref "IC11") (pin "15") (pinfunction "G_15") (pintype "input"))
      (node (ref "IC12") (pin "15") (pinfunction "G_15") (pintype "input"))
      (node (ref "IC12") (pin "3") (pinfunction "1B_3") (pintype "input"))
      (node (ref "IC13") (pin "15") (pinfunction "G_15") (pintype "input"))
      (node (ref "IC15") (pin "7") (pinfunction "G_7") (pintype "input"))
      (node (ref "IC16") (pin "7") (pinfunction "G_7") (pintype "input"))
      (node (ref "IC18") (pin "1") (pinfunction "OC_1") (pintype "input"))
      (node (ref "IC21") (pin "15") (pinfunction "G_15") (pintype "input"))
      (node (ref "IC22") (pin "7") (pinfunction "G_7") (pintype "input"))
      (node (ref "IC23") (pin "7") (pinfunction "G_7") (pintype "input"))
      (node (ref "IC26") (pin "1") (pinfunction "OC_1") (pintype "input"))
      (node (ref "IC27") (pin "15") (pinfunction "G_15") (pintype "input"))
      (node (ref "IC3") (pin "7") (pinfunction "G_7") (pintype "input"))
      (node (ref "IC31") (pin "7") (pinfunction "G_7") (pintype "input"))
      (node (ref "IC32") (pin "7") (pinfunction "G_7") (pintype "input"))
      (node (ref "IC33") (pin "1") (pinfunction "OC_1") (pintype "input"))
      (node (ref "IC34") (pin "15") (pinfunction "G_15") (pintype "input"))
      (node (ref "IC37") (pin "7") (pinfunction "G_7") (pintype "input"))
      (node (ref "IC38") (pin "7") (pinfunction "G_7") (pintype "input"))
      (node (ref "IC4") (pin "7") (pinfunction "G_7") (pintype "input"))
      (node (ref "IC41") (pin "1") (pinfunction "OC_1") (pintype "input"))
      (node (ref "IC42") (pin "7") (pinfunction "G_7") (pintype "input"))
      (node (ref "IC43") (pin "7") (pinfunction "G_7") (pintype "input"))
      (node (ref "IC45") (pin "1") (pinfunction "OC_1") (pintype "input"))
      (node (ref "IC46") (pin "7") (pinfunction "G_7") (pintype "input"))
      (node (ref "IC47") (pin "7") (pinfunction "G_7") (pintype "input"))
      (node (ref "IC5") (pin "1") (pinfunction "OC_1") (pintype "input"))
      (node (ref "IC50") (pin "7") (pinfunction "G_7") (pintype "input"))
      (node (ref "IC51") (pin "7") (pinfunction "G_7") (pintype "input"))
      (node (ref "IC73") (pin "1") (pinfunction "OC_1") (pintype "input"))
      (node (ref "IC75") (pin "1") (pinfunction "B_1") (pintype "input"))
      (node (ref "IC75") (pin "10") (pinfunction "C_10") (pintype "input"))
      (node (ref "IC75") (pin "15") (pinfunction "A_15") (pintype "input"))
      (node (ref "IC75") (pin "9") (pinfunction "D_9") (pintype "input"))
      (node (ref "IC79") (pin "1") (pinfunction "OC_1") (pintype "input"))
      (node (ref "IC80") (pin "1") (pinfunction "B_1") (pintype "input"))
      (node (ref "IC80") (pin "10") (pinfunction "C_10") (pintype "input"))
      (node (ref "IC80") (pin "15") (pinfunction "A_15") (pintype "input"))
      (node (ref "IC80") (pin "9") (pinfunction "D_9") (pintype "input"))
      (node (ref "IC81") (pin "1") (pinfunction "OC_1") (pintype "input"))
      (node (ref "IC85") (pin "1") (pinfunction "OC_1") (pintype "input"))
      (node (ref "IC9") (pin "15") (pinfunction "G_15") (pintype "input"))
      (node (ref "IC93") (pin "1") (pinfunction "B_1") (pintype "input"))
      (node (ref "IC93") (pin "10") (pinfunction "C_10") (pintype "input"))
      (node (ref "IC93") (pin "15") (pinfunction "A_15") (pintype "input"))
      (node (ref "IC93") (pin "9") (pinfunction "D_9") (pintype "input"))
      (node (ref "IC97") (pin "1") (pinfunction "B_1") (pintype "input"))
      (node (ref "IC97") (pin "10") (pinfunction "C_10") (pintype "input"))
      (node (ref "IC97") (pin "15") (pinfunction "A_15") (pintype "input"))
      (node (ref "IC97") (pin "9") (pinfunction "D_9") (pintype "input"))
      (node (ref "JP1") (pin "18") (pinfunction "18_18") (pintype "passive"))
      (node (ref "JP1") (pin "26") (pinfunction "26_26") (pintype "passive"))
      (node (ref "JP1") (pin "30") (pinfunction "30_30") (pintype "passive"))
      (node (ref "JP2") (pin "10") (pinfunction "10_10") (pintype "passive"))
      (node (ref "JP2") (pin "14") (pinfunction "14_14") (pintype "passive"))
      (node (ref "JP2") (pin "18") (pinfunction "18_18") (pintype "passive"))
      (node (ref "JP2") (pin "2") (pinfunction "2_2") (pintype "passive"))
      (node (ref "JP2") (pin "26") (pinfunction "26_26") (pintype "passive"))
      (node (ref "JP2") (pin "30") (pinfunction "30_30") (pintype "passive"))
      (node (ref "JP3") (pin "17") (pinfunction "17_17") (pintype "passive"))
      (node (ref "JP3") (pin "18") (pinfunction "18_18") (pintype "passive"))
      (node (ref "JP3") (pin "21") (pinfunction "21_21") (pintype "passive"))
      (node (ref "JP3") (pin "22") (pinfunction "22_22") (pintype "passive"))
      (node (ref "JP3") (pin "39") (pinfunction "39_39") (pintype "passive"))
      (node (ref "JP3") (pin "40") (pinfunction "40_40") (pintype "passive"))
      (node (ref "JP4") (pin "1") (pinfunction "1_1") (pintype "passive"))
      (node (ref "JP4") (pin "11") (pinfunction "11_11") (pintype "passive"))
      (node (ref "JP4") (pin "13") (pinfunction "13_13") (pintype "passive"))
      (node (ref "JP4") (pin "15") (pinfunction "15_15") (pintype "passive"))
      (node (ref "JP4") (pin "2") (pinfunction "2_2") (pintype "passive"))
      (node (ref "JP4") (pin "21") (pinfunction "21_21") (pintype "passive"))
      (node (ref "JP4") (pin "22") (pinfunction "22_22") (pintype "passive"))
      (node (ref "JP4") (pin "24") (pinfunction "24_24") (pintype "passive"))
      (node (ref "JP4") (pin "38") (pinfunction "38_38") (pintype "passive"))
      (node (ref "JP4") (pin "39") (pinfunction "39_39") (pintype "passive"))
      (node (ref "JP4") (pin "40") (pinfunction "40_40") (pintype "passive"))
      (node (ref "JP4") (pin "5") (pinfunction "5_5") (pintype "passive"))
      (node (ref "JP4") (pin "6") (pinfunction "6_6") (pintype "passive"))
      (node (ref "JP4") (pin "7") (pinfunction "7_7") (pintype "passive"))
      (node (ref "JP4") (pin "9") (pinfunction "9_9") (pintype "passive"))
      (node (ref "JP5") (pin "17") (pinfunction "17_17") (pintype "passive"))
      (node (ref "JP5") (pin "18") (pinfunction "18_18") (pintype "passive"))
      (node (ref "JP5") (pin "21") (pinfunction "21_21") (pintype "passive"))
      (node (ref "JP5") (pin "22") (pinfunction "22_22") (pintype "passive"))
      (node (ref "JP5") (pin "36") (pinfunction "36_36") (pintype "passive"))
      (node (ref "JP5") (pin "38") (pinfunction "38_38") (pintype "passive"))
      (node (ref "JP5") (pin "39") (pinfunction "39_39") (pintype "passive"))
      (node (ref "JP5") (pin "40") (pinfunction "40_40") (pintype "passive"))
    )
    (net (code "335") (name "Net-(IC1B-I1)") (class "Default")
      (node (ref "IC1") (pin "11") (pinfunction "O_11") (pintype "output"))
      (node (ref "IC1") (pin "5") (pinfunction "I1_5") (pintype "input"))
    )
    (net (code "336") (name "Net-(IC6A-O)") (class "Default")
      (node (ref "IC6") (pin "3") (pinfunction "O_3") (pintype "output"))
      (node (ref "IC9") (pin "2") (pinfunction "1A_2") (pintype "input"))
    )
    (net (code "337") (name "Net-(IC6B-O)") (class "Default")
      (node (ref "IC6") (pin "6") (pinfunction "O_6") (pintype "output"))
      (node (ref "IC9") (pin "5") (pinfunction "2A_5") (pintype "input"))
    )
    (net (code "338") (name "Net-(IC6C-O)") (class "Default")
      (node (ref "IC6") (pin "8") (pinfunction "O_8") (pintype "output"))
      (node (ref "IC9") (pin "11") (pinfunction "3A_11") (pintype "input"))
    )
    (net (code "339") (name "Net-(IC6D-O)") (class "Default")
      (node (ref "IC6") (pin "11") (pinfunction "O_11") (pintype "output"))
      (node (ref "IC9") (pin "14") (pinfunction "4A_14") (pintype "input"))
    )
    (net (code "340") (name "Net-(IC8A-I0)") (class "Default")
      (node (ref "IC8") (pin "1") (pinfunction "I0_1") (pintype "input"))
      (node (ref "IC9") (pin "4") (pinfunction "1Y_4") (pintype "output"))
    )
    (net (code "341") (name "Net-(IC8A-I1)") (class "Default")
      (node (ref "IC8") (pin "2") (pinfunction "I1_2") (pintype "input"))
      (node (ref "IC8") (pin "5") (pinfunction "I1_5") (pintype "input"))
      (node (ref "IC9") (pin "9") (pinfunction "3Y_9") (pintype "output"))
    )
    (net (code "342") (name "Net-(IC8A-O)") (class "Default")
      (node (ref "IC8") (pin "3") (pinfunction "O_3") (pintype "output"))
      (node (ref "IC8") (pin "9") (pinfunction "I0_9") (pintype "input"))
    )
    (net (code "343") (name "Net-(IC8B-I0)") (class "Default")
      (node (ref "IC8") (pin "4") (pinfunction "I0_4") (pintype "input"))
      (node (ref "IC9") (pin "7") (pinfunction "2Y_7") (pintype "output"))
    )
    (net (code "344") (name "Net-(IC8D-I0)") (class "Default")
      (node (ref "IC8") (pin "12") (pinfunction "I0_12") (pintype "input"))
      (node (ref "IC9") (pin "12") (pinfunction "4Y_12") (pintype "output"))
    )
    (net (code "345") (name "Net-(IC10A-I1)") (class "Default")
      (node (ref "IC10") (pin "10") (pinfunction "I1_10") (pintype "input"))
      (node (ref "IC10") (pin "2") (pinfunction "I1_2") (pintype "input"))
      (node (ref "IC2") (pin "10") (pinfunction "I1_10") (pintype "input"))
      (node (ref "IC2") (pin "2") (pinfunction "I1_2") (pintype "input"))
      (node (ref "IC20") (pin "6") (pinfunction "O_6") (pintype "output"))
    )
    (net (code "346") (name "Net-(IC10B-I1)") (class "Default")
      (node (ref "IC10") (pin "13") (pinfunction "I1_13") (pintype "input"))
      (node (ref "IC10") (pin "5") (pinfunction "I1_5") (pintype "input"))
      (node (ref "IC2") (pin "13") (pinfunction "I1_13") (pintype "input"))
      (node (ref "IC2") (pin "5") (pinfunction "I1_5") (pintype "input"))
      (node (ref "IC20") (pin "3") (pinfunction "O_3") (pintype "output"))
    )
    (net (code "347") (name "Net-(IC11A-1A)") (class "Default")
      (node (ref "IC11") (pin "2") (pinfunction "1A_2") (pintype "input"))
      (node (ref "IC8") (pin "8") (pinfunction "O_8") (pintype "output"))
    )
    (net (code "348") (name "Net-(IC11A-2A)") (class "Default")
      (node (ref "IC11") (pin "5") (pinfunction "2A_5") (pintype "input"))
      (node (ref "IC8") (pin "6") (pinfunction "O_6") (pintype "output"))
    )
    (net (code "349") (name "Net-(IC11A-3A)") (class "Default")
      (node (ref "IC11") (pin "11") (pinfunction "3A_11") (pintype "input"))
      (node (ref "IC8") (pin "11") (pinfunction "O_11") (pintype "output"))
    )
    (net (code "350") (name "Net-(IC12A-2B)") (class "Default")
      (node (ref "IC12") (pin "6") (pinfunction "2B_6") (pintype "input"))
      (node (ref "IC65") (pin "6") (pinfunction "O_6") (pintype "output"))
    )
    (net (code "351") (name "Net-(IC14A-O)") (class "Default")
      (node (ref "IC14") (pin "2") (pinfunction "O_2") (pintype "output"))
      (node (ref "IC7") (pin "2") (pinfunction "I1_2") (pintype "input"))
      (node (ref "IC7") (pin "5") (pinfunction "I1_5") (pintype "input"))
    )
    (net (code "352") (name "Net-(IC14B-O)") (class "Default")
      (node (ref "IC14") (pin "4") (pinfunction "O_4") (pintype "output"))
      (node (ref "IC28") (pin "1") (pinfunction "I0_1") (pintype "input"))
      (node (ref "IC28") (pin "12") (pinfunction "I0_12") (pintype "input"))
    )
    (net (code "353") (name "Net-(IC14F-O)") (class "Default")
      (node (ref "IC14") (pin "12") (pinfunction "O_12") (pintype "output"))
      (node (ref "IC7") (pin "1") (pinfunction "I0_1") (pintype "input"))
      (node (ref "IC7") (pin "12") (pinfunction "I0_12") (pintype "input"))
    )
    (net (code "354") (name "Net-(IC15A-Y)") (class "Default")
      (node (ref "IC15") (pin "5") (pinfunction "Y_5") (pintype "output"))
      (node (ref "IC35") (pin "4") (pinfunction "2D_4") (pintype "input"))
    )
    (net (code "355") (name "Net-(IC16A-Y)") (class "Default")
      (node (ref "IC16") (pin "5") (pinfunction "Y_5") (pintype "output"))
      (node (ref "IC36") (pin "4") (pinfunction "2D_4") (pintype "input"))
    )
    (net (code "356") (name "Net-(IC17A-BO)") (class "Default")
      (node (ref "IC17") (pin "13") (pinfunction "BO_13") (pintype "output"))
      (node (ref "IC61") (pin "4") (pinfunction "DN_4") (pintype "input"))
    )
    (net (code "357") (name "Net-(IC17A-CO)") (class "Default")
      (node (ref "IC17") (pin "12") (pinfunction "CO_12") (pintype "output"))
      (node (ref "IC61") (pin "5") (pinfunction "UP_5") (pintype "input"))
    )
    (net (code "358") (name "Net-(IC19A-O)") (class "Default")
      (node (ref "IC19") (pin "1") (pinfunction "O_1") (pintype "output"))
      (node (ref "IC8") (pin "10") (pinfunction "I1_10") (pintype "input"))
      (node (ref "IC8") (pin "13") (pinfunction "I1_13") (pintype "input"))
    )
    (net (code "359") (name "Net-(IC19B-O)") (class "Default")
      (node (ref "IC19") (pin "4") (pinfunction "O_4") (pintype "output"))
      (node (ref "IC68") (pin "10") (pinfunction "I1_10") (pintype "input"))
      (node (ref "IC68") (pin "13") (pinfunction "I1_13") (pintype "input"))
    )
    (net (code "360") (name "Net-(IC19C-O)") (class "Default")
      (node (ref "IC19") (pin "10") (pinfunction "O_10") (pintype "output"))
      (node (ref "JP2") (pin "6") (pinfunction "6_6") (pintype "passive"))
    )
    (net (code "361") (name "Net-(IC19D-O)") (class "Default")
      (node (ref "IC19") (pin "13") (pinfunction "O_13") (pintype "output"))
      (node (ref "IC63") (pin "2") (pinfunction "I1_2") (pintype "input"))
    )
    (net (code "362") (name "Net-(IC20A-I1)") (class "Default")
      (node (ref "IC20") (pin "10") (pinfunction "I1_10") (pintype "input"))
      (node (ref "IC20") (pin "13") (pinfunction "I1_13") (pintype "input"))
      (node (ref "IC20") (pin "2") (pinfunction "I1_2") (pintype "input"))
      (node (ref "IC20") (pin "5") (pinfunction "I1_5") (pintype "input"))
      (node (ref "IC96") (pin "6") (pinfunction "O_6") (pintype "output"))
    )
    (net (code "363") (name "Net-(IC20C-O)") (class "Default")
      (node (ref "IC20") (pin "8") (pinfunction "O_8") (pintype "output"))
      (node (ref "IC24") (pin "10") (pinfunction "I1_10") (pintype "input"))
      (node (ref "IC24") (pin "2") (pinfunction "I1_2") (pintype "input"))
    )
    (net (code "364") (name "Net-(IC20D-O)") (class "Default")
      (node (ref "IC20") (pin "11") (pinfunction "O_11") (pintype "output"))
      (node (ref "IC24") (pin "13") (pinfunction "I1_13") (pintype "input"))
      (node (ref "IC24") (pin "5") (pinfunction "I1_5") (pintype "input"))
    )
    (net (code "365") (name "Net-(IC22A-Y)") (class "Default")
      (node (ref "IC22") (pin "5") (pinfunction "Y_5") (pintype "output"))
      (node (ref "IC35") (pin "7") (pinfunction "3D_7") (pintype "input"))
    )
    (net (code "366") (name "Net-(IC23A-Y)") (class "Default")
      (node (ref "IC23") (pin "5") (pinfunction "Y_5") (pintype "output"))
      (node (ref "IC36") (pin "7") (pinfunction "3D_7") (pintype "input"))
    )
    (net (code "367") (name "Net-(IC25A-O)") (class "Default")
      (node (ref "IC25") (pin "3") (pinfunction "O_3") (pintype "output"))
      (node (ref "IC71") (pin "5") (pinfunction "I1_5") (pintype "input"))
    )
    (net (code "368") (name "Net-(IC25B-O)") (class "Default")
      (node (ref "IC25") (pin "6") (pinfunction "O_6") (pintype "output"))
      (node (ref "IC71") (pin "4") (pinfunction "I0_4") (pintype "input"))
    )
    (net (code "369") (name "Net-(IC25C-I0)") (class "Default")
      (node (ref "IC25") (pin "9") (pinfunction "I0_9") (pintype "input"))
      (node (ref "IC58") (pin "12") (pinfunction "CO_12") (pintype "output"))
    )
    (net (code "370") (name "Net-(IC25C-O)") (class "Default")
      (node (ref "IC25") (pin "8") (pinfunction "O_8") (pintype "output"))
      (node (ref "IC60") (pin "5") (pinfunction "UP_5") (pintype "input"))
    )
    (net (code "371") (name "Net-(IC29A-I1)") (class "Default")
      (node (ref "IC29") (pin "3") (pinfunction "I1_3") (pintype "input"))
      (node (ref "IC30") (pin "3") (pinfunction "O_3") (pintype "output"))
    )
    (net (code "372") (name "Net-(IC29B-I1)") (class "Default")
      (node (ref "IC29") (pin "6") (pinfunction "I1_6") (pintype "input"))
      (node (ref "IC30") (pin "6") (pinfunction "O_6") (pintype "output"))
    )
    (net (code "373") (name "Net-(IC29C-I1)") (class "Default")
      (node (ref "IC29") (pin "9") (pinfunction "I1_9") (pintype "input"))
      (node (ref "IC30") (pin "8") (pinfunction "O_8") (pintype "output"))
    )
    (net (code "374") (name "Net-(IC29D-I1)") (class "Default")
      (node (ref "IC29") (pin "12") (pinfunction "I1_12") (pintype "input"))
      (node (ref "IC30") (pin "11") (pinfunction "O_11") (pintype "output"))
    )
    (net (code "375") (name "Net-(IC31A-Y)") (class "Default")
      (node (ref "IC31") (pin "5") (pinfunction "Y_5") (pintype "output"))
      (node (ref "IC35") (pin "8") (pinfunction "4D_8") (pintype "input"))
    )
    (net (code "376") (name "Net-(IC32A-Y)") (class "Default")
      (node (ref "IC32") (pin "5") (pinfunction "Y_5") (pintype "output"))
      (node (ref "IC36") (pin "8") (pinfunction "4D_8") (pintype "input"))
    )
    (net (code "377") (name "Net-(IC35A-1D)") (class "Default")
      (node (ref "IC3") (pin "5") (pinfunction "Y_5") (pintype "output"))
      (node (ref "IC35") (pin "3") (pinfunction "1D_3") (pintype "input"))
    )
    (net (code "378") (name "Net-(IC35A-5D)") (class "Default")
      (node (ref "IC35") (pin "13") (pinfunction "5D_13") (pintype "input"))
      (node (ref "IC37") (pin "5") (pinfunction "Y_5") (pintype "output"))
    )
    (net (code "379") (name "Net-(IC35A-6D)") (class "Default")
      (node (ref "IC35") (pin "14") (pinfunction "6D_14") (pintype "input"))
      (node (ref "IC42") (pin "5") (pinfunction "Y_5") (pintype "output"))
    )
    (net (code "380") (name "Net-(IC35A-7D)") (class "Default")
      (node (ref "IC35") (pin "17") (pinfunction "7D_17") (pintype "input"))
      (node (ref "IC46") (pin "5") (pinfunction "Y_5") (pintype "output"))
    )
    (net (code "381") (name "Net-(IC35A-8D)") (class "Default")
      (node (ref "IC35") (pin "18") (pinfunction "8D_18") (pintype "input"))
      (node (ref "IC50") (pin "5") (pinfunction "Y_5") (pintype "output"))
    )
    (net (code "382") (name "Net-(IC35A-ENC)") (class "Default")
      (node (ref "IC35") (pin "11") (pinfunction "ENC_11") (pintype "input"))
      (node (ref "IC59") (pin "3") (pinfunction "O_3") (pintype "output"))
    )
    (net (code "383") (name "Net-(IC36A-1D)") (class "Default")
      (node (ref "IC36") (pin "3") (pinfunction "1D_3") (pintype "input"))
      (node (ref "IC4") (pin "5") (pinfunction "Y_5") (pintype "output"))
    )
    (net (code "384") (name "Net-(IC36A-5D)") (class "Default")
      (node (ref "IC36") (pin "13") (pinfunction "5D_13") (pintype "input"))
      (node (ref "IC38") (pin "5") (pinfunction "Y_5") (pintype "output"))
    )
    (net (code "385") (name "Net-(IC36A-6D)") (class "Default")
      (node (ref "IC36") (pin "14") (pinfunction "6D_14") (pintype "input"))
      (node (ref "IC43") (pin "5") (pinfunction "Y_5") (pintype "output"))
    )
    (net (code "386") (name "Net-(IC36A-7D)") (class "Default")
      (node (ref "IC36") (pin "17") (pinfunction "7D_17") (pintype "input"))
      (node (ref "IC47") (pin "5") (pinfunction "Y_5") (pintype "output"))
    )
    (net (code "387") (name "Net-(IC36A-8D)") (class "Default")
      (node (ref "IC36") (pin "18") (pinfunction "8D_18") (pintype "input"))
      (node (ref "IC51") (pin "5") (pinfunction "Y_5") (pintype "output"))
    )
    (net (code "388") (name "Net-(IC36A-ENC)") (class "Default")
      (node (ref "IC36") (pin "11") (pinfunction "ENC_11") (pintype "input"))
      (node (ref "IC59") (pin "11") (pinfunction "O_11") (pintype "output"))
    )
    (net (code "389") (name "Net-(IC39C-I0)") (class "Default")
      (node (ref "IC39") (pin "8") (pinfunction "I0_8") (pintype "input"))
      (node (ref "IC94") (pin "3") (pinfunction "O_3") (pintype "output"))
    )
    (net (code "390") (name "Net-(IC39C-I1)") (class "Default")
      (node (ref "IC39") (pin "9") (pinfunction "I1_9") (pintype "input"))
      (node (ref "IC94") (pin "6") (pinfunction "O_6") (pintype "output"))
    )
    (net (code "391") (name "Net-(IC39D-I1)") (class "Default")
      (node (ref "IC39") (pin "12") (pinfunction "I1_12") (pintype "input"))
      (node (ref "IC48") (pin "6") (pinfunction "O_6") (pintype "output"))
    )
    (net (code "392") (name "Net-(IC39D-O)") (class "Default")
      (node (ref "IC39") (pin "13") (pinfunction "O_13") (pintype "output"))
      (node (ref "IC57") (pin "5") (pinfunction "UP_5") (pintype "input"))
    )
    (net (code "393") (name "Net-(IC44A-I0)") (class "Default")
      (node (ref "IC44") (pin "2") (pinfunction "I0_2") (pintype "input"))
      (node (ref "IC56") (pin "8") (pinfunction "O_8") (pintype "output"))
    )
    (net (code "394") (name "Net-(IC44A-I1)") (class "Default")
      (node (ref "IC44") (pin "3") (pinfunction "I1_3") (pintype "input"))
      (node (ref "IC56") (pin "11") (pinfunction "O_11") (pintype "output"))
    )
    (net (code "395") (name "Net-(IC44B-I1)") (class "Default")
      (node (ref "IC44") (pin "6") (pinfunction "I1_6") (pintype "input"))
      (node (ref "IC56") (pin "6") (pinfunction "O_6") (pintype "output"))
    )
    (net (code "396") (name "Net-(IC48A-O)") (class "Default")
      (node (ref "IC48") (pin "12") (pinfunction "I0_12") (pintype "input"))
      (node (ref "IC48") (pin "3") (pinfunction "O_3") (pintype "output"))
    )
    (net (code "397") (name "Net-(IC48C-O)") (class "Default")
      (node (ref "IC48") (pin "13") (pinfunction "I1_13") (pintype "input"))
      (node (ref "IC48") (pin "8") (pinfunction "O_8") (pintype "output"))
      (node (ref "IC99") (pin "12") (pinfunction "I0_12") (pintype "input"))
    )
    (net (code "398") (name "Net-(IC48D-O)") (class "Default")
      (node (ref "IC48") (pin "11") (pinfunction "O_11") (pintype "output"))
      (node (ref "IC92") (pin "12") (pinfunction "I0_12") (pintype "input"))
    )
    (net (code "399") (name "Net-(IC49C-O)") (class "Default")
      (node (ref "IC49") (pin "8") (pinfunction "O_8") (pintype "output"))
      (node (ref "JP5") (pin "30") (pinfunction "30_30") (pintype "passive"))
    )
    (net (code "400") (name "Net-(IC49D-O)") (class "Default")
      (node (ref "IC49") (pin "11") (pinfunction "O_11") (pintype "output"))
      (node (ref "JP5") (pin "28") (pinfunction "28_28") (pintype "passive"))
    )
    (net (code "401") (name "Net-(IC53B-D)") (class "Default")
      (node (ref "IC53") (pin "12") (pinfunction "D_12") (pintype "input"))
      (node (ref "IC89") (pin "11") (pinfunction "O_11") (pintype "output"))
    )
    (net (code "402") (name "Net-(IC54A-D)") (class "Default")
      (node (ref "IC54") (pin "2") (pinfunction "D_2") (pintype "input"))
      (node (ref "IC55") (pin "11") (pinfunction "O_11") (pintype "output"))
    )
    (net (code "403") (name "Net-(IC55D-I1)") (class "Default")
      (node (ref "IC55") (pin "13") (pinfunction "I1_13") (pintype "input"))
      (node (ref "IC89") (pin "8") (pinfunction "O_8") (pintype "output"))
    )
    (net (code "404") (name "Net-(IC57A-CO)") (class "Default")
      (node (ref "IC57") (pin "12") (pinfunction "CO_12") (pintype "output"))
      (node (ref "IC58") (pin "5") (pinfunction "UP_5") (pintype "input"))
    )
    (net (code "405") (name "Net-(IC60A-BO)") (class "Default")
      (node (ref "IC60") (pin "13") (pinfunction "BO_13") (pintype "output"))
      (node (ref "IC64") (pin "4") (pinfunction "DN_4") (pintype "input"))
    )
    (net (code "406") (name "Net-(IC60A-CO)") (class "Default")
      (node (ref "IC60") (pin "12") (pinfunction "CO_12") (pintype "output"))
      (node (ref "IC64") (pin "5") (pinfunction "UP_5") (pintype "input"))
    )
    (net (code "407") (name "Net-(IC61A-BO)") (class "Default")
      (node (ref "IC61") (pin "13") (pinfunction "BO_13") (pintype "output"))
      (node (ref "IC69") (pin "4") (pinfunction "DN_4") (pintype "input"))
    )
    (net (code "408") (name "Net-(IC61A-CO)") (class "Default")
      (node (ref "IC61") (pin "12") (pinfunction "CO_12") (pintype "output"))
      (node (ref "IC69") (pin "5") (pinfunction "UP_5") (pintype "input"))
    )
    (net (code "409") (name "Net-(IC65A-O)") (class "Default")
      (node (ref "IC65") (pin "3") (pinfunction "O_3") (pintype "output"))
      (node (ref "IC65") (pin "9") (pinfunction "I0_9") (pintype "input"))
    )
    (net (code "410") (name "Net-(IC67A-O)") (class "Default")
      (node (ref "IC67") (pin "2") (pinfunction "O_2") (pintype "output"))
      (node (ref "JP2") (pin "8") (pinfunction "8_8") (pintype "passive"))
    )
    (net (code "411") (name "Net-(IC67C-O)") (class "Default")
      (node (ref "IC67") (pin "6") (pinfunction "O_6") (pintype "output"))
      (node (ref "IC68") (pin "12") (pinfunction "I0_12") (pintype "input"))
    )
    (net (code "412") (name "Net-(IC68C-O)") (class "Default")
      (node (ref "IC68") (pin "8") (pinfunction "O_8") (pintype "output"))
      (node (ref "JP1") (pin "22") (pinfunction "22_22") (pintype "passive"))
    )
    (net (code "413") (name "Net-(IC68D-O)") (class "Default")
      (node (ref "IC68") (pin "11") (pinfunction "O_11") (pintype "output"))
      (node (ref "JP2") (pin "22") (pinfunction "22_22") (pintype "passive"))
    )
    (net (code "414") (name "Net-(IC69A-BO)") (class "Default")
      (node (ref "IC69") (pin "13") (pinfunction "BO_13") (pintype "output"))
      (node (ref "IC74") (pin "4") (pinfunction "DN_4") (pintype "input"))
    )
    (net (code "415") (name "Net-(IC69A-CO)") (class "Default")
      (node (ref "IC69") (pin "12") (pinfunction "CO_12") (pintype "output"))
      (node (ref "IC74") (pin "5") (pinfunction "UP_5") (pintype "input"))
    )
    (net (code "416") (name "Net-(IC70A-O)") (class "Default")
      (node (ref "IC70") (pin "3") (pinfunction "O_3") (pintype "output"))
      (node (ref "IC70") (pin "9") (pinfunction "I0_9") (pintype "input"))
    )
    (net (code "417") (name "Net-(IC70B-O)") (class "Default")
      (node (ref "IC70") (pin "10") (pinfunction "I1_10") (pintype "input"))
      (node (ref "IC70") (pin "6") (pinfunction "O_6") (pintype "output"))
    )
    (net (code "418") (name "Net-(IC70D-I0)") (class "Default")
      (node (ref "IC70") (pin "12") (pinfunction "I0_12") (pintype "input"))
      (node (ref "IC83") (pin "3") (pinfunction "O_3") (pintype "output"))
    )
    (net (code "419") (name "Net-(IC70D-I1)") (class "Default")
      (node (ref "IC70") (pin "13") (pinfunction "I1_13") (pintype "input"))
      (node (ref "IC78") (pin "3") (pinfunction "O_3") (pintype "output"))
    )
    (net (code "420") (name "Net-(IC71C-I0)") (class "Default")
      (node (ref "IC71") (pin "11") (pinfunction "O_11") (pintype "output"))
      (node (ref "IC71") (pin "9") (pinfunction "I0_9") (pintype "input"))
    )
    (net (code "421") (name "Net-(IC71C-I1)") (class "Default")
      (node (ref "IC71") (pin "10") (pinfunction "I1_10") (pintype "input"))
      (node (ref "IC78") (pin "11") (pinfunction "O_11") (pintype "output"))
    )
    (net (code "422") (name "Net-(IC71D-I0)") (class "Default")
      (node (ref "IC71") (pin "12") (pinfunction "I0_12") (pintype "input"))
      (node (ref "IC78") (pin "6") (pinfunction "O_6") (pintype "output"))
    )
    (net (code "423") (name "Net-(IC71D-I1)") (class "Default")
      (node (ref "IC71") (pin "13") (pinfunction "I1_13") (pintype "input"))
      (node (ref "IC83") (pin "11") (pinfunction "O_11") (pintype "output"))
    )
    (net (code "424") (name "Net-(IC75A-CO)") (class "Default")
      (node (ref "IC75") (pin "12") (pinfunction "CO_12") (pintype "output"))
      (node (ref "IC80") (pin "5") (pinfunction "UP_5") (pintype "input"))
    )
    (net (code "425") (name "Net-(IC77A-I0)") (class "Default")
      (node (ref "IC77") (pin "1") (pinfunction "I0_1") (pintype "input"))
      (node (ref "IC77") (pin "4") (pinfunction "I0_4") (pintype "input"))
      (node (ref "IC82") (pin "3") (pinfunction "O_3") (pintype "output"))
    )
    (net (code "426") (name "Net-(IC77B-I1)") (class "Default")
      (node (ref "IC77") (pin "13") (pinfunction "I1_13") (pintype "input"))
      (node (ref "IC77") (pin "5") (pinfunction "I1_5") (pintype "input"))
      (node (ref "IC83") (pin "13") (pinfunction "I1_13") (pintype "input"))
      (node (ref "IC83") (pin "5") (pinfunction "I1_5") (pintype "input"))
      (node (ref "IC86") (pin "8") (pinfunction "O_8") (pintype "output"))
      (node (ref "IC91") (pin "13") (pinfunction "I1_13") (pintype "input"))
      (node (ref "IC91") (pin "5") (pinfunction "I1_5") (pintype "input"))
      (node (ref "IC95") (pin "12") (pinfunction "I0_12") (pintype "input"))
      (node (ref "IC95") (pin "5") (pinfunction "I1_5") (pintype "input"))
    )
    (net (code "427") (name "Net-(IC77C-I0)") (class "Default")
      (node (ref "IC77") (pin "12") (pinfunction "I0_12") (pintype "input"))
      (node (ref "IC77") (pin "9") (pinfunction "I0_9") (pintype "input"))
      (node (ref "IC82") (pin "6") (pinfunction "O_6") (pintype "output"))
    )
    (net (code "428") (name "Net-(IC78A-I1)") (class "Default")
      (node (ref "IC78") (pin "2") (pinfunction "I1_2") (pintype "input"))
      (node (ref "IC83") (pin "6") (pinfunction "O_6") (pintype "output"))
    )
    (net (code "429") (name "Net-(IC78B-I1)") (class "Default")
      (node (ref "IC78") (pin "5") (pinfunction "I1_5") (pintype "input"))
      (node (ref "IC83") (pin "8") (pinfunction "O_8") (pintype "output"))
    )
    (net (code "430") (name "Net-(IC78D-I1)") (class "Default")
      (node (ref "IC78") (pin "13") (pinfunction "I1_13") (pintype "input"))
      (node (ref "IC91") (pin "3") (pinfunction "O_3") (pintype "output"))
    )
    (net (code "431") (name "Net-(IC82A-I0)") (class "Default")
      (node (ref "IC82") (pin "1") (pinfunction "I0_1") (pintype "input"))
      (node (ref "IC82") (pin "9") (pinfunction "I0_9") (pintype "input"))
      (node (ref "IC86") (pin "6") (pinfunction "O_6") (pintype "output"))
      (node (ref "IC90") (pin "10") (pinfunction "I1_10") (pintype "input"))
      (node (ref "IC90") (pin "2") (pinfunction "I1_2") (pintype "input"))
    )
    (net (code "432") (name "Net-(IC82A-I1)") (class "Default")
      (node (ref "IC82") (pin "2") (pinfunction "I1_2") (pintype "input"))
      (node (ref "IC82") (pin "4") (pinfunction "I0_4") (pintype "input"))
      (node (ref "IC87") (pin "3") (pinfunction "O_3") (pintype "output"))
    )
    (net (code "433") (name "Net-(IC82C-I1)") (class "Default")
      (node (ref "IC82") (pin "10") (pinfunction "I1_10") (pintype "input"))
      (node (ref "IC82") (pin "12") (pinfunction "I0_12") (pintype "input"))
      (node (ref "IC87") (pin "6") (pinfunction "O_6") (pintype "output"))
    )
    (net (code "434") (name "Net-(IC82C-O)") (class "Default")
      (node (ref "IC82") (pin "8") (pinfunction "O_8") (pintype "output"))
      (node (ref "IC83") (pin "1") (pinfunction "I0_1") (pintype "input"))
      (node (ref "IC83") (pin "4") (pinfunction "I0_4") (pintype "input"))
    )
    (net (code "435") (name "Net-(IC82D-O)") (class "Default")
      (node (ref "IC82") (pin "11") (pinfunction "O_11") (pintype "output"))
      (node (ref "IC83") (pin "12") (pinfunction "I0_12") (pintype "input"))
      (node (ref "IC83") (pin "9") (pinfunction "I0_9") (pintype "input"))
    )
    (net (code "436") (name "Net-(IC86A-O)") (class "Default")
      (node (ref "IC86") (pin "2") (pinfunction "O_2") (pintype "output"))
      (node (ref "IC87") (pin "1") (pinfunction "I0_1") (pintype "input"))
      (node (ref "IC87") (pin "12") (pinfunction "I0_12") (pintype "input"))
    )
    (net (code "437") (name "Net-(IC86B-O)") (class "Default")
      (node (ref "IC86") (pin "4") (pinfunction "O_4") (pintype "output"))
      (node (ref "IC87") (pin "2") (pinfunction "I1_2") (pintype "input"))
      (node (ref "IC87") (pin "5") (pinfunction "I1_5") (pintype "input"))
    )
    (net (code "438") (name "Net-(IC87C-O)") (class "Default")
      (node (ref "IC87") (pin "8") (pinfunction "O_8") (pintype "output"))
      (node (ref "IC90") (pin "1") (pinfunction "I0_1") (pintype "input"))
      (node (ref "IC90") (pin "4") (pinfunction "I0_4") (pintype "input"))
    )
    (net (code "439") (name "Net-(IC87D-O)") (class "Default")
      (node (ref "IC87") (pin "11") (pinfunction "O_11") (pintype "output"))
      (node (ref "IC90") (pin "12") (pinfunction "I0_12") (pintype "input"))
      (node (ref "IC90") (pin "9") (pinfunction "I0_9") (pintype "input"))
    )
    (net (code "440") (name "Net-(IC88C-I1)") (class "Default")
      (node (ref "IC88") (pin "10") (pinfunction "I1_10") (pintype "input"))
      (node (ref "IC91") (pin "6") (pinfunction "O_6") (pintype "output"))
      (node (ref "IC92") (pin "2") (pinfunction "I1_2") (pintype "input"))
    )
    (net (code "441") (name "Net-(IC90A-O)") (class "Default")
      (node (ref "IC90") (pin "3") (pinfunction "O_3") (pintype "output"))
      (node (ref "IC91") (pin "1") (pinfunction "I0_1") (pintype "input"))
      (node (ref "IC91") (pin "4") (pinfunction "I0_4") (pintype "input"))
    )
    (net (code "442") (name "Net-(IC90B-O)") (class "Default")
      (node (ref "IC90") (pin "6") (pinfunction "O_6") (pintype "output"))
      (node (ref "IC91") (pin "12") (pinfunction "I0_12") (pintype "input"))
      (node (ref "IC91") (pin "9") (pinfunction "I0_9") (pintype "input"))
    )
    (net (code "443") (name "Net-(IC90C-O)") (class "Default")
      (node (ref "IC90") (pin "8") (pinfunction "O_8") (pintype "output"))
      (node (ref "IC95") (pin "1") (pinfunction "I0_1") (pintype "input"))
      (node (ref "IC95") (pin "4") (pinfunction "I0_4") (pintype "input"))
    )
    (net (code "444") (name "Net-(IC90D-O)") (class "Default")
      (node (ref "IC90") (pin "11") (pinfunction "O_11") (pintype "output"))
      (node (ref "IC95") (pin "13") (pinfunction "I1_13") (pintype "input"))
      (node (ref "IC95") (pin "9") (pinfunction "I0_9") (pintype "input"))
    )
    (net (code "445") (name "Net-(IC92D-O)") (class "Default")
      (node (ref "IC92") (pin "11") (pinfunction "O_11") (pintype "output"))
      (node (ref "IC96") (pin "10") (pinfunction "I1_10") (pintype "input"))
    )
    (net (code "446") (name "Net-(IC93A-BO)") (class "Default")
      (node (ref "IC93") (pin "13") (pinfunction "BO_13") (pintype "output"))
      (node (ref "IC97") (pin "4") (pinfunction "DN_4") (pintype "input"))
    )
    (net (code "447") (name "Net-(IC93A-CO)") (class "Default")
      (node (ref "IC93") (pin "12") (pinfunction "CO_12") (pintype "output"))
      (node (ref "IC97") (pin "5") (pinfunction "UP_5") (pintype "input"))
    )
    (net (code "448") (name "Net-(IC94A-I0)") (class "Default")
      (node (ref "IC94") (pin "1") (pinfunction "I0_1") (pintype "input"))
      (node (ref "IC96") (pin "3") (pinfunction "O_3") (pintype "output"))
    )
    (net (code "449") (name "Net-(IC94A-I1)") (class "Default")
      (node (ref "IC94") (pin "2") (pinfunction "I1_2") (pintype "input"))
      (node (ref "IC96") (pin "11") (pinfunction "O_11") (pintype "output"))
    )
    (net (code "450") (name "Net-(IC94B-I0)") (class "Default")
      (node (ref "IC94") (pin "4") (pinfunction "I0_4") (pintype "input"))
      (node (ref "IC94") (pin "8") (pinfunction "O_8") (pintype "output"))
    )
    (net (code "451") (name "Net-(IC94B-I1)") (class "Default")
      (node (ref "IC94") (pin "11") (pinfunction "O_11") (pintype "output"))
      (node (ref "IC94") (pin "5") (pinfunction "I1_5") (pintype "input"))
    )
    (net (code "452") (name "Net-(IC100A-I1)") (class "Default")
      (node (ref "IC100") (pin "2") (pinfunction "I1_2") (pintype "input"))
      (node (ref "IC126") (pin "10") (pinfunction "I1_10") (pintype "input"))
      (node (ref "IC126") (pin "2") (pinfunction "I1_2") (pintype "input"))
      (node (ref "IC92") (pin "8") (pinfunction "O_8") (pintype "output"))
      (node (ref "IC99") (pin "2") (pinfunction "I1_2") (pintype "input"))
    )
    (net (code "453") (name "Net-(IC100B-I1)") (class "Default")
      (node (ref "IC100") (pin "5") (pinfunction "I1_5") (pintype "input"))
      (node (ref "IC130") (pin "13") (pinfunction "I1_13") (pintype "input"))
      (node (ref "IC63") (pin "3") (pinfunction "O_3") (pintype "output"))
    )
    (net (code "454") (name "Net-(IC101A-1D)") (class "Default")
      (node (ref "IC101") (pin "3") (pinfunction "1D_3") (pintype "input"))
      (node (ref "JP5") (pin "2") (pinfunction "2_2") (pintype "passive"))
    )
    (net (code "455") (name "Net-(IC101A-2D)") (class "Default")
      (node (ref "IC101") (pin "4") (pinfunction "2D_4") (pintype "input"))
      (node (ref "JP5") (pin "4") (pinfunction "4_4") (pintype "passive"))
    )
    (net (code "456") (name "Net-(IC101A-3D)") (class "Default")
      (node (ref "IC101") (pin "7") (pinfunction "3D_7") (pintype "input"))
      (node (ref "JP5") (pin "6") (pinfunction "6_6") (pintype "passive"))
    )
    (net (code "457") (name "Net-(IC101A-4D)") (class "Default")
      (node (ref "IC101") (pin "8") (pinfunction "4D_8") (pintype "input"))
      (node (ref "JP5") (pin "8") (pinfunction "8_8") (pintype "passive"))
    )
    (net (code "458") (name "Net-(IC101A-5D)") (class "Default")
      (node (ref "IC101") (pin "13") (pinfunction "5D_13") (pintype "input"))
      (node (ref "JP5") (pin "10") (pinfunction "10_10") (pintype "passive"))
    )
    (net (code "459") (name "Net-(IC101A-6D)") (class "Default")
      (node (ref "IC101") (pin "14") (pinfunction "6D_14") (pintype "input"))
      (node (ref "JP5") (pin "12") (pinfunction "12_12") (pintype "passive"))
    )
    (net (code "460") (name "Net-(IC101A-7D)") (class "Default")
      (node (ref "IC101") (pin "17") (pinfunction "7D_17") (pintype "input"))
      (node (ref "JP5") (pin "14") (pinfunction "14_14") (pintype "passive"))
    )
    (net (code "461") (name "Net-(IC101A-8D)") (class "Default")
      (node (ref "IC101") (pin "18") (pinfunction "8D_18") (pintype "input"))
      (node (ref "JP5") (pin "16") (pinfunction "16_16") (pintype "passive"))
    )
    (net (code "462") (name "Net-(IC101A-OC)") (class "Default")
      (node (ref "IC101") (pin "1") (pinfunction "OC_1") (pintype "input"))
      (node (ref "IC67") (pin "10") (pinfunction "O_10") (pintype "output"))
    )
    (net (code "463") (name "Net-(IC102A-BO)") (class "Default")
      (node (ref "IC102") (pin "13") (pinfunction "BO_13") (pintype "output"))
      (node (ref "IC106") (pin "4") (pinfunction "DN_4") (pintype "input"))
    )
    (net (code "464") (name "Net-(IC102A-CO)") (class "Default")
      (node (ref "IC102") (pin "12") (pinfunction "CO_12") (pintype "output"))
      (node (ref "IC106") (pin "5") (pinfunction "UP_5") (pintype "input"))
    )
    (net (code "465") (name "Net-(IC102A-DN)") (class "Default")
      (node (ref "IC102") (pin "4") (pinfunction "DN_4") (pintype "input"))
      (node (ref "IC97") (pin "13") (pinfunction "BO_13") (pintype "output"))
    )
    (net (code "466") (name "Net-(IC102A-UP)") (class "Default")
      (node (ref "IC102") (pin "5") (pinfunction "UP_5") (pintype "input"))
      (node (ref "IC97") (pin "12") (pinfunction "CO_12") (pintype "output"))
    )
    (net (code "467") (name "Net-(IC103A-1Q)") (class "Default")
      (node (ref "IC103") (pin "2") (pinfunction "1Q_2") (pintype "tri_state"))
      (node (ref "JP5") (pin "1") (pinfunction "1_1") (pintype "passive"))
    )
    (net (code "468") (name "Net-(IC103A-2Q)") (class "Default")
      (node (ref "IC103") (pin "5") (pinfunction "2Q_5") (pintype "tri_state"))
      (node (ref "JP5") (pin "3") (pinfunction "3_3") (pintype "passive"))
    )
    (net (code "469") (name "Net-(IC103A-3Q)") (class "Default")
      (node (ref "IC103") (pin "6") (pinfunction "3Q_6") (pintype "tri_state"))
      (node (ref "JP5") (pin "5") (pinfunction "5_5") (pintype "passive"))
    )
    (net (code "470") (name "Net-(IC103A-4Q)") (class "Default")
      (node (ref "IC103") (pin "9") (pinfunction "4Q_9") (pintype "tri_state"))
      (node (ref "JP5") (pin "7") (pinfunction "7_7") (pintype "passive"))
    )
    (net (code "471") (name "Net-(IC103A-5Q)") (class "Default")
      (node (ref "IC103") (pin "12") (pinfunction "5Q_12") (pintype "tri_state"))
      (node (ref "JP5") (pin "9") (pinfunction "9_9") (pintype "passive"))
    )
    (net (code "472") (name "Net-(IC103A-6Q)") (class "Default")
      (node (ref "IC103") (pin "15") (pinfunction "6Q_15") (pintype "tri_state"))
      (node (ref "JP5") (pin "11") (pinfunction "11_11") (pintype "passive"))
    )
    (net (code "473") (name "Net-(IC103A-7Q)") (class "Default")
      (node (ref "IC103") (pin "16") (pinfunction "7Q_16") (pintype "tri_state"))
      (node (ref "JP5") (pin "13") (pinfunction "13_13") (pintype "passive"))
    )
    (net (code "474") (name "Net-(IC103A-8Q)") (class "Default")
      (node (ref "IC103") (pin "19") (pinfunction "8Q_19") (pintype "tri_state"))
      (node (ref "JP5") (pin "15") (pinfunction "15_15") (pintype "passive"))
    )
    (net (code "475") (name "Net-(IC108A-I1)") (class "Default")
      (node (ref "IC108") (pin "2") (pinfunction "I1_2") (pintype "input"))
      (node (ref "IC70") (pin "11") (pinfunction "O_11") (pintype "output"))
    )
    (net (code "476") (name "Net-(IC108B-I0)") (class "Default")
      (node (ref "IC108") (pin "12") (pinfunction "I0_12") (pintype "input"))
      (node (ref "IC108") (pin "4") (pinfunction "I0_4") (pintype "input"))
      (node (ref "IC71") (pin "8") (pinfunction "O_8") (pintype "output"))
    )
    (net (code "477") (name "Net-(IC108B-I1)") (class "Default")
      (node (ref "IC108") (pin "5") (pinfunction "I1_5") (pintype "input"))
      (node (ref "IC86") (pin "13") (pinfunction "I_13") (pintype "input"))
      (node (ref "IC88") (pin "3") (pinfunction "O_3") (pintype "output"))
    )
    (net (code "478") (name "Net-(IC108B-O)") (class "Default")
      (node (ref "IC108") (pin "6") (pinfunction "O_6") (pintype "output"))
      (node (ref "IC108") (pin "9") (pinfunction "I0_9") (pintype "input"))
      (node (ref "IC40") (pin "10") (pinfunction "I1_10") (pintype "input"))
      (node (ref "IC40") (pin "13") (pinfunction "I1_13") (pintype "input"))
      (node (ref "IC40") (pin "2") (pinfunction "I1_2") (pintype "input"))
      (node (ref "IC40") (pin "5") (pinfunction "I1_5") (pintype "input"))
      (node (ref "IC59") (pin "9") (pinfunction "I0_9") (pintype "input"))
    )
    (net (code "479") (name "Net-(IC108D-I1)") (class "Default")
      (node (ref "IC108") (pin "13") (pinfunction "I1_13") (pintype "input"))
      (node (ref "IC86") (pin "12") (pinfunction "O_12") (pintype "output"))
    )
    (net (code "480") (name "Net-(IC108D-O)") (class "Default")
      (node (ref "IC108") (pin "11") (pinfunction "O_11") (pintype "output"))
      (node (ref "IC52") (pin "10") (pinfunction "I1_10") (pintype "input"))
      (node (ref "IC52") (pin "13") (pinfunction "I1_13") (pintype "input"))
      (node (ref "IC52") (pin "5") (pinfunction "I1_5") (pintype "input"))
    )
    (net (code "481") (name "Net-(IC112A-I1)") (class "Default")
      (node (ref "IC112") (pin "2") (pinfunction "I1_2") (pintype "input"))
      (node (ref "IC131") (pin "8") (pinfunction "~{Q}_8") (pintype "output"))
    )
    (net (code "482") (name "Net-(IC112A-O)") (class "Default")
      (node (ref "IC112") (pin "3") (pinfunction "O_3") (pintype "output"))
      (node (ref "IC36") (pin "1") (pinfunction "OC_1") (pintype "input"))
    )
    (net (code "483") (name "Net-(IC112B-I0)") (class "Default")
      (node (ref "IC112") (pin "4") (pinfunction "I0_4") (pintype "input"))
      (node (ref "IC131") (pin "9") (pinfunction "Q_9") (pintype "output"))
    )
    (net (code "484") (name "Net-(IC112B-O)") (class "Default")
      (node (ref "IC112") (pin "6") (pinfunction "O_6") (pintype "output"))
      (node (ref "IC35") (pin "1") (pinfunction "OC_1") (pintype "input"))
    )
    (net (code "485") (name "Net-(IC112C-O)") (class "Default")
      (node (ref "IC112") (pin "8") (pinfunction "O_8") (pintype "output"))
      (node (ref "IC30") (pin "10") (pinfunction "I1_10") (pintype "input"))
      (node (ref "IC30") (pin "13") (pinfunction "I1_13") (pintype "input"))
      (node (ref "IC30") (pin "2") (pinfunction "I1_2") (pintype "input"))
      (node (ref "IC30") (pin "5") (pinfunction "I1_5") (pintype "input"))
    )
    (net (code "486") (name "Net-(IC126D-I1)") (class "Default")
      (node (ref "IC126") (pin "13") (pinfunction "I1_13") (pintype "input"))
      (node (ref "IC52") (pin "2") (pinfunction "I1_2") (pintype "input"))
      (node (ref "IC59") (pin "6") (pinfunction "O_6") (pintype "output"))
      (node (ref "IC78") (pin "10") (pinfunction "I1_10") (pintype "input"))
      (node (ref "IC92") (pin "5") (pinfunction "I1_5") (pintype "input"))
    )
    (net (code "487") (name "Net-(IC129B-O)") (class "Default")
      (node (ref "IC129") (pin "4") (pinfunction "O_4") (pintype "output"))
      (node (ref "IC59") (pin "1") (pinfunction "I0_1") (pintype "input"))
    )
    (net (code "488") (name "Net-(IC129C-O)") (class "Default")
      (node (ref "IC129") (pin "6") (pinfunction "O_6") (pintype "output"))
      (node (ref "IC131") (pin "11") (pinfunction "CLK_11") (pintype "input"))
    )
    (net (code "489") (name "Net-(IC129D-O)") (class "Default")
      (node (ref "IC129") (pin "8") (pinfunction "O_8") (pintype "output"))
      (node (ref "IC57") (pin "4") (pinfunction "DN_4") (pintype "input"))
    )
    (net (code "490") (name "Net-(IC129E-I)") (class "Default")
      (node (ref "IC129") (pin "11") (pinfunction "I_11") (pintype "input"))
      (node (ref "IC99") (pin "11") (pinfunction "O_11") (pintype "output"))
    )
    (net (code "491") (name "Net-(IC129E-O)") (class "Default")
      (node (ref "IC129") (pin "10") (pinfunction "O_10") (pintype "output"))
      (node (ref "IC92") (pin "13") (pinfunction "I1_13") (pintype "input"))
    )
    (net (code "492") (name "Net-(IC129F-I)") (class "Default")
      (node (ref "IC129") (pin "13") (pinfunction "I_13") (pintype "input"))
      (node (ref "IC55") (pin "3") (pinfunction "O_3") (pintype "output"))
    )
    (net (code "493") (name "Net-(IC131A-CLK)") (class "Default")
      (node (ref "IC131") (pin "3") (pinfunction "CLK_3") (pintype "input"))
      (node (ref "IC67") (pin "8") (pinfunction "O_8") (pintype "output"))
    )
    (net (code "494") (name "VCC") (class "Default")
      (node (ref "IC102") (pin "11") (pinfunction "LD_11") (pintype "input"))
      (node (ref "IC105") (pin "10") (pinfunction "PRE_10") (pintype "input"))
      (node (ref "IC105") (pin "4") (pinfunction "PRE_4") (pintype "input"))
      (node (ref "IC106") (pin "11") (pinfunction "LD_11") (pintype "input"))
      (node (ref "IC131") (pin "10") (pinfunction "PRE_10") (pintype "input"))
      (node (ref "IC131") (pin "13") (pinfunction "CLR_13") (pintype "input"))
      (node (ref "IC17") (pin "4") (pinfunction "DN_4") (pintype "input"))
      (node (ref "IC53") (pin "1") (pinfunction "CLR_1") (pintype "input"))
      (node (ref "IC53") (pin "10") (pinfunction "PRE_10") (pintype "input"))
      (node (ref "IC54") (pin "10") (pinfunction "PRE_10") (pintype "input"))
      (node (ref "IC54") (pin "4") (pinfunction "PRE_4") (pintype "input"))
      (node (ref "IC58") (pin "4") (pinfunction "DN_4") (pintype "input"))
      (node (ref "IC75") (pin "11") (pinfunction "LD_11") (pintype "input"))
      (node (ref "IC75") (pin "4") (pinfunction "DN_4") (pintype "input"))
      (node (ref "IC80") (pin "11") (pinfunction "LD_11") (pintype "input"))
      (node (ref "IC80") (pin "4") (pinfunction "DN_4") (pintype "input"))
      (node (ref "IC93") (pin "11") (pinfunction "LD_11") (pintype "input"))
      (node (ref "IC97") (pin "11") (pinfunction "LD_11") (pintype "input"))
      (node (ref "JP1") (pin "28") (pinfunction "28_28") (pintype "passive"))
      (node (ref "JP2") (pin "12") (pinfunction "12_12") (pintype "passive"))
      (node (ref "JP2") (pin "28") (pinfunction "28_28") (pintype "passive"))
      (node (ref "JP3") (pin "19") (pinfunction "19_19") (pintype "passive"))
      (node (ref "JP3") (pin "20") (pinfunction "20_20") (pintype "passive"))
      (node (ref "JP4") (pin "17") (pinfunction "17_17") (pintype "passive"))
      (node (ref "JP4") (pin "19") (pinfunction "19_19") (pintype "passive"))
      (node (ref "JP5") (pin "19") (pinfunction "19_19") (pintype "passive"))
      (node (ref "JP5") (pin "20") (pinfunction "20_20") (pintype "passive"))
    )
    (net (code "495") (name "unconnected-(IC3A-W-Pad6)") (class "Default")
      (node (ref "IC3") (pin "6") (pinfunction "W_6") (pintype "output"))
    )
    (net (code "496") (name "unconnected-(IC4A-W-Pad6)") (class "Default")
      (node (ref "IC4") (pin "6") (pinfunction "W_6") (pintype "output"))
    )
    (net (code "497") (name "unconnected-(IC14D-I-Pad9)") (class "Default")
      (node (ref "IC14") (pin "9") (pinfunction "I_9") (pintype "input"))
    )
    (net (code "498") (name "unconnected-(IC14D-O-Pad8)") (class "Default")
      (node (ref "IC14") (pin "8") (pinfunction "O_8") (pintype "output"))
    )
    (net (code "499") (name "unconnected-(IC15A-W-Pad6)") (class "Default")
      (node (ref "IC15") (pin "6") (pinfunction "W_6") (pintype "output"))
    )
    (net (code "500") (name "unconnected-(IC16A-W-Pad6)") (class "Default")
      (node (ref "IC16") (pin "6") (pinfunction "W_6") (pintype "output"))
    )
    (net (code "501") (name "unconnected-(IC22A-W-Pad6)") (class "Default")
      (node (ref "IC22") (pin "6") (pinfunction "W_6") (pintype "output"))
    )
    (net (code "502") (name "unconnected-(IC23A-W-Pad6)") (class "Default")
      (node (ref "IC23") (pin "6") (pinfunction "W_6") (pintype "output"))
    )
    (net (code "503") (name "unconnected-(IC25D-I0-Pad12)") (class "Default")
      (node (ref "IC25") (pin "12") (pinfunction "I0_12") (pintype "input"))
    )
    (net (code "504") (name "unconnected-(IC25D-I1-Pad13)") (class "Default")
      (node (ref "IC25") (pin "13") (pinfunction "I1_13") (pintype "input"))
    )
    (net (code "505") (name "unconnected-(IC25D-O-Pad11)") (class "Default")
      (node (ref "IC25") (pin "11") (pinfunction "O_11") (pintype "output"))
    )
    (net (code "506") (name "unconnected-(IC31A-W-Pad6)") (class "Default")
      (node (ref "IC31") (pin "6") (pinfunction "W_6") (pintype "output"))
    )
    (net (code "507") (name "unconnected-(IC32A-W-Pad6)") (class "Default")
      (node (ref "IC32") (pin "6") (pinfunction "W_6") (pintype "output"))
    )
    (net (code "508") (name "unconnected-(IC37A-W-Pad6)") (class "Default")
      (node (ref "IC37") (pin "6") (pinfunction "W_6") (pintype "output"))
    )
    (net (code "509") (name "unconnected-(IC38A-W-Pad6)") (class "Default")
      (node (ref "IC38") (pin "6") (pinfunction "W_6") (pintype "output"))
    )
    (net (code "510") (name "unconnected-(IC42A-W-Pad6)") (class "Default")
      (node (ref "IC42") (pin "6") (pinfunction "W_6") (pintype "output"))
    )
    (net (code "511") (name "unconnected-(IC43A-W-Pad6)") (class "Default")
      (node (ref "IC43") (pin "6") (pinfunction "W_6") (pintype "output"))
    )
    (net (code "512") (name "unconnected-(IC46A-W-Pad6)") (class "Default")
      (node (ref "IC46") (pin "6") (pinfunction "W_6") (pintype "output"))
    )
    (net (code "513") (name "unconnected-(IC47A-W-Pad6)") (class "Default")
      (node (ref "IC47") (pin "6") (pinfunction "W_6") (pintype "output"))
    )
    (net (code "514") (name "unconnected-(IC50A-W-Pad6)") (class "Default")
      (node (ref "IC50") (pin "6") (pinfunction "W_6") (pintype "output"))
    )
    (net (code "515") (name "unconnected-(IC51A-W-Pad6)") (class "Default")
      (node (ref "IC51") (pin "6") (pinfunction "W_6") (pintype "output"))
    )
    (net (code "516") (name "unconnected-(IC54A-~{Q}-Pad6)") (class "Default")
      (node (ref "IC54") (pin "6") (pinfunction "~{Q}_6") (pintype "output"))
    )
    (net (code "517") (name "unconnected-(IC54B-~{Q}-Pad8)") (class "Default")
      (node (ref "IC54") (pin "8") (pinfunction "~{Q}_8") (pintype "output"))
    )
    (net (code "518") (name "unconnected-(IC57A-BO-Pad13)") (class "Default")
      (node (ref "IC57") (pin "13") (pinfunction "BO_13") (pintype "output"))
    )
    (net (code "519") (name "unconnected-(IC58A-BO-Pad13)") (class "Default")
      (node (ref "IC58") (pin "13") (pinfunction "BO_13") (pintype "output"))
    )
    (net (code "520") (name "unconnected-(IC63C-I0-Pad9)") (class "Default")
      (node (ref "IC63") (pin "9") (pinfunction "I0_9") (pintype "input"))
    )
    (net (code "521") (name "unconnected-(IC63C-I1-Pad10)") (class "Default")
      (node (ref "IC63") (pin "10") (pinfunction "I1_10") (pintype "input"))
    )
    (net (code "522") (name "unconnected-(IC63C-O-Pad8)") (class "Default")
      (node (ref "IC63") (pin "8") (pinfunction "O_8") (pintype "output"))
    )
    (net (code "523") (name "unconnected-(IC64A-BO-Pad13)") (class "Default")
      (node (ref "IC64") (pin "13") (pinfunction "BO_13") (pintype "output"))
    )
    (net (code "524") (name "unconnected-(IC64A-CO-Pad12)") (class "Default")
      (node (ref "IC64") (pin "12") (pinfunction "CO_12") (pintype "output"))
    )
    (net (code "525") (name "unconnected-(IC74A-BO-Pad13)") (class "Default")
      (node (ref "IC74") (pin "13") (pinfunction "BO_13") (pintype "output"))
    )
    (net (code "526") (name "unconnected-(IC74A-CO-Pad12)") (class "Default")
      (node (ref "IC74") (pin "12") (pinfunction "CO_12") (pintype "output"))
    )
    (net (code "527") (name "unconnected-(IC75A-BO-Pad13)") (class "Default")
      (node (ref "IC75") (pin "13") (pinfunction "BO_13") (pintype "output"))
    )
    (net (code "528") (name "unconnected-(IC80A-BO-Pad13)") (class "Default")
      (node (ref "IC80") (pin "13") (pinfunction "BO_13") (pintype "output"))
    )
    (net (code "529") (name "unconnected-(IC80A-CO-Pad12)") (class "Default")
      (node (ref "IC80") (pin "12") (pinfunction "CO_12") (pintype "output"))
    )
    (net (code "530") (name "unconnected-(IC105A-~{Q}-Pad6)") (class "Default")
      (node (ref "IC105") (pin "6") (pinfunction "~{Q}_6") (pintype "output"))
    )
    (net (code "531") (name "unconnected-(IC105B-~{Q}-Pad8)") (class "Default")
      (node (ref "IC105") (pin "8") (pinfunction "~{Q}_8") (pintype "output"))
    )
    (net (code "532") (name "unconnected-(IC106A-BO-Pad13)") (class "Default")
      (node (ref "IC106") (pin "13") (pinfunction "BO_13") (pintype "output"))
    )
    (net (code "533") (name "unconnected-(IC106A-CO-Pad12)") (class "Default")
      (node (ref "IC106") (pin "12") (pinfunction "CO_12") (pintype "output"))
    )
    (net (code "534") (name "unconnected-(IC129A-I-Pad1)") (class "Default")
      (node (ref "IC129") (pin "1") (pinfunction "I_1") (pintype "input"))
    )
    (net (code "535") (name "unconnected-(IC129A-O-Pad2)") (class "Default")
      (node (ref "IC129") (pin "2") (pinfunction "O_2") (pintype "output"))
    )
    (net (code "536") (name "unconnected-(IC130A-I0-Pad1)") (class "Default")
      (node (ref "IC130") (pin "1") (pinfunction "I0_1") (pintype "input"))
    )
    (net (code "537") (name "unconnected-(IC130A-I1-Pad2)") (class "Default")
      (node (ref "IC130") (pin "2") (pinfunction "I1_2") (pintype "input"))
    )
    (net (code "538") (name "unconnected-(IC130A-O-Pad3)") (class "Default")
      (node (ref "IC130") (pin "3") (pinfunction "O_3") (pintype "output"))
    )
    (net (code "539") (name "unconnected-(IC131A-~{Q}-Pad6)") (class "Default")
      (node (ref "IC131") (pin "6") (pinfunction "~{Q}_6") (pintype "output"))
    )
    (net (code "540") (name "unconnected-(JP2-Pad16)") (class "Default")
      (node (ref "JP2") (pin "16") (pinfunction "16_16") (pintype "passive"))
    )
  )
)
